# magarray_v1.net
KiCad netlist of a schematic drawn in EAGLE
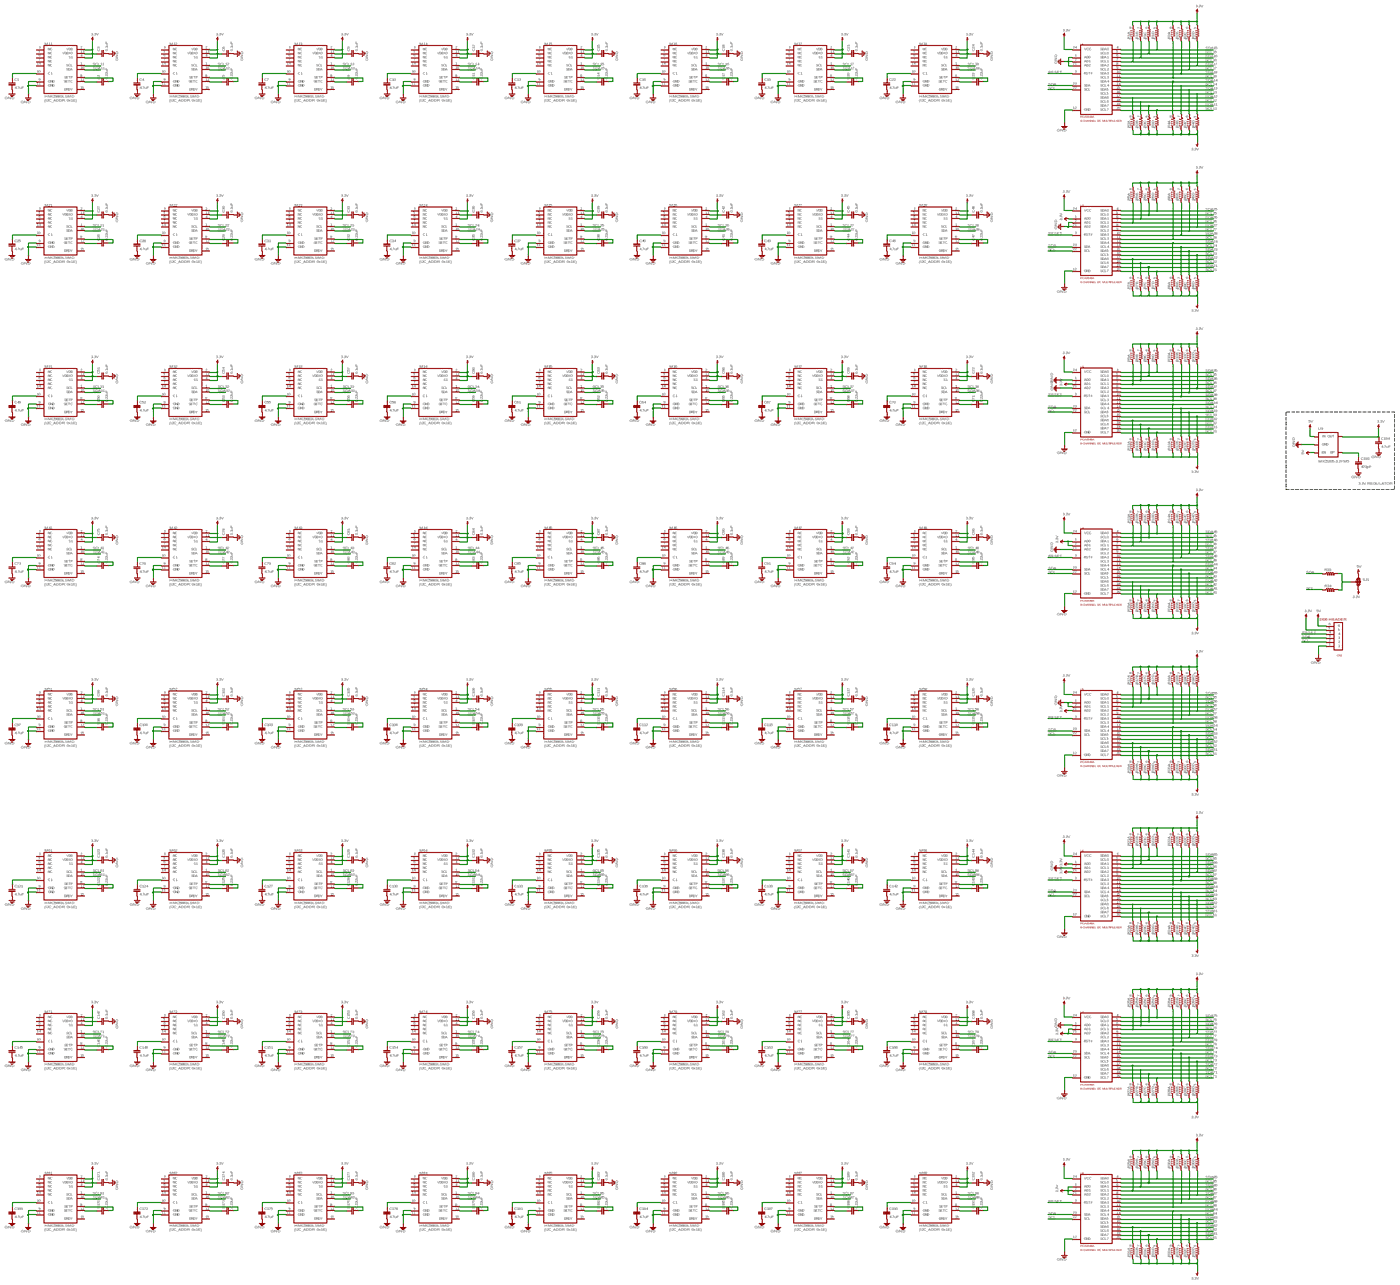
[diagram p0: schematic, sheet 1, overview]
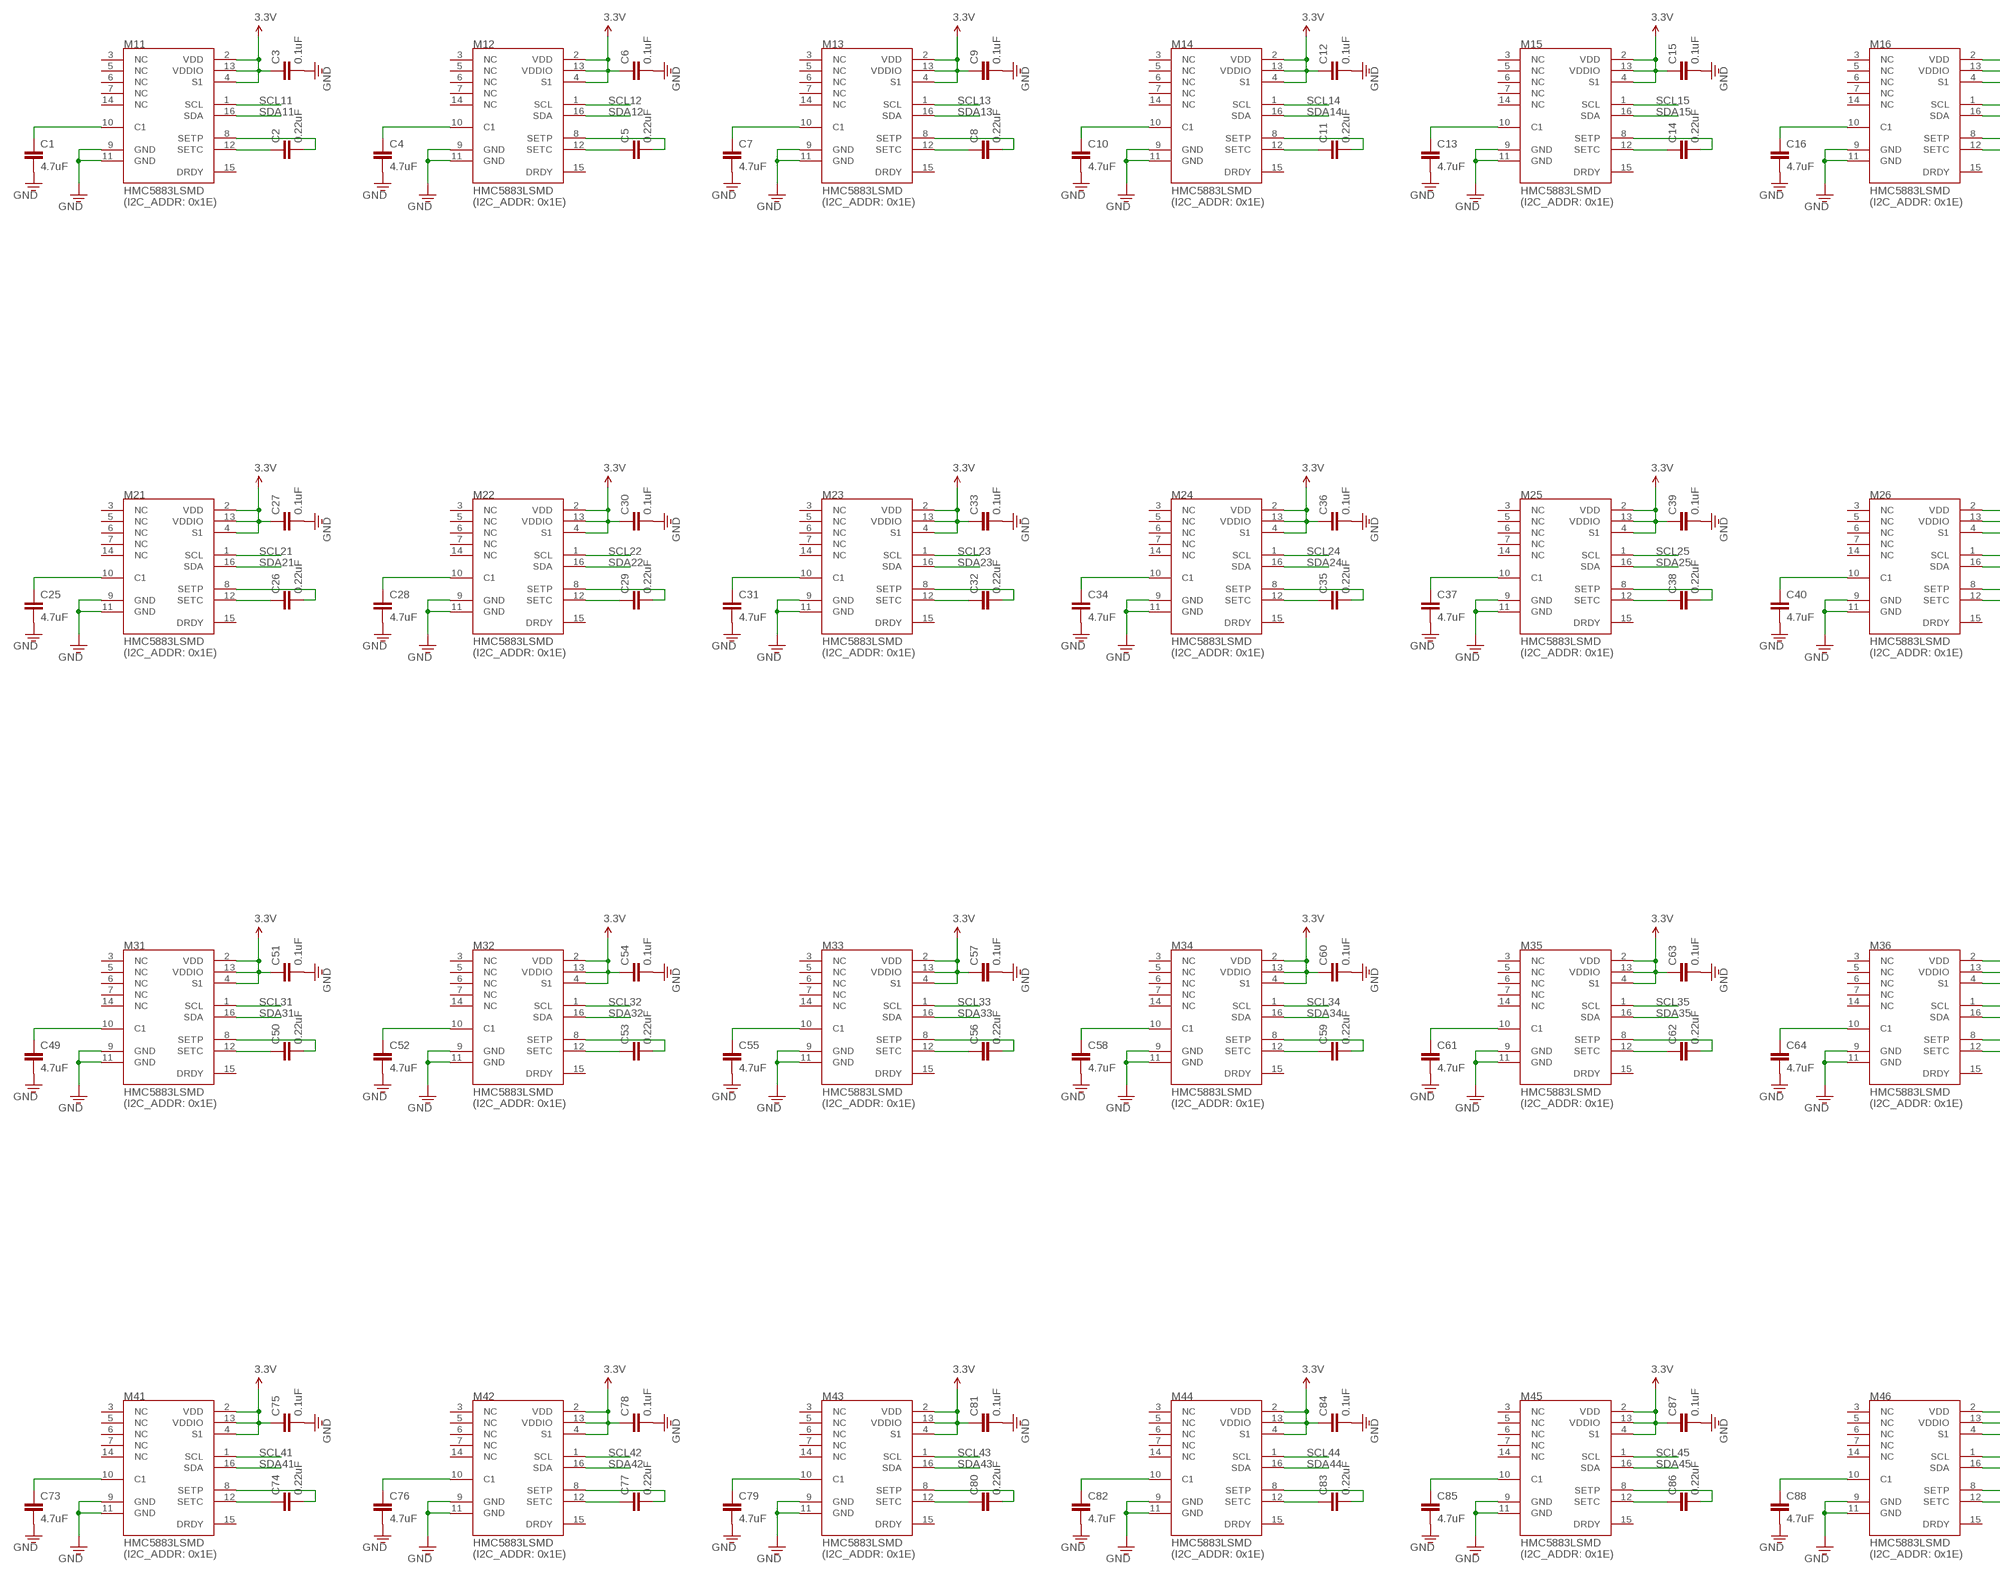
[diagram p1: schematic, sheet 1, part 1 of 4]
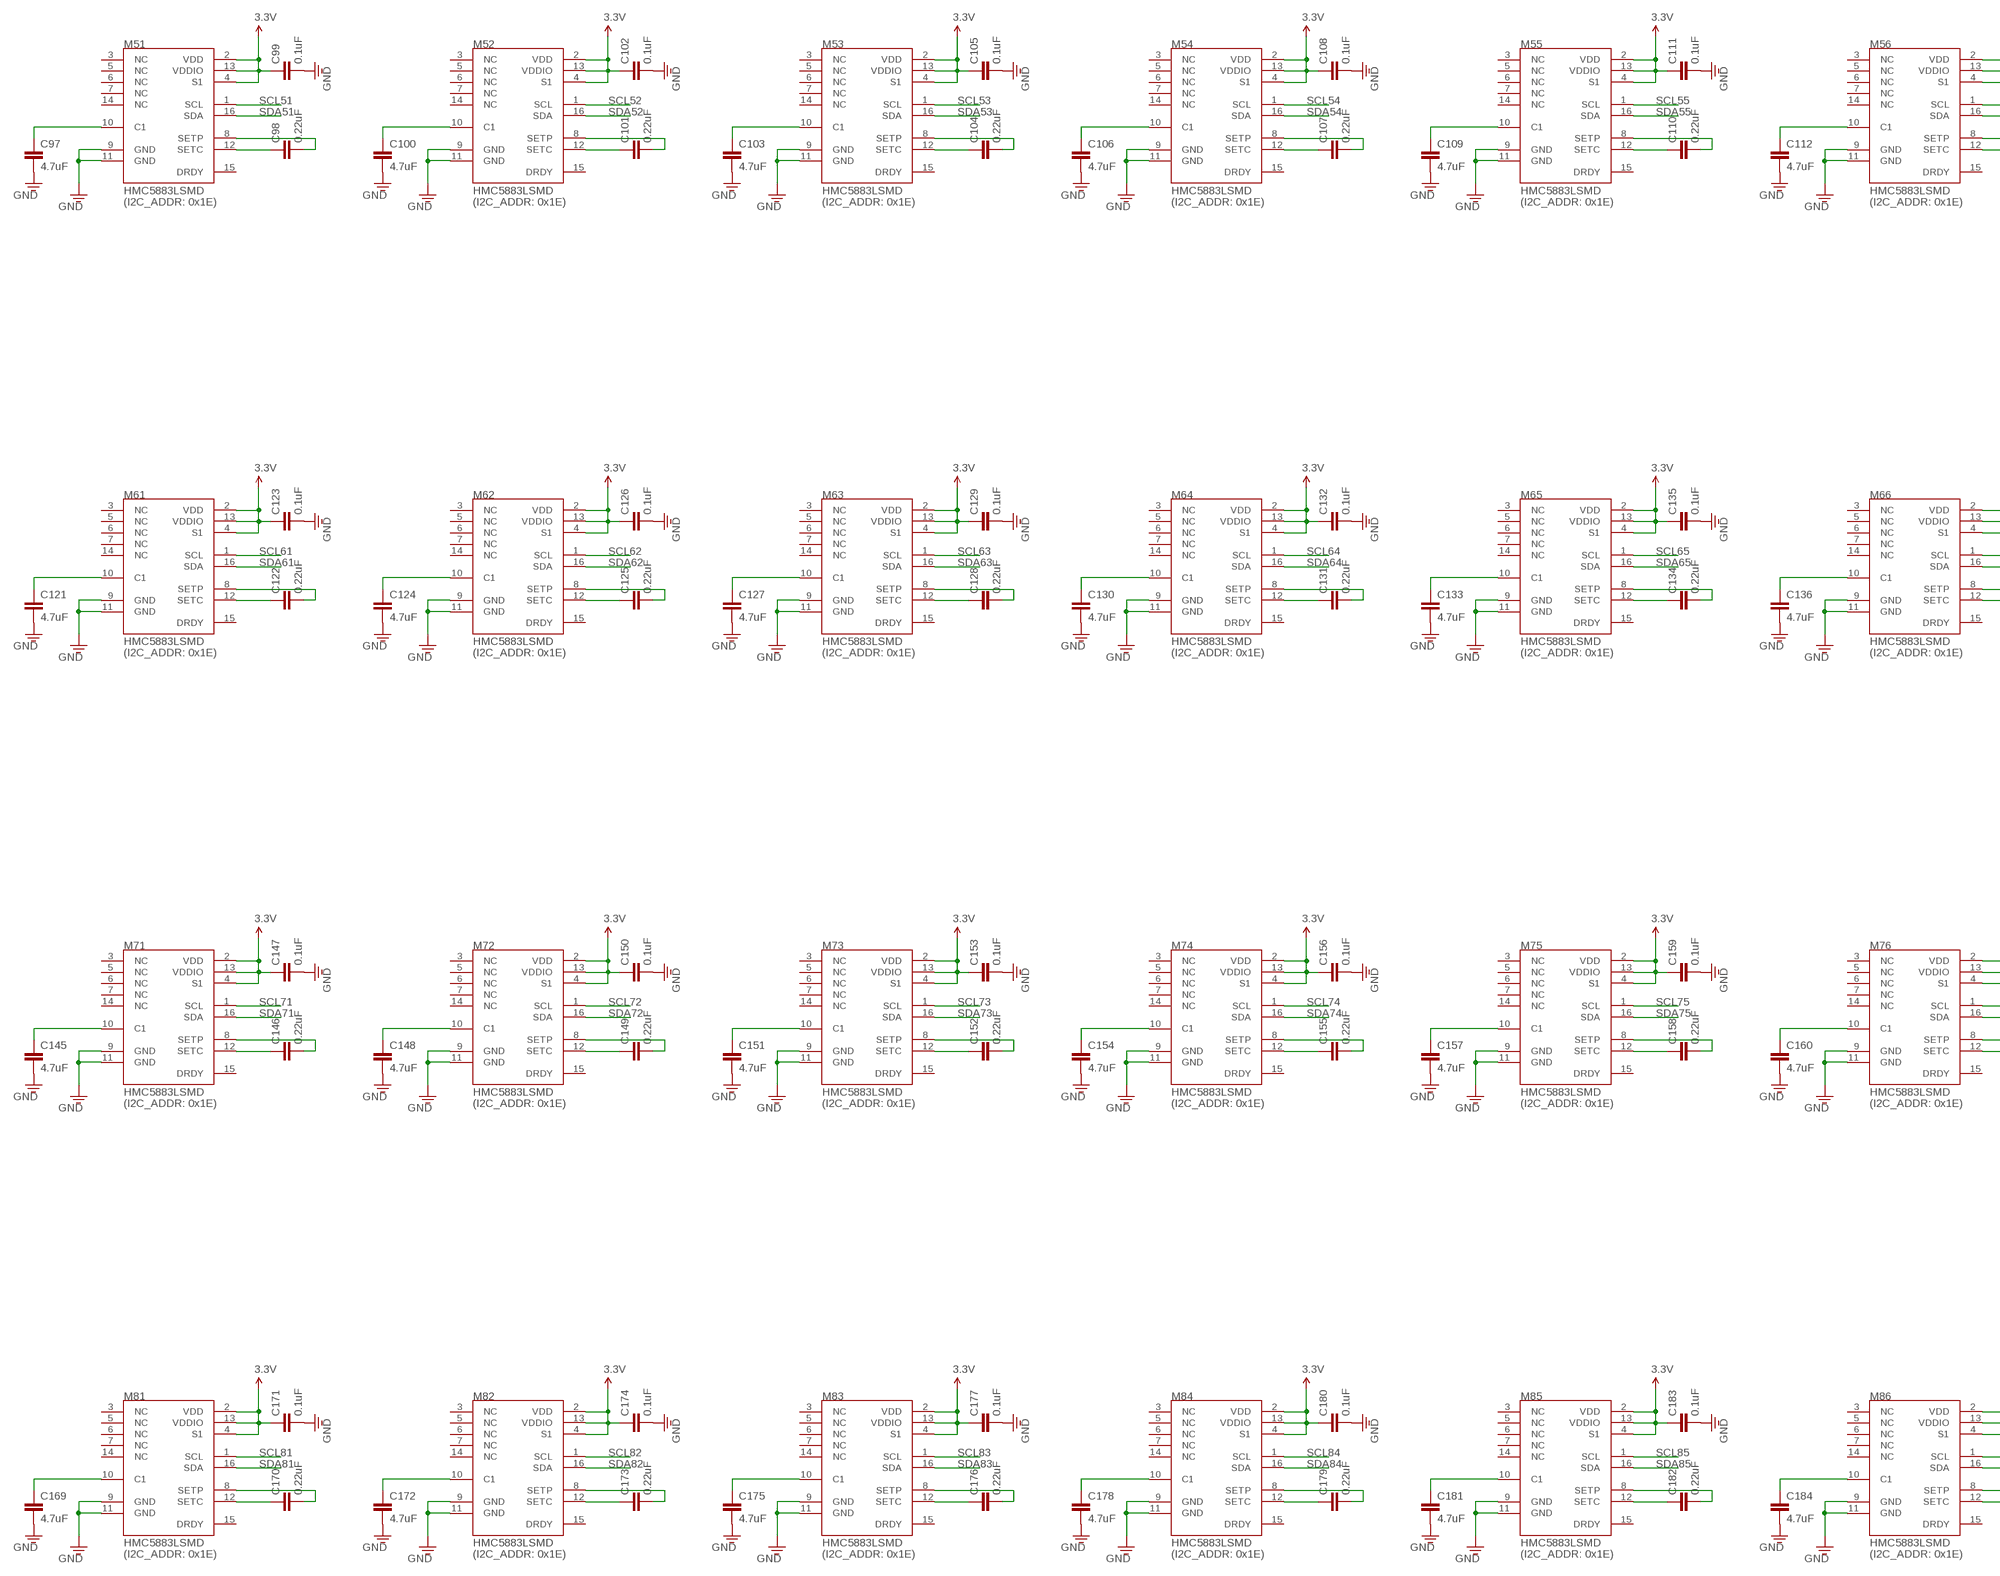
[diagram p2: schematic, sheet 1, part 2 of 4]
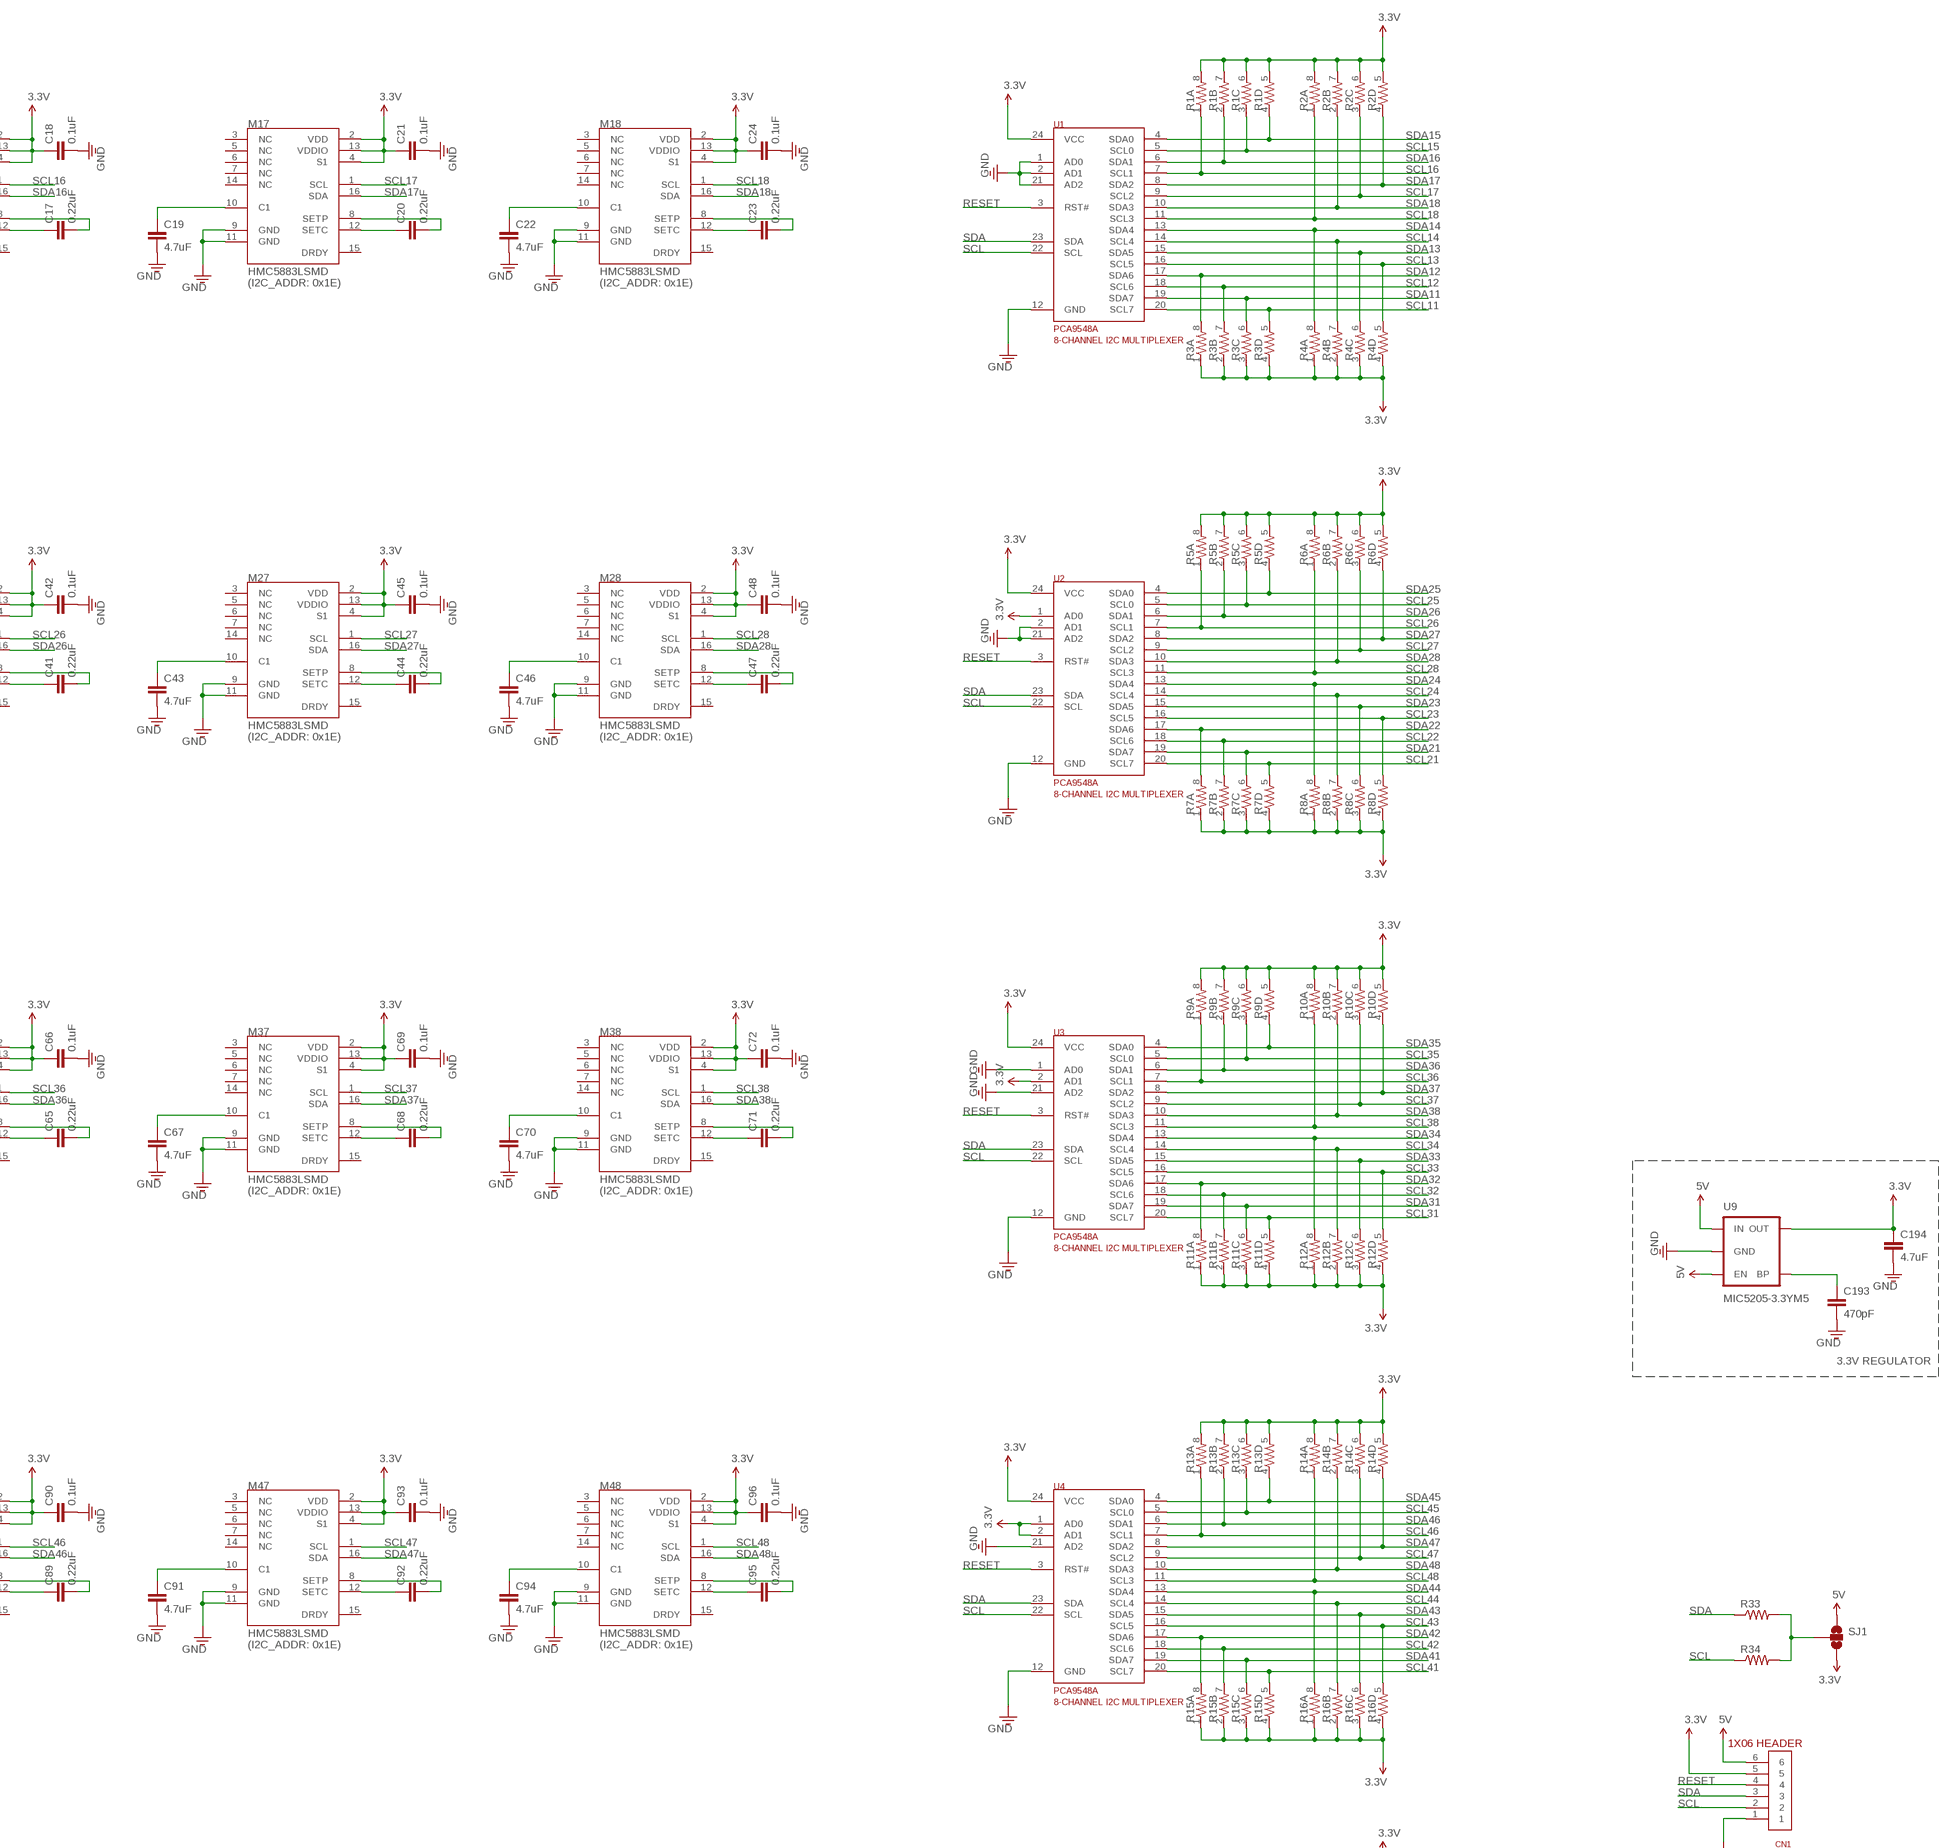
[diagram p3: schematic, sheet 1, part 3 of 4]
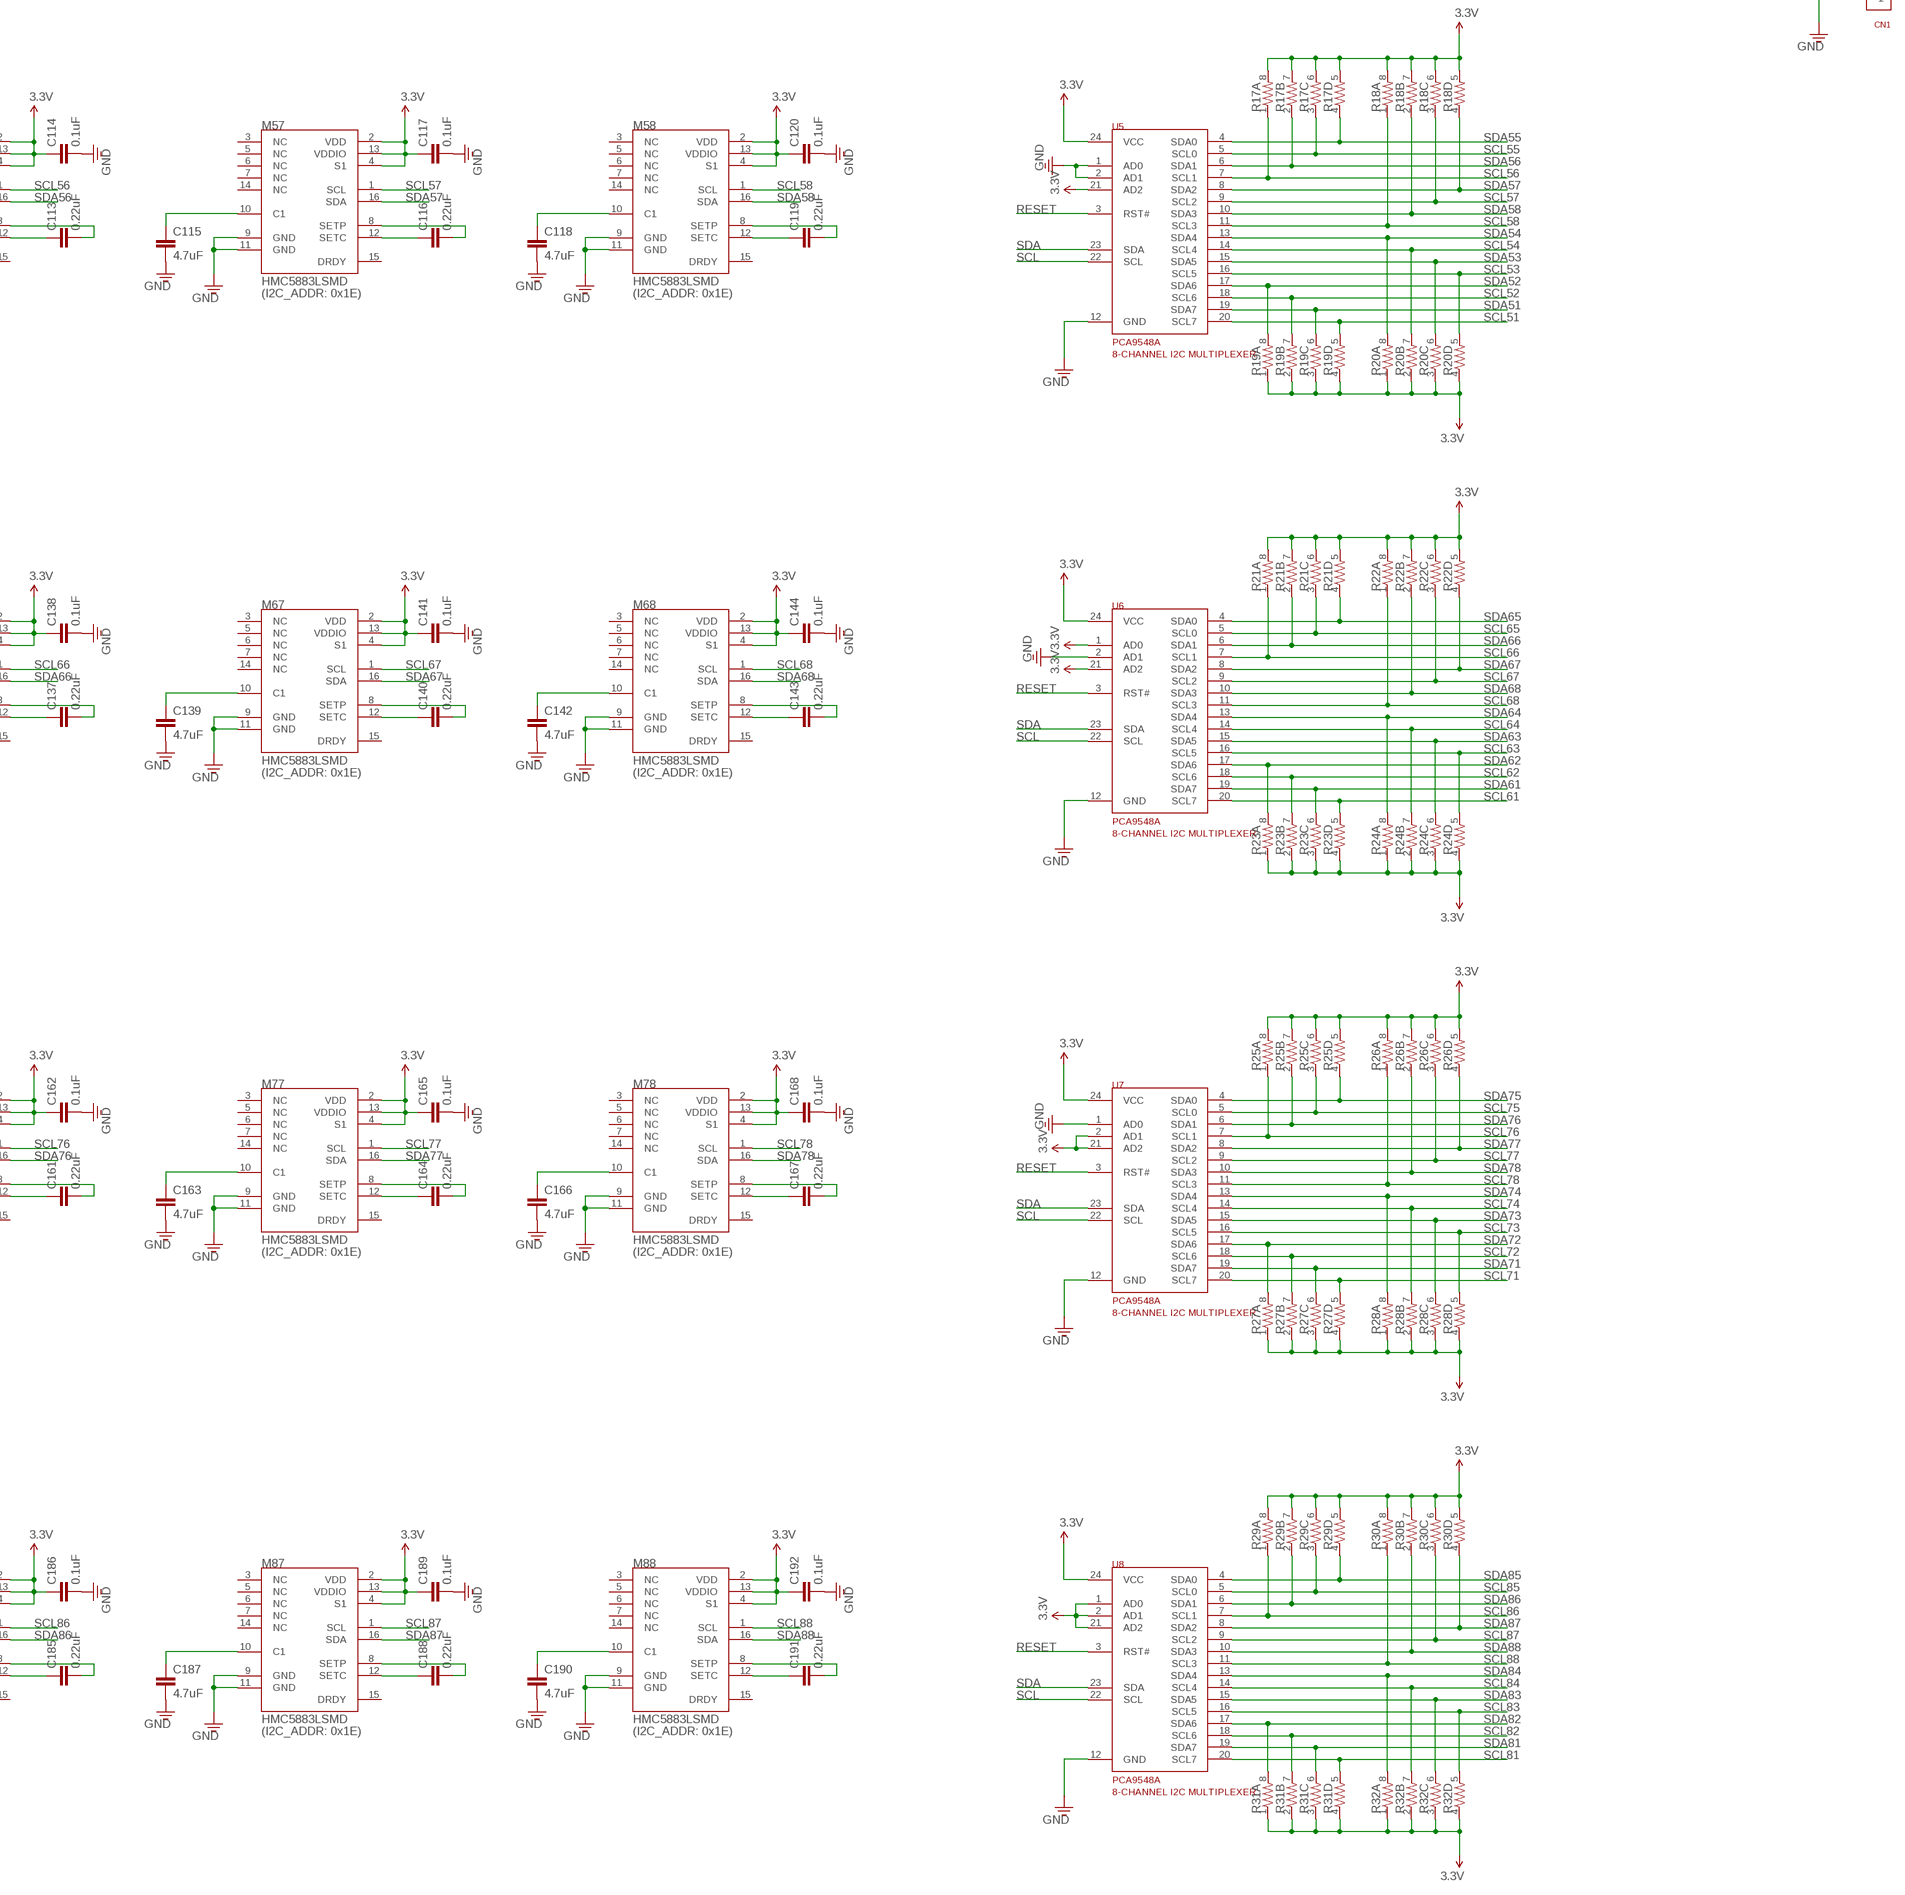
[diagram p4: schematic, sheet 1, part 4 of 4]

(export (version "E")
  (design (tool "Eeschema 10.0.6"))
  (components
    (comp (ref "C1")
      (value "4.7uF")
      (footprint "eagle-import:0603")
      (libsource (lib "eagle-import") (part "CAP0603"))
    )
    (comp (ref "C2")
      (value "0.22uF")
      (footprint "eagle-import:C0402")
      (libsource (lib "eagle-import") (part "CAP0402"))
    )
    (comp (ref "C3")
      (value "0.1uF")
      (footprint "eagle-import:C0402")
      (libsource (lib "eagle-import") (part "CAP0402"))
    )
    (comp (ref "C4")
      (value "4.7uF")
      (footprint "eagle-import:0603")
      (libsource (lib "eagle-import") (part "CAP0603"))
    )
    (comp (ref "C5")
      (value "0.22uF")
      (footprint "eagle-import:C0402")
      (libsource (lib "eagle-import") (part "CAP0402"))
    )
    (comp (ref "C6")
      (value "0.1uF")
      (footprint "eagle-import:C0402")
      (libsource (lib "eagle-import") (part "CAP0402"))
    )
    (comp (ref "C7")
      (value "4.7uF")
      (footprint "eagle-import:0603")
      (libsource (lib "eagle-import") (part "CAP0603"))
    )
    (comp (ref "C8")
      (value "0.22uF")
      (footprint "eagle-import:C0402")
      (libsource (lib "eagle-import") (part "CAP0402"))
    )
    (comp (ref "C9")
      (value "0.1uF")
      (footprint "eagle-import:C0402")
      (libsource (lib "eagle-import") (part "CAP0402"))
    )
    (comp (ref "C10")
      (value "4.7uF")
      (footprint "eagle-import:0603")
      (libsource (lib "eagle-import") (part "CAP0603"))
    )
    (comp (ref "C11")
      (value "0.22uF")
      (footprint "eagle-import:C0402")
      (libsource (lib "eagle-import") (part "CAP0402"))
    )
    (comp (ref "C12")
      (value "0.1uF")
      (footprint "eagle-import:C0402")
      (libsource (lib "eagle-import") (part "CAP0402"))
    )
    (comp (ref "C13")
      (value "4.7uF")
      (footprint "eagle-import:0603")
      (libsource (lib "eagle-import") (part "CAP0603"))
    )
    (comp (ref "C14")
      (value "0.22uF")
      (footprint "eagle-import:C0402")
      (libsource (lib "eagle-import") (part "CAP0402"))
    )
    (comp (ref "C15")
      (value "0.1uF")
      (footprint "eagle-import:C0402")
      (libsource (lib "eagle-import") (part "CAP0402"))
    )
    (comp (ref "C16")
      (value "4.7uF")
      (footprint "eagle-import:0603")
      (libsource (lib "eagle-import") (part "CAP0603"))
    )
    (comp (ref "C17")
      (value "0.22uF")
      (footprint "eagle-import:C0402")
      (libsource (lib "eagle-import") (part "CAP0402"))
    )
    (comp (ref "C18")
      (value "0.1uF")
      (footprint "eagle-import:C0402")
      (libsource (lib "eagle-import") (part "CAP0402"))
    )
    (comp (ref "C19")
      (value "4.7uF")
      (footprint "eagle-import:0603")
      (libsource (lib "eagle-import") (part "CAP0603"))
    )
    (comp (ref "C20")
      (value "0.22uF")
      (footprint "eagle-import:C0402")
      (libsource (lib "eagle-import") (part "CAP0402"))
    )
    (comp (ref "C21")
      (value "0.1uF")
      (footprint "eagle-import:C0402")
      (libsource (lib "eagle-import") (part "CAP0402"))
    )
    (comp (ref "C22")
      (value "4.7uF")
      (footprint "eagle-import:0603")
      (libsource (lib "eagle-import") (part "CAP0603"))
    )
    (comp (ref "C23")
      (value "0.22uF")
      (footprint "eagle-import:C0402")
      (libsource (lib "eagle-import") (part "CAP0402"))
    )
    (comp (ref "C24")
      (value "0.1uF")
      (footprint "eagle-import:C0402")
      (libsource (lib "eagle-import") (part "CAP0402"))
    )
    (comp (ref "C25")
      (value "4.7uF")
      (footprint "eagle-import:0603")
      (libsource (lib "eagle-import") (part "CAP0603"))
    )
    (comp (ref "C26")
      (value "0.22uF")
      (footprint "eagle-import:C0402")
      (libsource (lib "eagle-import") (part "CAP0402"))
    )
    (comp (ref "C27")
      (value "0.1uF")
      (footprint "eagle-import:C0402")
      (libsource (lib "eagle-import") (part "CAP0402"))
    )
    (comp (ref "C28")
      (value "4.7uF")
      (footprint "eagle-import:0603")
      (libsource (lib "eagle-import") (part "CAP0603"))
    )
    (comp (ref "C29")
      (value "0.22uF")
      (footprint "eagle-import:C0402")
      (libsource (lib "eagle-import") (part "CAP0402"))
    )
    (comp (ref "C30")
      (value "0.1uF")
      (footprint "eagle-import:C0402")
      (libsource (lib "eagle-import") (part "CAP0402"))
    )
    (comp (ref "C31")
      (value "4.7uF")
      (footprint "eagle-import:0603")
      (libsource (lib "eagle-import") (part "CAP0603"))
    )
    (comp (ref "C32")
      (value "0.22uF")
      (footprint "eagle-import:C0402")
      (libsource (lib "eagle-import") (part "CAP0402"))
    )
    (comp (ref "C33")
      (value "0.1uF")
      (footprint "eagle-import:C0402")
      (libsource (lib "eagle-import") (part "CAP0402"))
    )
    (comp (ref "C34")
      (value "4.7uF")
      (footprint "eagle-import:0603")
      (libsource (lib "eagle-import") (part "CAP0603"))
    )
    (comp (ref "C35")
      (value "0.22uF")
      (footprint "eagle-import:C0402")
      (libsource (lib "eagle-import") (part "CAP0402"))
    )
    (comp (ref "C36")
      (value "0.1uF")
      (footprint "eagle-import:C0402")
      (libsource (lib "eagle-import") (part "CAP0402"))
    )
    (comp (ref "C37")
      (value "4.7uF")
      (footprint "eagle-import:0603")
      (libsource (lib "eagle-import") (part "CAP0603"))
    )
    (comp (ref "C38")
      (value "0.22uF")
      (footprint "eagle-import:C0402")
      (libsource (lib "eagle-import") (part "CAP0402"))
    )
    (comp (ref "C39")
      (value "0.1uF")
      (footprint "eagle-import:C0402")
      (libsource (lib "eagle-import") (part "CAP0402"))
    )
    (comp (ref "C40")
      (value "4.7uF")
      (footprint "eagle-import:0603")
      (libsource (lib "eagle-import") (part "CAP0603"))
    )
    (comp (ref "C41")
      (value "0.22uF")
      (footprint "eagle-import:C0402")
      (libsource (lib "eagle-import") (part "CAP0402"))
    )
    (comp (ref "C42")
      (value "0.1uF")
      (footprint "eagle-import:C0402")
      (libsource (lib "eagle-import") (part "CAP0402"))
    )
    (comp (ref "C43")
      (value "4.7uF")
      (footprint "eagle-import:0603")
      (libsource (lib "eagle-import") (part "CAP0603"))
    )
    (comp (ref "C44")
      (value "0.22uF")
      (footprint "eagle-import:C0402")
      (libsource (lib "eagle-import") (part "CAP0402"))
    )
    (comp (ref "C45")
      (value "0.1uF")
      (footprint "eagle-import:C0402")
      (libsource (lib "eagle-import") (part "CAP0402"))
    )
    (comp (ref "C46")
      (value "4.7uF")
      (footprint "eagle-import:0603")
      (libsource (lib "eagle-import") (part "CAP0603"))
    )
    (comp (ref "C47")
      (value "0.22uF")
      (footprint "eagle-import:C0402")
      (libsource (lib "eagle-import") (part "CAP0402"))
    )
    (comp (ref "C48")
      (value "0.1uF")
      (footprint "eagle-import:C0402")
      (libsource (lib "eagle-import") (part "CAP0402"))
    )
    (comp (ref "C49")
      (value "4.7uF")
      (footprint "eagle-import:0603")
      (libsource (lib "eagle-import") (part "CAP0603"))
    )
    (comp (ref "C50")
      (value "0.22uF")
      (footprint "eagle-import:C0402")
      (libsource (lib "eagle-import") (part "CAP0402"))
    )
    (comp (ref "C51")
      (value "0.1uF")
      (footprint "eagle-import:C0402")
      (libsource (lib "eagle-import") (part "CAP0402"))
    )
    (comp (ref "C52")
      (value "4.7uF")
      (footprint "eagle-import:0603")
      (libsource (lib "eagle-import") (part "CAP0603"))
    )
    (comp (ref "C53")
      (value "0.22uF")
      (footprint "eagle-import:C0402")
      (libsource (lib "eagle-import") (part "CAP0402"))
    )
    (comp (ref "C54")
      (value "0.1uF")
      (footprint "eagle-import:C0402")
      (libsource (lib "eagle-import") (part "CAP0402"))
    )
    (comp (ref "C55")
      (value "4.7uF")
      (footprint "eagle-import:0603")
      (libsource (lib "eagle-import") (part "CAP0603"))
    )
    (comp (ref "C56")
      (value "0.22uF")
      (footprint "eagle-import:C0402")
      (libsource (lib "eagle-import") (part "CAP0402"))
    )
    (comp (ref "C57")
      (value "0.1uF")
      (footprint "eagle-import:C0402")
      (libsource (lib "eagle-import") (part "CAP0402"))
    )
    (comp (ref "C58")
      (value "4.7uF")
      (footprint "eagle-import:0603")
      (libsource (lib "eagle-import") (part "CAP0603"))
    )
    (comp (ref "C59")
      (value "0.22uF")
      (footprint "eagle-import:C0402")
      (libsource (lib "eagle-import") (part "CAP0402"))
    )
    (comp (ref "C60")
      (value "0.1uF")
      (footprint "eagle-import:C0402")
      (libsource (lib "eagle-import") (part "CAP0402"))
    )
    (comp (ref "C61")
      (value "4.7uF")
      (footprint "eagle-import:0603")
      (libsource (lib "eagle-import") (part "CAP0603"))
    )
    (comp (ref "C62")
      (value "0.22uF")
      (footprint "eagle-import:C0402")
      (libsource (lib "eagle-import") (part "CAP0402"))
    )
    (comp (ref "C63")
      (value "0.1uF")
      (footprint "eagle-import:C0402")
      (libsource (lib "eagle-import") (part "CAP0402"))
    )
    (comp (ref "C64")
      (value "4.7uF")
      (footprint "eagle-import:0603")
      (libsource (lib "eagle-import") (part "CAP0603"))
    )
    (comp (ref "C65")
      (value "0.22uF")
      (footprint "eagle-import:C0402")
      (libsource (lib "eagle-import") (part "CAP0402"))
    )
    (comp (ref "C66")
      (value "0.1uF")
      (footprint "eagle-import:C0402")
      (libsource (lib "eagle-import") (part "CAP0402"))
    )
    (comp (ref "C67")
      (value "4.7uF")
      (footprint "eagle-import:0603")
      (libsource (lib "eagle-import") (part "CAP0603"))
    )
    (comp (ref "C68")
      (value "0.22uF")
      (footprint "eagle-import:C0402")
      (libsource (lib "eagle-import") (part "CAP0402"))
    )
    (comp (ref "C69")
      (value "0.1uF")
      (footprint "eagle-import:C0402")
      (libsource (lib "eagle-import") (part "CAP0402"))
    )
    (comp (ref "C70")
      (value "4.7uF")
      (footprint "eagle-import:0603")
      (libsource (lib "eagle-import") (part "CAP0603"))
    )
    (comp (ref "C71")
      (value "0.22uF")
      (footprint "eagle-import:C0402")
      (libsource (lib "eagle-import") (part "CAP0402"))
    )
    (comp (ref "C72")
      (value "0.1uF")
      (footprint "eagle-import:C0402")
      (libsource (lib "eagle-import") (part "CAP0402"))
    )
    (comp (ref "C73")
      (value "4.7uF")
      (footprint "eagle-import:0603")
      (libsource (lib "eagle-import") (part "CAP0603"))
    )
    (comp (ref "C74")
      (value "0.22uF")
      (footprint "eagle-import:C0402")
      (libsource (lib "eagle-import") (part "CAP0402"))
    )
    (comp (ref "C75")
      (value "0.1uF")
      (footprint "eagle-import:C0402")
      (libsource (lib "eagle-import") (part "CAP0402"))
    )
    (comp (ref "C76")
      (value "4.7uF")
      (footprint "eagle-import:0603")
      (libsource (lib "eagle-import") (part "CAP0603"))
    )
    (comp (ref "C77")
      (value "0.22uF")
      (footprint "eagle-import:C0402")
      (libsource (lib "eagle-import") (part "CAP0402"))
    )
    (comp (ref "C78")
      (value "0.1uF")
      (footprint "eagle-import:C0402")
      (libsource (lib "eagle-import") (part "CAP0402"))
    )
    (comp (ref "C79")
      (value "4.7uF")
      (footprint "eagle-import:0603")
      (libsource (lib "eagle-import") (part "CAP0603"))
    )
    (comp (ref "C80")
      (value "0.22uF")
      (footprint "eagle-import:C0402")
      (libsource (lib "eagle-import") (part "CAP0402"))
    )
    (comp (ref "C81")
      (value "0.1uF")
      (footprint "eagle-import:C0402")
      (libsource (lib "eagle-import") (part "CAP0402"))
    )
    (comp (ref "C82")
      (value "4.7uF")
      (footprint "eagle-import:0603")
      (libsource (lib "eagle-import") (part "CAP0603"))
    )
    (comp (ref "C83")
      (value "0.22uF")
      (footprint "eagle-import:C0402")
      (libsource (lib "eagle-import") (part "CAP0402"))
    )
    (comp (ref "C84")
      (value "0.1uF")
      (footprint "eagle-import:C0402")
      (libsource (lib "eagle-import") (part "CAP0402"))
    )
    (comp (ref "C85")
      (value "4.7uF")
      (footprint "eagle-import:0603")
      (libsource (lib "eagle-import") (part "CAP0603"))
    )
    (comp (ref "C86")
      (value "0.22uF")
      (footprint "eagle-import:C0402")
      (libsource (lib "eagle-import") (part "CAP0402"))
    )
    (comp (ref "C87")
      (value "0.1uF")
      (footprint "eagle-import:C0402")
      (libsource (lib "eagle-import") (part "CAP0402"))
    )
    (comp (ref "C88")
      (value "4.7uF")
      (footprint "eagle-import:0603")
      (libsource (lib "eagle-import") (part "CAP0603"))
    )
    (comp (ref "C89")
      (value "0.22uF")
      (footprint "eagle-import:C0402")
      (libsource (lib "eagle-import") (part "CAP0402"))
    )
    (comp (ref "C90")
      (value "0.1uF")
      (footprint "eagle-import:C0402")
      (libsource (lib "eagle-import") (part "CAP0402"))
    )
    (comp (ref "C91")
      (value "4.7uF")
      (footprint "eagle-import:0603")
      (libsource (lib "eagle-import") (part "CAP0603"))
    )
    (comp (ref "C92")
      (value "0.22uF")
      (footprint "eagle-import:C0402")
      (libsource (lib "eagle-import") (part "CAP0402"))
    )
    (comp (ref "C93")
      (value "0.1uF")
      (footprint "eagle-import:C0402")
      (libsource (lib "eagle-import") (part "CAP0402"))
    )
    (comp (ref "C94")
      (value "4.7uF")
      (footprint "eagle-import:0603")
      (libsource (lib "eagle-import") (part "CAP0603"))
    )
    (comp (ref "C95")
      (value "0.22uF")
      (footprint "eagle-import:C0402")
      (libsource (lib "eagle-import") (part "CAP0402"))
    )
    (comp (ref "C96")
      (value "0.1uF")
      (footprint "eagle-import:C0402")
      (libsource (lib "eagle-import") (part "CAP0402"))
    )
    (comp (ref "C97")
      (value "4.7uF")
      (footprint "eagle-import:0603")
      (libsource (lib "eagle-import") (part "CAP0603"))
    )
    (comp (ref "C98")
      (value "0.22uF")
      (footprint "eagle-import:C0402")
      (libsource (lib "eagle-import") (part "CAP0402"))
    )
    (comp (ref "C99")
      (value "0.1uF")
      (footprint "eagle-import:C0402")
      (libsource (lib "eagle-import") (part "CAP0402"))
    )
    (comp (ref "C100")
      (value "4.7uF")
      (footprint "eagle-import:0603")
      (libsource (lib "eagle-import") (part "CAP0603"))
    )
    (comp (ref "C101")
      (value "0.22uF")
      (footprint "eagle-import:C0402")
      (libsource (lib "eagle-import") (part "CAP0402"))
    )
    (comp (ref "C102")
      (value "0.1uF")
      (footprint "eagle-import:C0402")
      (libsource (lib "eagle-import") (part "CAP0402"))
    )
    (comp (ref "C103")
      (value "4.7uF")
      (footprint "eagle-import:0603")
      (libsource (lib "eagle-import") (part "CAP0603"))
    )
    (comp (ref "C104")
      (value "0.22uF")
      (footprint "eagle-import:C0402")
      (libsource (lib "eagle-import") (part "CAP0402"))
    )
    (comp (ref "C105")
      (value "0.1uF")
      (footprint "eagle-import:C0402")
      (libsource (lib "eagle-import") (part "CAP0402"))
    )
    (comp (ref "C106")
      (value "4.7uF")
      (footprint "eagle-import:0603")
      (libsource (lib "eagle-import") (part "CAP0603"))
    )
    (comp (ref "C107")
      (value "0.22uF")
      (footprint "eagle-import:C0402")
      (libsource (lib "eagle-import") (part "CAP0402"))
    )
    (comp (ref "C108")
      (value "0.1uF")
      (footprint "eagle-import:C0402")
      (libsource (lib "eagle-import") (part "CAP0402"))
    )
    (comp (ref "C109")
      (value "4.7uF")
      (footprint "eagle-import:0603")
      (libsource (lib "eagle-import") (part "CAP0603"))
    )
    (comp (ref "C110")
      (value "0.22uF")
      (footprint "eagle-import:C0402")
      (libsource (lib "eagle-import") (part "CAP0402"))
    )
    (comp (ref "C111")
      (value "0.1uF")
      (footprint "eagle-import:C0402")
      (libsource (lib "eagle-import") (part "CAP0402"))
    )
    (comp (ref "C112")
      (value "4.7uF")
      (footprint "eagle-import:0603")
      (libsource (lib "eagle-import") (part "CAP0603"))
    )
    (comp (ref "C113")
      (value "0.22uF")
      (footprint "eagle-import:C0402")
      (libsource (lib "eagle-import") (part "CAP0402"))
    )
    (comp (ref "C114")
      (value "0.1uF")
      (footprint "eagle-import:C0402")
      (libsource (lib "eagle-import") (part "CAP0402"))
    )
    (comp (ref "C115")
      (value "4.7uF")
      (footprint "eagle-import:0603")
      (libsource (lib "eagle-import") (part "CAP0603"))
    )
    (comp (ref "C116")
      (value "0.22uF")
      (footprint "eagle-import:C0402")
      (libsource (lib "eagle-import") (part "CAP0402"))
    )
    (comp (ref "C117")
      (value "0.1uF")
      (footprint "eagle-import:C0402")
      (libsource (lib "eagle-import") (part "CAP0402"))
    )
    (comp (ref "C118")
      (value "4.7uF")
      (footprint "eagle-import:0603")
      (libsource (lib "eagle-import") (part "CAP0603"))
    )
    (comp (ref "C119")
      (value "0.22uF")
      (footprint "eagle-import:C0402")
      (libsource (lib "eagle-import") (part "CAP0402"))
    )
    (comp (ref "C120")
      (value "0.1uF")
      (footprint "eagle-import:C0402")
      (libsource (lib "eagle-import") (part "CAP0402"))
    )
    (comp (ref "C121")
      (value "4.7uF")
      (footprint "eagle-import:0603")
      (libsource (lib "eagle-import") (part "CAP0603"))
    )
    (comp (ref "C122")
      (value "0.22uF")
      (footprint "eagle-import:C0402")
      (libsource (lib "eagle-import") (part "CAP0402"))
    )
    (comp (ref "C123")
      (value "0.1uF")
      (footprint "eagle-import:C0402")
      (libsource (lib "eagle-import") (part "CAP0402"))
    )
    (comp (ref "C124")
      (value "4.7uF")
      (footprint "eagle-import:0603")
      (libsource (lib "eagle-import") (part "CAP0603"))
    )
    (comp (ref "C125")
      (value "0.22uF")
      (footprint "eagle-import:C0402")
      (libsource (lib "eagle-import") (part "CAP0402"))
    )
    (comp (ref "C126")
      (value "0.1uF")
      (footprint "eagle-import:C0402")
      (libsource (lib "eagle-import") (part "CAP0402"))
    )
    (comp (ref "C127")
      (value "4.7uF")
      (footprint "eagle-import:0603")
      (libsource (lib "eagle-import") (part "CAP0603"))
    )
    (comp (ref "C128")
      (value "0.22uF")
      (footprint "eagle-import:C0402")
      (libsource (lib "eagle-import") (part "CAP0402"))
    )
    (comp (ref "C129")
      (value "0.1uF")
      (footprint "eagle-import:C0402")
      (libsource (lib "eagle-import") (part "CAP0402"))
    )
    (comp (ref "C130")
      (value "4.7uF")
      (footprint "eagle-import:0603")
      (libsource (lib "eagle-import") (part "CAP0603"))
    )
    (comp (ref "C131")
      (value "0.22uF")
      (footprint "eagle-import:C0402")
      (libsource (lib "eagle-import") (part "CAP0402"))
    )
    (comp (ref "C132")
      (value "0.1uF")
      (footprint "eagle-import:C0402")
      (libsource (lib "eagle-import") (part "CAP0402"))
    )
    (comp (ref "C133")
      (value "4.7uF")
      (footprint "eagle-import:0603")
      (libsource (lib "eagle-import") (part "CAP0603"))
    )
    (comp (ref "C134")
      (value "0.22uF")
      (footprint "eagle-import:C0402")
      (libsource (lib "eagle-import") (part "CAP0402"))
    )
    (comp (ref "C135")
      (value "0.1uF")
      (footprint "eagle-import:C0402")
      (libsource (lib "eagle-import") (part "CAP0402"))
    )
    (comp (ref "C136")
      (value "4.7uF")
      (footprint "eagle-import:0603")
      (libsource (lib "eagle-import") (part "CAP0603"))
    )
    (comp (ref "C137")
      (value "0.22uF")
      (footprint "eagle-import:C0402")
      (libsource (lib "eagle-import") (part "CAP0402"))
    )
    (comp (ref "C138")
      (value "0.1uF")
      (footprint "eagle-import:C0402")
      (libsource (lib "eagle-import") (part "CAP0402"))
    )
    (comp (ref "C139")
      (value "4.7uF")
      (footprint "eagle-import:0603")
      (libsource (lib "eagle-import") (part "CAP0603"))
    )
    (comp (ref "C140")
      (value "0.22uF")
      (footprint "eagle-import:C0402")
      (libsource (lib "eagle-import") (part "CAP0402"))
    )
    (comp (ref "C141")
      (value "0.1uF")
      (footprint "eagle-import:C0402")
      (libsource (lib "eagle-import") (part "CAP0402"))
    )
    (comp (ref "C142")
      (value "4.7uF")
      (footprint "eagle-import:0603")
      (libsource (lib "eagle-import") (part "CAP0603"))
    )
    (comp (ref "C143")
      (value "0.22uF")
      (footprint "eagle-import:C0402")
      (libsource (lib "eagle-import") (part "CAP0402"))
    )
    (comp (ref "C144")
      (value "0.1uF")
      (footprint "eagle-import:C0402")
      (libsource (lib "eagle-import") (part "CAP0402"))
    )
    (comp (ref "C145")
      (value "4.7uF")
      (footprint "eagle-import:0603")
      (libsource (lib "eagle-import") (part "CAP0603"))
    )
    (comp (ref "C146")
      (value "0.22uF")
      (footprint "eagle-import:C0402")
      (libsource (lib "eagle-import") (part "CAP0402"))
    )
    (comp (ref "C147")
      (value "0.1uF")
      (footprint "eagle-import:C0402")
      (libsource (lib "eagle-import") (part "CAP0402"))
    )
    (comp (ref "C148")
      (value "4.7uF")
      (footprint "eagle-import:0603")
      (libsource (lib "eagle-import") (part "CAP0603"))
    )
    (comp (ref "C149")
      (value "0.22uF")
      (footprint "eagle-import:C0402")
      (libsource (lib "eagle-import") (part "CAP0402"))
    )
    (comp (ref "C150")
      (value "0.1uF")
      (footprint "eagle-import:C0402")
      (libsource (lib "eagle-import") (part "CAP0402"))
    )
    (comp (ref "C151")
      (value "4.7uF")
      (footprint "eagle-import:0603")
      (libsource (lib "eagle-import") (part "CAP0603"))
    )
    (comp (ref "C152")
      (value "0.22uF")
      (footprint "eagle-import:C0402")
      (libsource (lib "eagle-import") (part "CAP0402"))
    )
    (comp (ref "C153")
      (value "0.1uF")
      (footprint "eagle-import:C0402")
      (libsource (lib "eagle-import") (part "CAP0402"))
    )
    (comp (ref "C154")
      (value "4.7uF")
      (footprint "eagle-import:0603")
      (libsource (lib "eagle-import") (part "CAP0603"))
    )
    (comp (ref "C155")
      (value "0.22uF")
      (footprint "eagle-import:C0402")
      (libsource (lib "eagle-import") (part "CAP0402"))
    )
    (comp (ref "C156")
      (value "0.1uF")
      (footprint "eagle-import:C0402")
      (libsource (lib "eagle-import") (part "CAP0402"))
    )
    (comp (ref "C157")
      (value "4.7uF")
      (footprint "eagle-import:0603")
      (libsource (lib "eagle-import") (part "CAP0603"))
    )
    (comp (ref "C158")
      (value "0.22uF")
      (footprint "eagle-import:C0402")
      (libsource (lib "eagle-import") (part "CAP0402"))
    )
    (comp (ref "C159")
      (value "0.1uF")
      (footprint "eagle-import:C0402")
      (libsource (lib "eagle-import") (part "CAP0402"))
    )
    (comp (ref "C160")
      (value "4.7uF")
      (footprint "eagle-import:0603")
      (libsource (lib "eagle-import") (part "CAP0603"))
    )
    (comp (ref "C161")
      (value "0.22uF")
      (footprint "eagle-import:C0402")
      (libsource (lib "eagle-import") (part "CAP0402"))
    )
    (comp (ref "C162")
      (value "0.1uF")
      (footprint "eagle-import:C0402")
      (libsource (lib "eagle-import") (part "CAP0402"))
    )
    (comp (ref "C163")
      (value "4.7uF")
      (footprint "eagle-import:0603")
      (libsource (lib "eagle-import") (part "CAP0603"))
    )
    (comp (ref "C164")
      (value "0.22uF")
      (footprint "eagle-import:C0402")
      (libsource (lib "eagle-import") (part "CAP0402"))
    )
    (comp (ref "C165")
      (value "0.1uF")
      (footprint "eagle-import:C0402")
      (libsource (lib "eagle-import") (part "CAP0402"))
    )
    (comp (ref "C166")
      (value "4.7uF")
      (footprint "eagle-import:0603")
      (libsource (lib "eagle-import") (part "CAP0603"))
    )
    (comp (ref "C167")
      (value "0.22uF")
      (footprint "eagle-import:C0402")
      (libsource (lib "eagle-import") (part "CAP0402"))
    )
    (comp (ref "C168")
      (value "0.1uF")
      (footprint "eagle-import:C0402")
      (libsource (lib "eagle-import") (part "CAP0402"))
    )
    (comp (ref "C169")
      (value "4.7uF")
      (footprint "eagle-import:0603")
      (libsource (lib "eagle-import") (part "CAP0603"))
    )
    (comp (ref "C170")
      (value "0.22uF")
      (footprint "eagle-import:C0402")
      (libsource (lib "eagle-import") (part "CAP0402"))
    )
    (comp (ref "C171")
      (value "0.1uF")
      (footprint "eagle-import:C0402")
      (libsource (lib "eagle-import") (part "CAP0402"))
    )
    (comp (ref "C172")
      (value "4.7uF")
      (footprint "eagle-import:0603")
      (libsource (lib "eagle-import") (part "CAP0603"))
    )
    (comp (ref "C173")
      (value "0.22uF")
      (footprint "eagle-import:C0402")
      (libsource (lib "eagle-import") (part "CAP0402"))
    )
    (comp (ref "C174")
      (value "0.1uF")
      (footprint "eagle-import:C0402")
      (libsource (lib "eagle-import") (part "CAP0402"))
    )
    (comp (ref "C175")
      (value "4.7uF")
      (footprint "eagle-import:0603")
      (libsource (lib "eagle-import") (part "CAP0603"))
    )
    (comp (ref "C176")
      (value "0.22uF")
      (footprint "eagle-import:C0402")
      (libsource (lib "eagle-import") (part "CAP0402"))
    )
    (comp (ref "C177")
      (value "0.1uF")
      (footprint "eagle-import:C0402")
      (libsource (lib "eagle-import") (part "CAP0402"))
    )
    (comp (ref "C178")
      (value "4.7uF")
      (footprint "eagle-import:0603")
      (libsource (lib "eagle-import") (part "CAP0603"))
    )
    (comp (ref "C179")
      (value "0.22uF")
      (footprint "eagle-import:C0402")
      (libsource (lib "eagle-import") (part "CAP0402"))
    )
    (comp (ref "C180")
      (value "0.1uF")
      (footprint "eagle-import:C0402")
      (libsource (lib "eagle-import") (part "CAP0402"))
    )
    (comp (ref "C181")
      (value "4.7uF")
      (footprint "eagle-import:0603")
      (libsource (lib "eagle-import") (part "CAP0603"))
    )
    (comp (ref "C182")
      (value "0.22uF")
      (footprint "eagle-import:C0402")
      (libsource (lib "eagle-import") (part "CAP0402"))
    )
    (comp (ref "C183")
      (value "0.1uF")
      (footprint "eagle-import:C0402")
      (libsource (lib "eagle-import") (part "CAP0402"))
    )
    (comp (ref "C184")
      (value "4.7uF")
      (footprint "eagle-import:0603")
      (libsource (lib "eagle-import") (part "CAP0603"))
    )
    (comp (ref "C185")
      (value "0.22uF")
      (footprint "eagle-import:C0402")
      (libsource (lib "eagle-import") (part "CAP0402"))
    )
    (comp (ref "C186")
      (value "0.1uF")
      (footprint "eagle-import:C0402")
      (libsource (lib "eagle-import") (part "CAP0402"))
    )
    (comp (ref "C187")
      (value "4.7uF")
      (footprint "eagle-import:0603")
      (libsource (lib "eagle-import") (part "CAP0603"))
    )
    (comp (ref "C188")
      (value "0.22uF")
      (footprint "eagle-import:C0402")
      (libsource (lib "eagle-import") (part "CAP0402"))
    )
    (comp (ref "C189")
      (value "0.1uF")
      (footprint "eagle-import:C0402")
      (libsource (lib "eagle-import") (part "CAP0402"))
    )
    (comp (ref "C190")
      (value "4.7uF")
      (footprint "eagle-import:0603")
      (libsource (lib "eagle-import") (part "CAP0603"))
    )
    (comp (ref "C191")
      (value "0.22uF")
      (footprint "eagle-import:C0402")
      (libsource (lib "eagle-import") (part "CAP0402"))
    )
    (comp (ref "C192")
      (value "0.1uF")
      (footprint "eagle-import:C0402")
      (libsource (lib "eagle-import") (part "CAP0402"))
    )
    (comp (ref "C193")
      (value "470pF")
      (footprint "eagle-import:C0402")
      (libsource (lib "eagle-import") (part "CAP0402"))
    )
    (comp (ref "C194")
      (value "4.7uF")
      (footprint "eagle-import:C0402")
      (libsource (lib "eagle-import") (part "CAP0402"))
    )
    (comp (ref "CN1")
      (value "1X06")
      (footprint "eagle-import:1X06")
      (libsource (lib "eagle-import") (part "1X06"))
    )
    (comp (ref "M11")
      (value "HMC5883LSMD")
      (footprint "eagle-import:16LPCC")
      (libsource (lib "eagle-import") (part "HMC5883LSMD"))
    )
    (comp (ref "M12")
      (value "HMC5883LSMD")
      (footprint "eagle-import:16LPCC")
      (libsource (lib "eagle-import") (part "HMC5883LSMD"))
    )
    (comp (ref "M13")
      (value "HMC5883LSMD")
      (footprint "eagle-import:16LPCC")
      (libsource (lib "eagle-import") (part "HMC5883LSMD"))
    )
    (comp (ref "M14")
      (value "HMC5883LSMD")
      (footprint "eagle-import:16LPCC")
      (libsource (lib "eagle-import") (part "HMC5883LSMD"))
    )
    (comp (ref "M15")
      (value "HMC5883LSMD")
      (footprint "eagle-import:16LPCC")
      (libsource (lib "eagle-import") (part "HMC5883LSMD"))
    )
    (comp (ref "M16")
      (value "HMC5883LSMD")
      (footprint "eagle-import:16LPCC")
      (libsource (lib "eagle-import") (part "HMC5883LSMD"))
    )
    (comp (ref "M17")
      (value "HMC5883LSMD")
      (footprint "eagle-import:16LPCC")
      (libsource (lib "eagle-import") (part "HMC5883LSMD"))
    )
    (comp (ref "M18")
      (value "HMC5883LSMD")
      (footprint "eagle-import:16LPCC")
      (libsource (lib "eagle-import") (part "HMC5883LSMD"))
    )
    (comp (ref "M21")
      (value "HMC5883LSMD")
      (footprint "eagle-import:16LPCC")
      (libsource (lib "eagle-import") (part "HMC5883LSMD"))
    )
    (comp (ref "M22")
      (value "HMC5883LSMD")
      (footprint "eagle-import:16LPCC")
      (libsource (lib "eagle-import") (part "HMC5883LSMD"))
    )
    (comp (ref "M23")
      (value "HMC5883LSMD")
      (footprint "eagle-import:16LPCC")
      (libsource (lib "eagle-import") (part "HMC5883LSMD"))
    )
    (comp (ref "M24")
      (value "HMC5883LSMD")
      (footprint "eagle-import:16LPCC")
      (libsource (lib "eagle-import") (part "HMC5883LSMD"))
    )
    (comp (ref "M25")
      (value "HMC5883LSMD")
      (footprint "eagle-import:16LPCC")
      (libsource (lib "eagle-import") (part "HMC5883LSMD"))
    )
    (comp (ref "M26")
      (value "HMC5883LSMD")
      (footprint "eagle-import:16LPCC")
      (libsource (lib "eagle-import") (part "HMC5883LSMD"))
    )
    (comp (ref "M27")
      (value "HMC5883LSMD")
      (footprint "eagle-import:16LPCC")
      (libsource (lib "eagle-import") (part "HMC5883LSMD"))
    )
    (comp (ref "M28")
      (value "HMC5883LSMD")
      (footprint "eagle-import:16LPCC")
      (libsource (lib "eagle-import") (part "HMC5883LSMD"))
    )
    (comp (ref "M31")
      (value "HMC5883LSMD")
      (footprint "eagle-import:16LPCC")
      (libsource (lib "eagle-import") (part "HMC5883LSMD"))
    )
    (comp (ref "M32")
      (value "HMC5883LSMD")
      (footprint "eagle-import:16LPCC")
      (libsource (lib "eagle-import") (part "HMC5883LSMD"))
    )
    (comp (ref "M33")
      (value "HMC5883LSMD")
      (footprint "eagle-import:16LPCC")
      (libsource (lib "eagle-import") (part "HMC5883LSMD"))
    )
    (comp (ref "M34")
      (value "HMC5883LSMD")
      (footprint "eagle-import:16LPCC")
      (libsource (lib "eagle-import") (part "HMC5883LSMD"))
    )
    (comp (ref "M35")
      (value "HMC5883LSMD")
      (footprint "eagle-import:16LPCC")
      (libsource (lib "eagle-import") (part "HMC5883LSMD"))
    )
    (comp (ref "M36")
      (value "HMC5883LSMD")
      (footprint "eagle-import:16LPCC")
      (libsource (lib "eagle-import") (part "HMC5883LSMD"))
    )
    (comp (ref "M37")
      (value "HMC5883LSMD")
      (footprint "eagle-import:16LPCC")
      (libsource (lib "eagle-import") (part "HMC5883LSMD"))
    )
    (comp (ref "M38")
      (value "HMC5883LSMD")
      (footprint "eagle-import:16LPCC")
      (libsource (lib "eagle-import") (part "HMC5883LSMD"))
    )
    (comp (ref "M41")
      (value "HMC5883LSMD")
      (footprint "eagle-import:16LPCC")
      (libsource (lib "eagle-import") (part "HMC5883LSMD"))
    )
    (comp (ref "M42")
      (value "HMC5883LSMD")
      (footprint "eagle-import:16LPCC")
      (libsource (lib "eagle-import") (part "HMC5883LSMD"))
    )
    (comp (ref "M43")
      (value "HMC5883LSMD")
      (footprint "eagle-import:16LPCC")
      (libsource (lib "eagle-import") (part "HMC5883LSMD"))
    )
    (comp (ref "M44")
      (value "HMC5883LSMD")
      (footprint "eagle-import:16LPCC")
      (libsource (lib "eagle-import") (part "HMC5883LSMD"))
    )
    (comp (ref "M45")
      (value "HMC5883LSMD")
      (footprint "eagle-import:16LPCC")
      (libsource (lib "eagle-import") (part "HMC5883LSMD"))
    )
    (comp (ref "M46")
      (value "HMC5883LSMD")
      (footprint "eagle-import:16LPCC")
      (libsource (lib "eagle-import") (part "HMC5883LSMD"))
    )
    (comp (ref "M47")
      (value "HMC5883LSMD")
      (footprint "eagle-import:16LPCC")
      (libsource (lib "eagle-import") (part "HMC5883LSMD"))
    )
    (comp (ref "M48")
      (value "HMC5883LSMD")
      (footprint "eagle-import:16LPCC")
      (libsource (lib "eagle-import") (part "HMC5883LSMD"))
    )
    (comp (ref "M51")
      (value "HMC5883LSMD")
      (footprint "eagle-import:16LPCC")
      (libsource (lib "eagle-import") (part "HMC5883LSMD"))
    )
    (comp (ref "M52")
      (value "HMC5883LSMD")
      (footprint "eagle-import:16LPCC")
      (libsource (lib "eagle-import") (part "HMC5883LSMD"))
    )
    (comp (ref "M53")
      (value "HMC5883LSMD")
      (footprint "eagle-import:16LPCC")
      (libsource (lib "eagle-import") (part "HMC5883LSMD"))
    )
    (comp (ref "M54")
      (value "HMC5883LSMD")
      (footprint "eagle-import:16LPCC")
      (libsource (lib "eagle-import") (part "HMC5883LSMD"))
    )
    (comp (ref "M55")
      (value "HMC5883LSMD")
      (footprint "eagle-import:16LPCC")
      (libsource (lib "eagle-import") (part "HMC5883LSMD"))
    )
    (comp (ref "M56")
      (value "HMC5883LSMD")
      (footprint "eagle-import:16LPCC")
      (libsource (lib "eagle-import") (part "HMC5883LSMD"))
    )
    (comp (ref "M57")
      (value "HMC5883LSMD")
      (footprint "eagle-import:16LPCC")
      (libsource (lib "eagle-import") (part "HMC5883LSMD"))
    )
    (comp (ref "M58")
      (value "HMC5883LSMD")
      (footprint "eagle-import:16LPCC")
      (libsource (lib "eagle-import") (part "HMC5883LSMD"))
    )
    (comp (ref "M61")
      (value "HMC5883LSMD")
      (footprint "eagle-import:16LPCC")
      (libsource (lib "eagle-import") (part "HMC5883LSMD"))
    )
    (comp (ref "M62")
      (value "HMC5883LSMD")
      (footprint "eagle-import:16LPCC")
      (libsource (lib "eagle-import") (part "HMC5883LSMD"))
    )
    (comp (ref "M63")
      (value "HMC5883LSMD")
      (footprint "eagle-import:16LPCC")
      (libsource (lib "eagle-import") (part "HMC5883LSMD"))
    )
    (comp (ref "M64")
      (value "HMC5883LSMD")
      (footprint "eagle-import:16LPCC")
      (libsource (lib "eagle-import") (part "HMC5883LSMD"))
    )
    (comp (ref "M65")
      (value "HMC5883LSMD")
      (footprint "eagle-import:16LPCC")
      (libsource (lib "eagle-import") (part "HMC5883LSMD"))
    )
    (comp (ref "M66")
      (value "HMC5883LSMD")
      (footprint "eagle-import:16LPCC")
      (libsource (lib "eagle-import") (part "HMC5883LSMD"))
    )
    (comp (ref "M67")
      (value "HMC5883LSMD")
      (footprint "eagle-import:16LPCC")
      (libsource (lib "eagle-import") (part "HMC5883LSMD"))
    )
    (comp (ref "M68")
      (value "HMC5883LSMD")
      (footprint "eagle-import:16LPCC")
      (libsource (lib "eagle-import") (part "HMC5883LSMD"))
    )
    (comp (ref "M71")
      (value "HMC5883LSMD")
      (footprint "eagle-import:16LPCC")
      (libsource (lib "eagle-import") (part "HMC5883LSMD"))
    )
    (comp (ref "M72")
      (value "HMC5883LSMD")
      (footprint "eagle-import:16LPCC")
      (libsource (lib "eagle-import") (part "HMC5883LSMD"))
    )
    (comp (ref "M73")
      (value "HMC5883LSMD")
      (footprint "eagle-import:16LPCC")
      (libsource (lib "eagle-import") (part "HMC5883LSMD"))
    )
    (comp (ref "M74")
      (value "HMC5883LSMD")
      (footprint "eagle-import:16LPCC")
      (libsource (lib "eagle-import") (part "HMC5883LSMD"))
    )
    (comp (ref "M75")
      (value "HMC5883LSMD")
      (footprint "eagle-import:16LPCC")
      (libsource (lib "eagle-import") (part "HMC5883LSMD"))
    )
    (comp (ref "M76")
      (value "HMC5883LSMD")
      (footprint "eagle-import:16LPCC")
      (libsource (lib "eagle-import") (part "HMC5883LSMD"))
    )
    (comp (ref "M77")
      (value "HMC5883LSMD")
      (footprint "eagle-import:16LPCC")
      (libsource (lib "eagle-import") (part "HMC5883LSMD"))
    )
    (comp (ref "M78")
      (value "HMC5883LSMD")
      (footprint "eagle-import:16LPCC")
      (libsource (lib "eagle-import") (part "HMC5883LSMD"))
    )
    (comp (ref "M81")
      (value "HMC5883LSMD")
      (footprint "eagle-import:16LPCC")
      (libsource (lib "eagle-import") (part "HMC5883LSMD"))
    )
    (comp (ref "M82")
      (value "HMC5883LSMD")
      (footprint "eagle-import:16LPCC")
      (libsource (lib "eagle-import") (part "HMC5883LSMD"))
    )
    (comp (ref "M83")
      (value "HMC5883LSMD")
      (footprint "eagle-import:16LPCC")
      (libsource (lib "eagle-import") (part "HMC5883LSMD"))
    )
    (comp (ref "M84")
      (value "HMC5883LSMD")
      (footprint "eagle-import:16LPCC")
      (libsource (lib "eagle-import") (part "HMC5883LSMD"))
    )
    (comp (ref "M85")
      (value "HMC5883LSMD")
      (footprint "eagle-import:16LPCC")
      (libsource (lib "eagle-import") (part "HMC5883LSMD"))
    )
    (comp (ref "M86")
      (value "HMC5883LSMD")
      (footprint "eagle-import:16LPCC")
      (libsource (lib "eagle-import") (part "HMC5883LSMD"))
    )
    (comp (ref "M87")
      (value "HMC5883LSMD")
      (footprint "eagle-import:16LPCC")
      (libsource (lib "eagle-import") (part "HMC5883LSMD"))
    )
    (comp (ref "M88")
      (value "HMC5883LSMD")
      (footprint "eagle-import:16LPCC")
      (libsource (lib "eagle-import") (part "HMC5883LSMD"))
    )
    (comp (ref "R1")
      (value "RESISTOR-ARRAY0603-ARV")
      (footprint "eagle-import:0603-ARV")
      (libsource (lib "eagle-import") (part "RESISTOR-ARRAY0603-ARV"))
    )
    (comp (ref "R2")
      (value "RESISTOR-ARRAY0603-ARV")
      (footprint "eagle-import:0603-ARV")
      (libsource (lib "eagle-import") (part "RESISTOR-ARRAY0603-ARV"))
    )
    (comp (ref "R3")
      (value "RESISTOR-ARRAY0603-ARV")
      (footprint "eagle-import:0603-ARV")
      (libsource (lib "eagle-import") (part "RESISTOR-ARRAY0603-ARV"))
    )
    (comp (ref "R4")
      (value "RESISTOR-ARRAY0603-ARV")
      (footprint "eagle-import:0603-ARV")
      (libsource (lib "eagle-import") (part "RESISTOR-ARRAY0603-ARV"))
    )
    (comp (ref "R5")
      (value "RESISTOR-ARRAY0603-ARV")
      (footprint "eagle-import:0603-ARV")
      (libsource (lib "eagle-import") (part "RESISTOR-ARRAY0603-ARV"))
    )
    (comp (ref "R6")
      (value "RESISTOR-ARRAY0603-ARV")
      (footprint "eagle-import:0603-ARV")
      (libsource (lib "eagle-import") (part "RESISTOR-ARRAY0603-ARV"))
    )
    (comp (ref "R7")
      (value "RESISTOR-ARRAY0603-ARV")
      (footprint "eagle-import:0603-ARV")
      (libsource (lib "eagle-import") (part "RESISTOR-ARRAY0603-ARV"))
    )
    (comp (ref "R8")
      (value "RESISTOR-ARRAY0603-ARV")
      (footprint "eagle-import:0603-ARV")
      (libsource (lib "eagle-import") (part "RESISTOR-ARRAY0603-ARV"))
    )
    (comp (ref "R9")
      (value "RESISTOR-ARRAY0603-ARV")
      (footprint "eagle-import:0603-ARV")
      (libsource (lib "eagle-import") (part "RESISTOR-ARRAY0603-ARV"))
    )
    (comp (ref "R10")
      (value "RESISTOR-ARRAY0603-ARV")
      (footprint "eagle-import:0603-ARV")
      (libsource (lib "eagle-import") (part "RESISTOR-ARRAY0603-ARV"))
    )
    (comp (ref "R11")
      (value "RESISTOR-ARRAY0603-ARV")
      (footprint "eagle-import:0603-ARV")
      (libsource (lib "eagle-import") (part "RESISTOR-ARRAY0603-ARV"))
    )
    (comp (ref "R12")
      (value "RESISTOR-ARRAY0603-ARV")
      (footprint "eagle-import:0603-ARV")
      (libsource (lib "eagle-import") (part "RESISTOR-ARRAY0603-ARV"))
    )
    (comp (ref "R13")
      (value "RESISTOR-ARRAY0603-ARV")
      (footprint "eagle-import:0603-ARV")
      (libsource (lib "eagle-import") (part "RESISTOR-ARRAY0603-ARV"))
    )
    (comp (ref "R14")
      (value "RESISTOR-ARRAY0603-ARV")
      (footprint "eagle-import:0603-ARV")
      (libsource (lib "eagle-import") (part "RESISTOR-ARRAY0603-ARV"))
    )
    (comp (ref "R15")
      (value "RESISTOR-ARRAY0603-ARV")
      (footprint "eagle-import:0603-ARV")
      (libsource (lib "eagle-import") (part "RESISTOR-ARRAY0603-ARV"))
    )
    (comp (ref "R16")
      (value "RESISTOR-ARRAY0603-ARV")
      (footprint "eagle-import:0603-ARV")
      (libsource (lib "eagle-import") (part "RESISTOR-ARRAY0603-ARV"))
    )
    (comp (ref "R17")
      (value "RESISTOR-ARRAY0603-ARV")
      (footprint "eagle-import:0603-ARV")
      (libsource (lib "eagle-import") (part "RESISTOR-ARRAY0603-ARV"))
    )
    (comp (ref "R18")
      (value "RESISTOR-ARRAY0603-ARV")
      (footprint "eagle-import:0603-ARV")
      (libsource (lib "eagle-import") (part "RESISTOR-ARRAY0603-ARV"))
    )
    (comp (ref "R19")
      (value "RESISTOR-ARRAY0603-ARV")
      (footprint "eagle-import:0603-ARV")
      (libsource (lib "eagle-import") (part "RESISTOR-ARRAY0603-ARV"))
    )
    (comp (ref "R20")
      (value "RESISTOR-ARRAY0603-ARV")
      (footprint "eagle-import:0603-ARV")
      (libsource (lib "eagle-import") (part "RESISTOR-ARRAY0603-ARV"))
    )
    (comp (ref "R21")
      (value "RESISTOR-ARRAY0603-ARV")
      (footprint "eagle-import:0603-ARV")
      (libsource (lib "eagle-import") (part "RESISTOR-ARRAY0603-ARV"))
    )
    (comp (ref "R22")
      (value "RESISTOR-ARRAY0603-ARV")
      (footprint "eagle-import:0603-ARV")
      (libsource (lib "eagle-import") (part "RESISTOR-ARRAY0603-ARV"))
    )
    (comp (ref "R23")
      (value "RESISTOR-ARRAY0603-ARV")
      (footprint "eagle-import:0603-ARV")
      (libsource (lib "eagle-import") (part "RESISTOR-ARRAY0603-ARV"))
    )
    (comp (ref "R24")
      (value "RESISTOR-ARRAY0603-ARV")
      (footprint "eagle-import:0603-ARV")
      (libsource (lib "eagle-import") (part "RESISTOR-ARRAY0603-ARV"))
    )
    (comp (ref "R25")
      (value "RESISTOR-ARRAY0603-ARV")
      (footprint "eagle-import:0603-ARV")
      (libsource (lib "eagle-import") (part "RESISTOR-ARRAY0603-ARV"))
    )
    (comp (ref "R26")
      (value "RESISTOR-ARRAY0603-ARV")
      (footprint "eagle-import:0603-ARV")
      (libsource (lib "eagle-import") (part "RESISTOR-ARRAY0603-ARV"))
    )
    (comp (ref "R27")
      (value "RESISTOR-ARRAY0603-ARV")
      (footprint "eagle-import:0603-ARV")
      (libsource (lib "eagle-import") (part "RESISTOR-ARRAY0603-ARV"))
    )
    (comp (ref "R28")
      (value "RESISTOR-ARRAY0603-ARV")
      (footprint "eagle-import:0603-ARV")
      (libsource (lib "eagle-import") (part "RESISTOR-ARRAY0603-ARV"))
    )
    (comp (ref "R29")
      (value "RESISTOR-ARRAY0603-ARV")
      (footprint "eagle-import:0603-ARV")
      (libsource (lib "eagle-import") (part "RESISTOR-ARRAY0603-ARV"))
    )
    (comp (ref "R30")
      (value "RESISTOR-ARRAY0603-ARV")
      (footprint "eagle-import:0603-ARV")
      (libsource (lib "eagle-import") (part "RESISTOR-ARRAY0603-ARV"))
    )
    (comp (ref "R31")
      (value "RESISTOR-ARRAY0603-ARV")
      (footprint "eagle-import:0603-ARV")
      (libsource (lib "eagle-import") (part "RESISTOR-ARRAY0603-ARV"))
    )
    (comp (ref "R32")
      (value "RESISTOR-ARRAY0603-ARV")
      (footprint "eagle-import:0603-ARV")
      (libsource (lib "eagle-import") (part "RESISTOR-ARRAY0603-ARV"))
    )
    (comp (ref "R33")
      (value "RESISTOR0603")
      (footprint "eagle-import:0603")
      (libsource (lib "eagle-import") (part "RESISTOR0603"))
    )
    (comp (ref "R34")
      (value "RESISTOR0603")
      (footprint "eagle-import:0603")
      (libsource (lib "eagle-import") (part "RESISTOR0603"))
    )
    (comp (ref "SJ1")
      (value "SOLDERJUMPER_2WAYPASTE1&2")
      (footprint "eagle-import:SJ_3_PASTE1&2")
      (libsource (lib "eagle-import") (part "SOLDERJUMPER_2WAYPASTE1&2"))
    )
    (comp (ref "U1")
      (value "TCA9548A")
      (footprint "eagle-import:TSSOP-24-4.4MM")
      (libsource (lib "eagle-import") (part "TCA9548A"))
    )
    (comp (ref "U2")
      (value "TCA9548A")
      (footprint "eagle-import:TSSOP-24-4.4MM")
      (libsource (lib "eagle-import") (part "TCA9548A"))
    )
    (comp (ref "U3")
      (value "TCA9548A")
      (footprint "eagle-import:TSSOP-24-4.4MM")
      (libsource (lib "eagle-import") (part "TCA9548A"))
    )
    (comp (ref "U4")
      (value "TCA9548A")
      (footprint "eagle-import:TSSOP-24-4.4MM")
      (libsource (lib "eagle-import") (part "TCA9548A"))
    )
    (comp (ref "U5")
      (value "TCA9548A")
      (footprint "eagle-import:TSSOP-24-4.4MM")
      (libsource (lib "eagle-import") (part "TCA9548A"))
    )
    (comp (ref "U6")
      (value "TCA9548A")
      (footprint "eagle-import:TSSOP-24-4.4MM")
      (libsource (lib "eagle-import") (part "TCA9548A"))
    )
    (comp (ref "U7")
      (value "TCA9548A")
      (footprint "eagle-import:TSSOP-24-4.4MM")
      (libsource (lib "eagle-import") (part "TCA9548A"))
    )
    (comp (ref "U8")
      (value "TCA9548A")
      (footprint "eagle-import:TSSOP-24-4.4MM")
      (libsource (lib "eagle-import") (part "TCA9548A"))
    )
    (comp (ref "U9")
      (value "MIC5205-3.3YM5")
      (footprint "eagle-import:SOT23-5")
      (libsource (lib "eagle-import") (part "V_REG_LDOSMD"))
    )
  )
  (nets
    (net (code "1") (name "/RESET") (class "Default")
      (node (ref "CN1") (pin "4") (pinfunction "4_4") (pintype "bidirectional"))
      (node (ref "U1") (pin "3") (pinfunction "RST#_3") (pintype "bidirectional"))
      (node (ref "U2") (pin "3") (pinfunction "RST#_3") (pintype "bidirectional"))
      (node (ref "U3") (pin "3") (pinfunction "RST#_3") (pintype "bidirectional"))
      (node (ref "U4") (pin "3") (pinfunction "RST#_3") (pintype "bidirectional"))
      (node (ref "U5") (pin "3") (pinfunction "RST#_3") (pintype "bidirectional"))
      (node (ref "U6") (pin "3") (pinfunction "RST#_3") (pintype "bidirectional"))
      (node (ref "U7") (pin "3") (pinfunction "RST#_3") (pintype "bidirectional"))
      (node (ref "U8") (pin "3") (pinfunction "RST#_3") (pintype "bidirectional"))
    )
    (net (code "2") (name "/SCL") (class "Default")
      (node (ref "CN1") (pin "2") (pinfunction "2_2") (pintype "bidirectional"))
      (node (ref "R34") (pin "1") (pinfunction "1_1") (pintype "passive"))
      (node (ref "U1") (pin "22") (pinfunction "SCL_22") (pintype "bidirectional"))
      (node (ref "U2") (pin "22") (pinfunction "SCL_22") (pintype "bidirectional"))
      (node (ref "U3") (pin "22") (pinfunction "SCL_22") (pintype "bidirectional"))
      (node (ref "U4") (pin "22") (pinfunction "SCL_22") (pintype "bidirectional"))
      (node (ref "U5") (pin "22") (pinfunction "SCL_22") (pintype "bidirectional"))
      (node (ref "U6") (pin "22") (pinfunction "SCL_22") (pintype "bidirectional"))
      (node (ref "U7") (pin "22") (pinfunction "SCL_22") (pintype "bidirectional"))
      (node (ref "U8") (pin "22") (pinfunction "SCL_22") (pintype "bidirectional"))
    )
    (net (code "3") (name "/SCL11") (class "Default")
      (node (ref "M11") (pin "1") (pinfunction "SCL_1") (pintype "bidirectional"))
      (node (ref "R3") (pin "5") (pinfunction "2_5") (pintype "passive"))
      (node (ref "U1") (pin "20") (pinfunction "SCL7_20") (pintype "bidirectional"))
    )
    (net (code "4") (name "/SCL12") (class "Default")
      (node (ref "M12") (pin "1") (pinfunction "SCL_1") (pintype "bidirectional"))
      (node (ref "R3") (pin "7") (pinfunction "2_7") (pintype "passive"))
      (node (ref "U1") (pin "18") (pinfunction "SCL6_18") (pintype "bidirectional"))
    )
    (net (code "5") (name "/SCL13") (class "Default")
      (node (ref "M13") (pin "1") (pinfunction "SCL_1") (pintype "bidirectional"))
      (node (ref "R4") (pin "5") (pinfunction "2_5") (pintype "passive"))
      (node (ref "U1") (pin "16") (pinfunction "SCL5_16") (pintype "bidirectional"))
    )
    (net (code "6") (name "/SCL14") (class "Default")
      (node (ref "M14") (pin "1") (pinfunction "SCL_1") (pintype "bidirectional"))
      (node (ref "R4") (pin "7") (pinfunction "2_7") (pintype "passive"))
      (node (ref "U1") (pin "14") (pinfunction "SCL4_14") (pintype "bidirectional"))
    )
    (net (code "7") (name "/SCL15") (class "Default")
      (node (ref "M15") (pin "1") (pinfunction "SCL_1") (pintype "bidirectional"))
      (node (ref "R1") (pin "3") (pinfunction "1_3") (pintype "passive"))
      (node (ref "U1") (pin "5") (pinfunction "SCL0_5") (pintype "bidirectional"))
    )
    (net (code "8") (name "/SCL16") (class "Default")
      (node (ref "M16") (pin "1") (pinfunction "SCL_1") (pintype "bidirectional"))
      (node (ref "R1") (pin "1") (pinfunction "1_1") (pintype "passive"))
      (node (ref "U1") (pin "7") (pinfunction "SCL1_7") (pintype "bidirectional"))
    )
    (net (code "9") (name "/SCL17") (class "Default")
      (node (ref "M17") (pin "1") (pinfunction "SCL_1") (pintype "bidirectional"))
      (node (ref "R2") (pin "3") (pinfunction "1_3") (pintype "passive"))
      (node (ref "U1") (pin "9") (pinfunction "SCL2_9") (pintype "bidirectional"))
    )
    (net (code "10") (name "/SCL18") (class "Default")
      (node (ref "M18") (pin "1") (pinfunction "SCL_1") (pintype "bidirectional"))
      (node (ref "R2") (pin "1") (pinfunction "1_1") (pintype "passive"))
      (node (ref "U1") (pin "11") (pinfunction "SCL3_11") (pintype "bidirectional"))
    )
    (net (code "11") (name "/SCL21") (class "Default")
      (node (ref "M21") (pin "1") (pinfunction "SCL_1") (pintype "bidirectional"))
      (node (ref "R7") (pin "5") (pinfunction "2_5") (pintype "passive"))
      (node (ref "U2") (pin "20") (pinfunction "SCL7_20") (pintype "bidirectional"))
    )
    (net (code "12") (name "/SCL22") (class "Default")
      (node (ref "M22") (pin "1") (pinfunction "SCL_1") (pintype "bidirectional"))
      (node (ref "R7") (pin "7") (pinfunction "2_7") (pintype "passive"))
      (node (ref "U2") (pin "18") (pinfunction "SCL6_18") (pintype "bidirectional"))
    )
    (net (code "13") (name "/SCL23") (class "Default")
      (node (ref "M23") (pin "1") (pinfunction "SCL_1") (pintype "bidirectional"))
      (node (ref "R8") (pin "5") (pinfunction "2_5") (pintype "passive"))
      (node (ref "U2") (pin "16") (pinfunction "SCL5_16") (pintype "bidirectional"))
    )
    (net (code "14") (name "/SCL24") (class "Default")
      (node (ref "M24") (pin "1") (pinfunction "SCL_1") (pintype "bidirectional"))
      (node (ref "R8") (pin "7") (pinfunction "2_7") (pintype "passive"))
      (node (ref "U2") (pin "14") (pinfunction "SCL4_14") (pintype "bidirectional"))
    )
    (net (code "15") (name "/SCL25") (class "Default")
      (node (ref "M25") (pin "1") (pinfunction "SCL_1") (pintype "bidirectional"))
      (node (ref "R5") (pin "3") (pinfunction "1_3") (pintype "passive"))
      (node (ref "U2") (pin "5") (pinfunction "SCL0_5") (pintype "bidirectional"))
    )
    (net (code "16") (name "/SCL26") (class "Default")
      (node (ref "M26") (pin "1") (pinfunction "SCL_1") (pintype "bidirectional"))
      (node (ref "R5") (pin "1") (pinfunction "1_1") (pintype "passive"))
      (node (ref "U2") (pin "7") (pinfunction "SCL1_7") (pintype "bidirectional"))
    )
    (net (code "17") (name "/SCL27") (class "Default")
      (node (ref "M27") (pin "1") (pinfunction "SCL_1") (pintype "bidirectional"))
      (node (ref "R6") (pin "3") (pinfunction "1_3") (pintype "passive"))
      (node (ref "U2") (pin "9") (pinfunction "SCL2_9") (pintype "bidirectional"))
    )
    (net (code "18") (name "/SCL28") (class "Default")
      (node (ref "M28") (pin "1") (pinfunction "SCL_1") (pintype "bidirectional"))
      (node (ref "R6") (pin "1") (pinfunction "1_1") (pintype "passive"))
      (node (ref "U2") (pin "11") (pinfunction "SCL3_11") (pintype "bidirectional"))
    )
    (net (code "19") (name "/SCL31") (class "Default")
      (node (ref "M31") (pin "1") (pinfunction "SCL_1") (pintype "bidirectional"))
      (node (ref "R11") (pin "5") (pinfunction "2_5") (pintype "passive"))
      (node (ref "U3") (pin "20") (pinfunction "SCL7_20") (pintype "bidirectional"))
    )
    (net (code "20") (name "/SCL32") (class "Default")
      (node (ref "M32") (pin "1") (pinfunction "SCL_1") (pintype "bidirectional"))
      (node (ref "R11") (pin "7") (pinfunction "2_7") (pintype "passive"))
      (node (ref "U3") (pin "18") (pinfunction "SCL6_18") (pintype "bidirectional"))
    )
    (net (code "21") (name "/SCL33") (class "Default")
      (node (ref "M33") (pin "1") (pinfunction "SCL_1") (pintype "bidirectional"))
      (node (ref "R12") (pin "5") (pinfunction "2_5") (pintype "passive"))
      (node (ref "U3") (pin "16") (pinfunction "SCL5_16") (pintype "bidirectional"))
    )
    (net (code "22") (name "/SCL34") (class "Default")
      (node (ref "M34") (pin "1") (pinfunction "SCL_1") (pintype "bidirectional"))
      (node (ref "R12") (pin "7") (pinfunction "2_7") (pintype "passive"))
      (node (ref "U3") (pin "14") (pinfunction "SCL4_14") (pintype "bidirectional"))
    )
    (net (code "23") (name "/SCL35") (class "Default")
      (node (ref "M35") (pin "1") (pinfunction "SCL_1") (pintype "bidirectional"))
      (node (ref "R9") (pin "3") (pinfunction "1_3") (pintype "passive"))
      (node (ref "U3") (pin "5") (pinfunction "SCL0_5") (pintype "bidirectional"))
    )
    (net (code "24") (name "/SCL36") (class "Default")
      (node (ref "M36") (pin "1") (pinfunction "SCL_1") (pintype "bidirectional"))
      (node (ref "R9") (pin "1") (pinfunction "1_1") (pintype "passive"))
      (node (ref "U3") (pin "7") (pinfunction "SCL1_7") (pintype "bidirectional"))
    )
    (net (code "25") (name "/SCL37") (class "Default")
      (node (ref "M37") (pin "1") (pinfunction "SCL_1") (pintype "bidirectional"))
      (node (ref "R10") (pin "3") (pinfunction "1_3") (pintype "passive"))
      (node (ref "U3") (pin "9") (pinfunction "SCL2_9") (pintype "bidirectional"))
    )
    (net (code "26") (name "/SCL38") (class "Default")
      (node (ref "M38") (pin "1") (pinfunction "SCL_1") (pintype "bidirectional"))
      (node (ref "R10") (pin "1") (pinfunction "1_1") (pintype "passive"))
      (node (ref "U3") (pin "11") (pinfunction "SCL3_11") (pintype "bidirectional"))
    )
    (net (code "27") (name "/SCL41") (class "Default")
      (node (ref "M41") (pin "1") (pinfunction "SCL_1") (pintype "bidirectional"))
      (node (ref "R15") (pin "5") (pinfunction "2_5") (pintype "passive"))
      (node (ref "U4") (pin "20") (pinfunction "SCL7_20") (pintype "bidirectional"))
    )
    (net (code "28") (name "/SCL42") (class "Default")
      (node (ref "M42") (pin "1") (pinfunction "SCL_1") (pintype "bidirectional"))
      (node (ref "R15") (pin "7") (pinfunction "2_7") (pintype "passive"))
      (node (ref "U4") (pin "18") (pinfunction "SCL6_18") (pintype "bidirectional"))
    )
    (net (code "29") (name "/SCL43") (class "Default")
      (node (ref "M43") (pin "1") (pinfunction "SCL_1") (pintype "bidirectional"))
      (node (ref "R16") (pin "5") (pinfunction "2_5") (pintype "passive"))
      (node (ref "U4") (pin "16") (pinfunction "SCL5_16") (pintype "bidirectional"))
    )
    (net (code "30") (name "/SCL44") (class "Default")
      (node (ref "M44") (pin "1") (pinfunction "SCL_1") (pintype "bidirectional"))
      (node (ref "R16") (pin "7") (pinfunction "2_7") (pintype "passive"))
      (node (ref "U4") (pin "14") (pinfunction "SCL4_14") (pintype "bidirectional"))
    )
    (net (code "31") (name "/SCL45") (class "Default")
      (node (ref "M45") (pin "1") (pinfunction "SCL_1") (pintype "bidirectional"))
      (node (ref "R13") (pin "3") (pinfunction "1_3") (pintype "passive"))
      (node (ref "U4") (pin "5") (pinfunction "SCL0_5") (pintype "bidirectional"))
    )
    (net (code "32") (name "/SCL46") (class "Default")
      (node (ref "M46") (pin "1") (pinfunction "SCL_1") (pintype "bidirectional"))
      (node (ref "R13") (pin "1") (pinfunction "1_1") (pintype "passive"))
      (node (ref "U4") (pin "7") (pinfunction "SCL1_7") (pintype "bidirectional"))
    )
    (net (code "33") (name "/SCL47") (class "Default")
      (node (ref "M47") (pin "1") (pinfunction "SCL_1") (pintype "bidirectional"))
      (node (ref "R14") (pin "3") (pinfunction "1_3") (pintype "passive"))
      (node (ref "U4") (pin "9") (pinfunction "SCL2_9") (pintype "bidirectional"))
    )
    (net (code "34") (name "/SCL48") (class "Default")
      (node (ref "M48") (pin "1") (pinfunction "SCL_1") (pintype "bidirectional"))
      (node (ref "R14") (pin "1") (pinfunction "1_1") (pintype "passive"))
      (node (ref "U4") (pin "11") (pinfunction "SCL3_11") (pintype "bidirectional"))
    )
    (net (code "35") (name "/SCL51") (class "Default")
      (node (ref "M51") (pin "1") (pinfunction "SCL_1") (pintype "bidirectional"))
      (node (ref "R19") (pin "5") (pinfunction "2_5") (pintype "passive"))
      (node (ref "U5") (pin "20") (pinfunction "SCL7_20") (pintype "bidirectional"))
    )
    (net (code "36") (name "/SCL52") (class "Default")
      (node (ref "M52") (pin "1") (pinfunction "SCL_1") (pintype "bidirectional"))
      (node (ref "R19") (pin "7") (pinfunction "2_7") (pintype "passive"))
      (node (ref "U5") (pin "18") (pinfunction "SCL6_18") (pintype "bidirectional"))
    )
    (net (code "37") (name "/SCL53") (class "Default")
      (node (ref "M53") (pin "1") (pinfunction "SCL_1") (pintype "bidirectional"))
      (node (ref "R20") (pin "5") (pinfunction "2_5") (pintype "passive"))
      (node (ref "U5") (pin "16") (pinfunction "SCL5_16") (pintype "bidirectional"))
    )
    (net (code "38") (name "/SCL54") (class "Default")
      (node (ref "M54") (pin "1") (pinfunction "SCL_1") (pintype "bidirectional"))
      (node (ref "R20") (pin "7") (pinfunction "2_7") (pintype "passive"))
      (node (ref "U5") (pin "14") (pinfunction "SCL4_14") (pintype "bidirectional"))
    )
    (net (code "39") (name "/SCL55") (class "Default")
      (node (ref "M55") (pin "1") (pinfunction "SCL_1") (pintype "bidirectional"))
      (node (ref "R17") (pin "3") (pinfunction "1_3") (pintype "passive"))
      (node (ref "U5") (pin "5") (pinfunction "SCL0_5") (pintype "bidirectional"))
    )
    (net (code "40") (name "/SCL56") (class "Default")
      (node (ref "M56") (pin "1") (pinfunction "SCL_1") (pintype "bidirectional"))
      (node (ref "R17") (pin "1") (pinfunction "1_1") (pintype "passive"))
      (node (ref "U5") (pin "7") (pinfunction "SCL1_7") (pintype "bidirectional"))
    )
    (net (code "41") (name "/SCL57") (class "Default")
      (node (ref "M57") (pin "1") (pinfunction "SCL_1") (pintype "bidirectional"))
      (node (ref "R18") (pin "3") (pinfunction "1_3") (pintype "passive"))
      (node (ref "U5") (pin "9") (pinfunction "SCL2_9") (pintype "bidirectional"))
    )
    (net (code "42") (name "/SCL58") (class "Default")
      (node (ref "M58") (pin "1") (pinfunction "SCL_1") (pintype "bidirectional"))
      (node (ref "R18") (pin "1") (pinfunction "1_1") (pintype "passive"))
      (node (ref "U5") (pin "11") (pinfunction "SCL3_11") (pintype "bidirectional"))
    )
    (net (code "43") (name "/SCL61") (class "Default")
      (node (ref "M61") (pin "1") (pinfunction "SCL_1") (pintype "bidirectional"))
      (node (ref "R23") (pin "5") (pinfunction "2_5") (pintype "passive"))
      (node (ref "U6") (pin "20") (pinfunction "SCL7_20") (pintype "bidirectional"))
    )
    (net (code "44") (name "/SCL62") (class "Default")
      (node (ref "M62") (pin "1") (pinfunction "SCL_1") (pintype "bidirectional"))
      (node (ref "R23") (pin "7") (pinfunction "2_7") (pintype "passive"))
      (node (ref "U6") (pin "18") (pinfunction "SCL6_18") (pintype "bidirectional"))
    )
    (net (code "45") (name "/SCL63") (class "Default")
      (node (ref "M63") (pin "1") (pinfunction "SCL_1") (pintype "bidirectional"))
      (node (ref "R24") (pin "5") (pinfunction "2_5") (pintype "passive"))
      (node (ref "U6") (pin "16") (pinfunction "SCL5_16") (pintype "bidirectional"))
    )
    (net (code "46") (name "/SCL64") (class "Default")
      (node (ref "M64") (pin "1") (pinfunction "SCL_1") (pintype "bidirectional"))
      (node (ref "R24") (pin "7") (pinfunction "2_7") (pintype "passive"))
      (node (ref "U6") (pin "14") (pinfunction "SCL4_14") (pintype "bidirectional"))
    )
    (net (code "47") (name "/SCL65") (class "Default")
      (node (ref "M65") (pin "1") (pinfunction "SCL_1") (pintype "bidirectional"))
      (node (ref "R21") (pin "3") (pinfunction "1_3") (pintype "passive"))
      (node (ref "U6") (pin "5") (pinfunction "SCL0_5") (pintype "bidirectional"))
    )
    (net (code "48") (name "/SCL66") (class "Default")
      (node (ref "M66") (pin "1") (pinfunction "SCL_1") (pintype "bidirectional"))
      (node (ref "R21") (pin "1") (pinfunction "1_1") (pintype "passive"))
      (node (ref "U6") (pin "7") (pinfunction "SCL1_7") (pintype "bidirectional"))
    )
    (net (code "49") (name "/SCL67") (class "Default")
      (node (ref "M67") (pin "1") (pinfunction "SCL_1") (pintype "bidirectional"))
      (node (ref "R22") (pin "3") (pinfunction "1_3") (pintype "passive"))
      (node (ref "U6") (pin "9") (pinfunction "SCL2_9") (pintype "bidirectional"))
    )
    (net (code "50") (name "/SCL68") (class "Default")
      (node (ref "M68") (pin "1") (pinfunction "SCL_1") (pintype "bidirectional"))
      (node (ref "R22") (pin "1") (pinfunction "1_1") (pintype "passive"))
      (node (ref "U6") (pin "11") (pinfunction "SCL3_11") (pintype "bidirectional"))
    )
    (net (code "51") (name "/SCL71") (class "Default")
      (node (ref "M71") (pin "1") (pinfunction "SCL_1") (pintype "bidirectional"))
      (node (ref "R27") (pin "5") (pinfunction "2_5") (pintype "passive"))
      (node (ref "U7") (pin "20") (pinfunction "SCL7_20") (pintype "bidirectional"))
    )
    (net (code "52") (name "/SCL72") (class "Default")
      (node (ref "M72") (pin "1") (pinfunction "SCL_1") (pintype "bidirectional"))
      (node (ref "R27") (pin "7") (pinfunction "2_7") (pintype "passive"))
      (node (ref "U7") (pin "18") (pinfunction "SCL6_18") (pintype "bidirectional"))
    )
    (net (code "53") (name "/SCL73") (class "Default")
      (node (ref "M73") (pin "1") (pinfunction "SCL_1") (pintype "bidirectional"))
      (node (ref "R28") (pin "5") (pinfunction "2_5") (pintype "passive"))
      (node (ref "U7") (pin "16") (pinfunction "SCL5_16") (pintype "bidirectional"))
    )
    (net (code "54") (name "/SCL74") (class "Default")
      (node (ref "M74") (pin "1") (pinfunction "SCL_1") (pintype "bidirectional"))
      (node (ref "R28") (pin "7") (pinfunction "2_7") (pintype "passive"))
      (node (ref "U7") (pin "14") (pinfunction "SCL4_14") (pintype "bidirectional"))
    )
    (net (code "55") (name "/SCL75") (class "Default")
      (node (ref "M75") (pin "1") (pinfunction "SCL_1") (pintype "bidirectional"))
      (node (ref "R25") (pin "3") (pinfunction "1_3") (pintype "passive"))
      (node (ref "U7") (pin "5") (pinfunction "SCL0_5") (pintype "bidirectional"))
    )
    (net (code "56") (name "/SCL76") (class "Default")
      (node (ref "M76") (pin "1") (pinfunction "SCL_1") (pintype "bidirectional"))
      (node (ref "R25") (pin "1") (pinfunction "1_1") (pintype "passive"))
      (node (ref "U7") (pin "7") (pinfunction "SCL1_7") (pintype "bidirectional"))
    )
    (net (code "57") (name "/SCL77") (class "Default")
      (node (ref "M77") (pin "1") (pinfunction "SCL_1") (pintype "bidirectional"))
      (node (ref "R26") (pin "3") (pinfunction "1_3") (pintype "passive"))
      (node (ref "U7") (pin "9") (pinfunction "SCL2_9") (pintype "bidirectional"))
    )
    (net (code "58") (name "/SCL78") (class "Default")
      (node (ref "M78") (pin "1") (pinfunction "SCL_1") (pintype "bidirectional"))
      (node (ref "R26") (pin "1") (pinfunction "1_1") (pintype "passive"))
      (node (ref "U7") (pin "11") (pinfunction "SCL3_11") (pintype "bidirectional"))
    )
    (net (code "59") (name "/SCL81") (class "Default")
      (node (ref "M81") (pin "1") (pinfunction "SCL_1") (pintype "bidirectional"))
      (node (ref "R31") (pin "5") (pinfunction "2_5") (pintype "passive"))
      (node (ref "U8") (pin "20") (pinfunction "SCL7_20") (pintype "bidirectional"))
    )
    (net (code "60") (name "/SCL82") (class "Default")
      (node (ref "M82") (pin "1") (pinfunction "SCL_1") (pintype "bidirectional"))
      (node (ref "R31") (pin "7") (pinfunction "2_7") (pintype "passive"))
      (node (ref "U8") (pin "18") (pinfunction "SCL6_18") (pintype "bidirectional"))
    )
    (net (code "61") (name "/SCL83") (class "Default")
      (node (ref "M83") (pin "1") (pinfunction "SCL_1") (pintype "bidirectional"))
      (node (ref "R32") (pin "5") (pinfunction "2_5") (pintype "passive"))
      (node (ref "U8") (pin "16") (pinfunction "SCL5_16") (pintype "bidirectional"))
    )
    (net (code "62") (name "/SCL84") (class "Default")
      (node (ref "M84") (pin "1") (pinfunction "SCL_1") (pintype "bidirectional"))
      (node (ref "R32") (pin "7") (pinfunction "2_7") (pintype "passive"))
      (node (ref "U8") (pin "14") (pinfunction "SCL4_14") (pintype "bidirectional"))
    )
    (net (code "63") (name "/SCL85") (class "Default")
      (node (ref "M85") (pin "1") (pinfunction "SCL_1") (pintype "bidirectional"))
      (node (ref "R29") (pin "3") (pinfunction "1_3") (pintype "passive"))
      (node (ref "U8") (pin "5") (pinfunction "SCL0_5") (pintype "bidirectional"))
    )
    (net (code "64") (name "/SCL86") (class "Default")
      (node (ref "M86") (pin "1") (pinfunction "SCL_1") (pintype "bidirectional"))
      (node (ref "R29") (pin "1") (pinfunction "1_1") (pintype "passive"))
      (node (ref "U8") (pin "7") (pinfunction "SCL1_7") (pintype "bidirectional"))
    )
    (net (code "65") (name "/SCL87") (class "Default")
      (node (ref "M87") (pin "1") (pinfunction "SCL_1") (pintype "bidirectional"))
      (node (ref "R30") (pin "3") (pinfunction "1_3") (pintype "passive"))
      (node (ref "U8") (pin "9") (pinfunction "SCL2_9") (pintype "bidirectional"))
    )
    (net (code "66") (name "/SCL88") (class "Default")
      (node (ref "M88") (pin "1") (pinfunction "SCL_1") (pintype "bidirectional"))
      (node (ref "R30") (pin "1") (pinfunction "1_1") (pintype "passive"))
      (node (ref "U8") (pin "11") (pinfunction "SCL3_11") (pintype "bidirectional"))
    )
    (net (code "67") (name "/SDA") (class "Default")
      (node (ref "CN1") (pin "3") (pinfunction "3_3") (pintype "bidirectional"))
      (node (ref "R33") (pin "1") (pinfunction "1_1") (pintype "passive"))
      (node (ref "U1") (pin "23") (pinfunction "SDA_23") (pintype "bidirectional"))
      (node (ref "U2") (pin "23") (pinfunction "SDA_23") (pintype "bidirectional"))
      (node (ref "U3") (pin "23") (pinfunction "SDA_23") (pintype "bidirectional"))
      (node (ref "U4") (pin "23") (pinfunction "SDA_23") (pintype "bidirectional"))
      (node (ref "U5") (pin "23") (pinfunction "SDA_23") (pintype "bidirectional"))
      (node (ref "U6") (pin "23") (pinfunction "SDA_23") (pintype "bidirectional"))
      (node (ref "U7") (pin "23") (pinfunction "SDA_23") (pintype "bidirectional"))
      (node (ref "U8") (pin "23") (pinfunction "SDA_23") (pintype "bidirectional"))
    )
    (net (code "68") (name "/SDA11") (class "Default")
      (node (ref "M11") (pin "16") (pinfunction "SDA_16") (pintype "bidirectional"))
      (node (ref "R3") (pin "6") (pinfunction "2_6") (pintype "passive"))
      (node (ref "U1") (pin "19") (pinfunction "SDA7_19") (pintype "bidirectional"))
    )
    (net (code "69") (name "/SDA12") (class "Default")
      (node (ref "M12") (pin "16") (pinfunction "SDA_16") (pintype "bidirectional"))
      (node (ref "R3") (pin "8") (pinfunction "2_8") (pintype "passive"))
      (node (ref "U1") (pin "17") (pinfunction "SDA6_17") (pintype "bidirectional"))
    )
    (net (code "70") (name "/SDA13") (class "Default")
      (node (ref "M13") (pin "16") (pinfunction "SDA_16") (pintype "bidirectional"))
      (node (ref "R4") (pin "6") (pinfunction "2_6") (pintype "passive"))
      (node (ref "U1") (pin "15") (pinfunction "SDA5_15") (pintype "bidirectional"))
    )
    (net (code "71") (name "/SDA14") (class "Default")
      (node (ref "M14") (pin "16") (pinfunction "SDA_16") (pintype "bidirectional"))
      (node (ref "R4") (pin "8") (pinfunction "2_8") (pintype "passive"))
      (node (ref "U1") (pin "13") (pinfunction "SDA4_13") (pintype "bidirectional"))
    )
    (net (code "72") (name "/SDA15") (class "Default")
      (node (ref "M15") (pin "16") (pinfunction "SDA_16") (pintype "bidirectional"))
      (node (ref "R1") (pin "4") (pinfunction "1_4") (pintype "passive"))
      (node (ref "U1") (pin "4") (pinfunction "SDA0_4") (pintype "bidirectional"))
    )
    (net (code "73") (name "/SDA16") (class "Default")
      (node (ref "M16") (pin "16") (pinfunction "SDA_16") (pintype "bidirectional"))
      (node (ref "R1") (pin "2") (pinfunction "1_2") (pintype "passive"))
      (node (ref "U1") (pin "6") (pinfunction "SDA1_6") (pintype "bidirectional"))
    )
    (net (code "74") (name "/SDA17") (class "Default")
      (node (ref "M17") (pin "16") (pinfunction "SDA_16") (pintype "bidirectional"))
      (node (ref "R2") (pin "4") (pinfunction "1_4") (pintype "passive"))
      (node (ref "U1") (pin "8") (pinfunction "SDA2_8") (pintype "bidirectional"))
    )
    (net (code "75") (name "/SDA18") (class "Default")
      (node (ref "M18") (pin "16") (pinfunction "SDA_16") (pintype "bidirectional"))
      (node (ref "R2") (pin "2") (pinfunction "1_2") (pintype "passive"))
      (node (ref "U1") (pin "10") (pinfunction "SDA3_10") (pintype "bidirectional"))
    )
    (net (code "76") (name "/SDA21") (class "Default")
      (node (ref "M21") (pin "16") (pinfunction "SDA_16") (pintype "bidirectional"))
      (node (ref "R7") (pin "6") (pinfunction "2_6") (pintype "passive"))
      (node (ref "U2") (pin "19") (pinfunction "SDA7_19") (pintype "bidirectional"))
    )
    (net (code "77") (name "/SDA22") (class "Default")
      (node (ref "M22") (pin "16") (pinfunction "SDA_16") (pintype "bidirectional"))
      (node (ref "R7") (pin "8") (pinfunction "2_8") (pintype "passive"))
      (node (ref "U2") (pin "17") (pinfunction "SDA6_17") (pintype "bidirectional"))
    )
    (net (code "78") (name "/SDA23") (class "Default")
      (node (ref "M23") (pin "16") (pinfunction "SDA_16") (pintype "bidirectional"))
      (node (ref "R8") (pin "6") (pinfunction "2_6") (pintype "passive"))
      (node (ref "U2") (pin "15") (pinfunction "SDA5_15") (pintype "bidirectional"))
    )
    (net (code "79") (name "/SDA24") (class "Default")
      (node (ref "M24") (pin "16") (pinfunction "SDA_16") (pintype "bidirectional"))
      (node (ref "R8") (pin "8") (pinfunction "2_8") (pintype "passive"))
      (node (ref "U2") (pin "13") (pinfunction "SDA4_13") (pintype "bidirectional"))
    )
    (net (code "80") (name "/SDA25") (class "Default")
      (node (ref "M25") (pin "16") (pinfunction "SDA_16") (pintype "bidirectional"))
      (node (ref "R5") (pin "4") (pinfunction "1_4") (pintype "passive"))
      (node (ref "U2") (pin "4") (pinfunction "SDA0_4") (pintype "bidirectional"))
    )
    (net (code "81") (name "/SDA26") (class "Default")
      (node (ref "M26") (pin "16") (pinfunction "SDA_16") (pintype "bidirectional"))
      (node (ref "R5") (pin "2") (pinfunction "1_2") (pintype "passive"))
      (node (ref "U2") (pin "6") (pinfunction "SDA1_6") (pintype "bidirectional"))
    )
    (net (code "82") (name "/SDA27") (class "Default")
      (node (ref "M27") (pin "16") (pinfunction "SDA_16") (pintype "bidirectional"))
      (node (ref "R6") (pin "4") (pinfunction "1_4") (pintype "passive"))
      (node (ref "U2") (pin "8") (pinfunction "SDA2_8") (pintype "bidirectional"))
    )
    (net (code "83") (name "/SDA28") (class "Default")
      (node (ref "M28") (pin "16") (pinfunction "SDA_16") (pintype "bidirectional"))
      (node (ref "R6") (pin "2") (pinfunction "1_2") (pintype "passive"))
      (node (ref "U2") (pin "10") (pinfunction "SDA3_10") (pintype "bidirectional"))
    )
    (net (code "84") (name "/SDA31") (class "Default")
      (node (ref "M31") (pin "16") (pinfunction "SDA_16") (pintype "bidirectional"))
      (node (ref "R11") (pin "6") (pinfunction "2_6") (pintype "passive"))
      (node (ref "U3") (pin "19") (pinfunction "SDA7_19") (pintype "bidirectional"))
    )
    (net (code "85") (name "/SDA32") (class "Default")
      (node (ref "M32") (pin "16") (pinfunction "SDA_16") (pintype "bidirectional"))
      (node (ref "R11") (pin "8") (pinfunction "2_8") (pintype "passive"))
      (node (ref "U3") (pin "17") (pinfunction "SDA6_17") (pintype "bidirectional"))
    )
    (net (code "86") (name "/SDA33") (class "Default")
      (node (ref "M33") (pin "16") (pinfunction "SDA_16") (pintype "bidirectional"))
      (node (ref "R12") (pin "6") (pinfunction "2_6") (pintype "passive"))
      (node (ref "U3") (pin "15") (pinfunction "SDA5_15") (pintype "bidirectional"))
    )
    (net (code "87") (name "/SDA34") (class "Default")
      (node (ref "M34") (pin "16") (pinfunction "SDA_16") (pintype "bidirectional"))
      (node (ref "R12") (pin "8") (pinfunction "2_8") (pintype "passive"))
      (node (ref "U3") (pin "13") (pinfunction "SDA4_13") (pintype "bidirectional"))
    )
    (net (code "88") (name "/SDA35") (class "Default")
      (node (ref "M35") (pin "16") (pinfunction "SDA_16") (pintype "bidirectional"))
      (node (ref "R9") (pin "4") (pinfunction "1_4") (pintype "passive"))
      (node (ref "U3") (pin "4") (pinfunction "SDA0_4") (pintype "bidirectional"))
    )
    (net (code "89") (name "/SDA36") (class "Default")
      (node (ref "M36") (pin "16") (pinfunction "SDA_16") (pintype "bidirectional"))
      (node (ref "R9") (pin "2") (pinfunction "1_2") (pintype "passive"))
      (node (ref "U3") (pin "6") (pinfunction "SDA1_6") (pintype "bidirectional"))
    )
    (net (code "90") (name "/SDA37") (class "Default")
      (node (ref "M37") (pin "16") (pinfunction "SDA_16") (pintype "bidirectional"))
      (node (ref "R10") (pin "4") (pinfunction "1_4") (pintype "passive"))
      (node (ref "U3") (pin "8") (pinfunction "SDA2_8") (pintype "bidirectional"))
    )
    (net (code "91") (name "/SDA38") (class "Default")
      (node (ref "M38") (pin "16") (pinfunction "SDA_16") (pintype "bidirectional"))
      (node (ref "R10") (pin "2") (pinfunction "1_2") (pintype "passive"))
      (node (ref "U3") (pin "10") (pinfunction "SDA3_10") (pintype "bidirectional"))
    )
    (net (code "92") (name "/SDA41") (class "Default")
      (node (ref "M41") (pin "16") (pinfunction "SDA_16") (pintype "bidirectional"))
      (node (ref "R15") (pin "6") (pinfunction "2_6") (pintype "passive"))
      (node (ref "U4") (pin "19") (pinfunction "SDA7_19") (pintype "bidirectional"))
    )
    (net (code "93") (name "/SDA42") (class "Default")
      (node (ref "M42") (pin "16") (pinfunction "SDA_16") (pintype "bidirectional"))
      (node (ref "R15") (pin "8") (pinfunction "2_8") (pintype "passive"))
      (node (ref "U4") (pin "17") (pinfunction "SDA6_17") (pintype "bidirectional"))
    )
    (net (code "94") (name "/SDA43") (class "Default")
      (node (ref "M43") (pin "16") (pinfunction "SDA_16") (pintype "bidirectional"))
      (node (ref "R16") (pin "6") (pinfunction "2_6") (pintype "passive"))
      (node (ref "U4") (pin "15") (pinfunction "SDA5_15") (pintype "bidirectional"))
    )
    (net (code "95") (name "/SDA44") (class "Default")
      (node (ref "M44") (pin "16") (pinfunction "SDA_16") (pintype "bidirectional"))
      (node (ref "R16") (pin "8") (pinfunction "2_8") (pintype "passive"))
      (node (ref "U4") (pin "13") (pinfunction "SDA4_13") (pintype "bidirectional"))
    )
    (net (code "96") (name "/SDA45") (class "Default")
      (node (ref "M45") (pin "16") (pinfunction "SDA_16") (pintype "bidirectional"))
      (node (ref "R13") (pin "4") (pinfunction "1_4") (pintype "passive"))
      (node (ref "U4") (pin "4") (pinfunction "SDA0_4") (pintype "bidirectional"))
    )
    (net (code "97") (name "/SDA46") (class "Default")
      (node (ref "M46") (pin "16") (pinfunction "SDA_16") (pintype "bidirectional"))
      (node (ref "R13") (pin "2") (pinfunction "1_2") (pintype "passive"))
      (node (ref "U4") (pin "6") (pinfunction "SDA1_6") (pintype "bidirectional"))
    )
    (net (code "98") (name "/SDA47") (class "Default")
      (node (ref "M47") (pin "16") (pinfunction "SDA_16") (pintype "bidirectional"))
      (node (ref "R14") (pin "4") (pinfunction "1_4") (pintype "passive"))
      (node (ref "U4") (pin "8") (pinfunction "SDA2_8") (pintype "bidirectional"))
    )
    (net (code "99") (name "/SDA48") (class "Default")
      (node (ref "M48") (pin "16") (pinfunction "SDA_16") (pintype "bidirectional"))
      (node (ref "R14") (pin "2") (pinfunction "1_2") (pintype "passive"))
      (node (ref "U4") (pin "10") (pinfunction "SDA3_10") (pintype "bidirectional"))
    )
    (net (code "100") (name "/SDA51") (class "Default")
      (node (ref "M51") (pin "16") (pinfunction "SDA_16") (pintype "bidirectional"))
      (node (ref "R19") (pin "6") (pinfunction "2_6") (pintype "passive"))
      (node (ref "U5") (pin "19") (pinfunction "SDA7_19") (pintype "bidirectional"))
    )
    (net (code "101") (name "/SDA52") (class "Default")
      (node (ref "M52") (pin "16") (pinfunction "SDA_16") (pintype "bidirectional"))
      (node (ref "R19") (pin "8") (pinfunction "2_8") (pintype "passive"))
      (node (ref "U5") (pin "17") (pinfunction "SDA6_17") (pintype "bidirectional"))
    )
    (net (code "102") (name "/SDA53") (class "Default")
      (node (ref "M53") (pin "16") (pinfunction "SDA_16") (pintype "bidirectional"))
      (node (ref "R20") (pin "6") (pinfunction "2_6") (pintype "passive"))
      (node (ref "U5") (pin "15") (pinfunction "SDA5_15") (pintype "bidirectional"))
    )
    (net (code "103") (name "/SDA54") (class "Default")
      (node (ref "M54") (pin "16") (pinfunction "SDA_16") (pintype "bidirectional"))
      (node (ref "R20") (pin "8") (pinfunction "2_8") (pintype "passive"))
      (node (ref "U5") (pin "13") (pinfunction "SDA4_13") (pintype "bidirectional"))
    )
    (net (code "104") (name "/SDA55") (class "Default")
      (node (ref "M55") (pin "16") (pinfunction "SDA_16") (pintype "bidirectional"))
      (node (ref "R17") (pin "4") (pinfunction "1_4") (pintype "passive"))
      (node (ref "U5") (pin "4") (pinfunction "SDA0_4") (pintype "bidirectional"))
    )
    (net (code "105") (name "/SDA56") (class "Default")
      (node (ref "M56") (pin "16") (pinfunction "SDA_16") (pintype "bidirectional"))
      (node (ref "R17") (pin "2") (pinfunction "1_2") (pintype "passive"))
      (node (ref "U5") (pin "6") (pinfunction "SDA1_6") (pintype "bidirectional"))
    )
    (net (code "106") (name "/SDA57") (class "Default")
      (node (ref "M57") (pin "16") (pinfunction "SDA_16") (pintype "bidirectional"))
      (node (ref "R18") (pin "4") (pinfunction "1_4") (pintype "passive"))
      (node (ref "U5") (pin "8") (pinfunction "SDA2_8") (pintype "bidirectional"))
    )
    (net (code "107") (name "/SDA58") (class "Default")
      (node (ref "M58") (pin "16") (pinfunction "SDA_16") (pintype "bidirectional"))
      (node (ref "R18") (pin "2") (pinfunction "1_2") (pintype "passive"))
      (node (ref "U5") (pin "10") (pinfunction "SDA3_10") (pintype "bidirectional"))
    )
    (net (code "108") (name "/SDA61") (class "Default")
      (node (ref "M61") (pin "16") (pinfunction "SDA_16") (pintype "bidirectional"))
      (node (ref "R23") (pin "6") (pinfunction "2_6") (pintype "passive"))
      (node (ref "U6") (pin "19") (pinfunction "SDA7_19") (pintype "bidirectional"))
    )
    (net (code "109") (name "/SDA62") (class "Default")
      (node (ref "M62") (pin "16") (pinfunction "SDA_16") (pintype "bidirectional"))
      (node (ref "R23") (pin "8") (pinfunction "2_8") (pintype "passive"))
      (node (ref "U6") (pin "17") (pinfunction "SDA6_17") (pintype "bidirectional"))
    )
    (net (code "110") (name "/SDA63") (class "Default")
      (node (ref "M63") (pin "16") (pinfunction "SDA_16") (pintype "bidirectional"))
      (node (ref "R24") (pin "6") (pinfunction "2_6") (pintype "passive"))
      (node (ref "U6") (pin "15") (pinfunction "SDA5_15") (pintype "bidirectional"))
    )
    (net (code "111") (name "/SDA64") (class "Default")
      (node (ref "M64") (pin "16") (pinfunction "SDA_16") (pintype "bidirectional"))
      (node (ref "R24") (pin "8") (pinfunction "2_8") (pintype "passive"))
      (node (ref "U6") (pin "13") (pinfunction "SDA4_13") (pintype "bidirectional"))
    )
    (net (code "112") (name "/SDA65") (class "Default")
      (node (ref "M65") (pin "16") (pinfunction "SDA_16") (pintype "bidirectional"))
      (node (ref "R21") (pin "4") (pinfunction "1_4") (pintype "passive"))
      (node (ref "U6") (pin "4") (pinfunction "SDA0_4") (pintype "bidirectional"))
    )
    (net (code "113") (name "/SDA66") (class "Default")
      (node (ref "M66") (pin "16") (pinfunction "SDA_16") (pintype "bidirectional"))
      (node (ref "R21") (pin "2") (pinfunction "1_2") (pintype "passive"))
      (node (ref "U6") (pin "6") (pinfunction "SDA1_6") (pintype "bidirectional"))
    )
    (net (code "114") (name "/SDA67") (class "Default")
      (node (ref "M67") (pin "16") (pinfunction "SDA_16") (pintype "bidirectional"))
      (node (ref "R22") (pin "4") (pinfunction "1_4") (pintype "passive"))
      (node (ref "U6") (pin "8") (pinfunction "SDA2_8") (pintype "bidirectional"))
    )
    (net (code "115") (name "/SDA68") (class "Default")
      (node (ref "M68") (pin "16") (pinfunction "SDA_16") (pintype "bidirectional"))
      (node (ref "R22") (pin "2") (pinfunction "1_2") (pintype "passive"))
      (node (ref "U6") (pin "10") (pinfunction "SDA3_10") (pintype "bidirectional"))
    )
    (net (code "116") (name "/SDA71") (class "Default")
      (node (ref "M71") (pin "16") (pinfunction "SDA_16") (pintype "bidirectional"))
      (node (ref "R27") (pin "6") (pinfunction "2_6") (pintype "passive"))
      (node (ref "U7") (pin "19") (pinfunction "SDA7_19") (pintype "bidirectional"))
    )
    (net (code "117") (name "/SDA72") (class "Default")
      (node (ref "M72") (pin "16") (pinfunction "SDA_16") (pintype "bidirectional"))
      (node (ref "R27") (pin "8") (pinfunction "2_8") (pintype "passive"))
      (node (ref "U7") (pin "17") (pinfunction "SDA6_17") (pintype "bidirectional"))
    )
    (net (code "118") (name "/SDA73") (class "Default")
      (node (ref "M73") (pin "16") (pinfunction "SDA_16") (pintype "bidirectional"))
      (node (ref "R28") (pin "6") (pinfunction "2_6") (pintype "passive"))
      (node (ref "U7") (pin "15") (pinfunction "SDA5_15") (pintype "bidirectional"))
    )
    (net (code "119") (name "/SDA74") (class "Default")
      (node (ref "M74") (pin "16") (pinfunction "SDA_16") (pintype "bidirectional"))
      (node (ref "R28") (pin "8") (pinfunction "2_8") (pintype "passive"))
      (node (ref "U7") (pin "13") (pinfunction "SDA4_13") (pintype "bidirectional"))
    )
    (net (code "120") (name "/SDA75") (class "Default")
      (node (ref "M75") (pin "16") (pinfunction "SDA_16") (pintype "bidirectional"))
      (node (ref "R25") (pin "4") (pinfunction "1_4") (pintype "passive"))
      (node (ref "U7") (pin "4") (pinfunction "SDA0_4") (pintype "bidirectional"))
    )
    (net (code "121") (name "/SDA76") (class "Default")
      (node (ref "M76") (pin "16") (pinfunction "SDA_16") (pintype "bidirectional"))
      (node (ref "R25") (pin "2") (pinfunction "1_2") (pintype "passive"))
      (node (ref "U7") (pin "6") (pinfunction "SDA1_6") (pintype "bidirectional"))
    )
    (net (code "122") (name "/SDA77") (class "Default")
      (node (ref "M77") (pin "16") (pinfunction "SDA_16") (pintype "bidirectional"))
      (node (ref "R26") (pin "4") (pinfunction "1_4") (pintype "passive"))
      (node (ref "U7") (pin "8") (pinfunction "SDA2_8") (pintype "bidirectional"))
    )
    (net (code "123") (name "/SDA78") (class "Default")
      (node (ref "M78") (pin "16") (pinfunction "SDA_16") (pintype "bidirectional"))
      (node (ref "R26") (pin "2") (pinfunction "1_2") (pintype "passive"))
      (node (ref "U7") (pin "10") (pinfunction "SDA3_10") (pintype "bidirectional"))
    )
    (net (code "124") (name "/SDA81") (class "Default")
      (node (ref "M81") (pin "16") (pinfunction "SDA_16") (pintype "bidirectional"))
      (node (ref "R31") (pin "6") (pinfunction "2_6") (pintype "passive"))
      (node (ref "U8") (pin "19") (pinfunction "SDA7_19") (pintype "bidirectional"))
    )
    (net (code "125") (name "/SDA82") (class "Default")
      (node (ref "M82") (pin "16") (pinfunction "SDA_16") (pintype "bidirectional"))
      (node (ref "R31") (pin "8") (pinfunction "2_8") (pintype "passive"))
      (node (ref "U8") (pin "17") (pinfunction "SDA6_17") (pintype "bidirectional"))
    )
    (net (code "126") (name "/SDA83") (class "Default")
      (node (ref "M83") (pin "16") (pinfunction "SDA_16") (pintype "bidirectional"))
      (node (ref "R32") (pin "6") (pinfunction "2_6") (pintype "passive"))
      (node (ref "U8") (pin "15") (pinfunction "SDA5_15") (pintype "bidirectional"))
    )
    (net (code "127") (name "/SDA84") (class "Default")
      (node (ref "M84") (pin "16") (pinfunction "SDA_16") (pintype "bidirectional"))
      (node (ref "R32") (pin "8") (pinfunction "2_8") (pintype "passive"))
      (node (ref "U8") (pin "13") (pinfunction "SDA4_13") (pintype "bidirectional"))
    )
    (net (code "128") (name "/SDA85") (class "Default")
      (node (ref "M85") (pin "16") (pinfunction "SDA_16") (pintype "bidirectional"))
      (node (ref "R29") (pin "4") (pinfunction "1_4") (pintype "passive"))
      (node (ref "U8") (pin "4") (pinfunction "SDA0_4") (pintype "bidirectional"))
    )
    (net (code "129") (name "/SDA86") (class "Default")
      (node (ref "M86") (pin "16") (pinfunction "SDA_16") (pintype "bidirectional"))
      (node (ref "R29") (pin "2") (pinfunction "1_2") (pintype "passive"))
      (node (ref "U8") (pin "6") (pinfunction "SDA1_6") (pintype "bidirectional"))
    )
    (net (code "130") (name "/SDA87") (class "Default")
      (node (ref "M87") (pin "16") (pinfunction "SDA_16") (pintype "bidirectional"))
      (node (ref "R30") (pin "4") (pinfunction "1_4") (pintype "passive"))
      (node (ref "U8") (pin "8") (pinfunction "SDA2_8") (pintype "bidirectional"))
    )
    (net (code "131") (name "/SDA88") (class "Default")
      (node (ref "M88") (pin "16") (pinfunction "SDA_16") (pintype "bidirectional"))
      (node (ref "R30") (pin "2") (pinfunction "1_2") (pintype "passive"))
      (node (ref "U8") (pin "10") (pinfunction "SDA3_10") (pintype "bidirectional"))
    )
    (net (code "132") (name "3.3V") (class "Default")
      (node (ref "C102") (pin "1") (pinfunction "1_1") (pintype "passive"))
      (node (ref "C105") (pin "1") (pinfunction "1_1") (pintype "passive"))
      (node (ref "C108") (pin "1") (pinfunction "1_1") (pintype "passive"))
      (node (ref "C111") (pin "1") (pinfunction "1_1") (pintype "passive"))
      (node (ref "C114") (pin "1") (pinfunction "1_1") (pintype "passive"))
      (node (ref "C117") (pin "1") (pinfunction "1_1") (pintype "passive"))
      (node (ref "C12") (pin "1") (pinfunction "1_1") (pintype "passive"))
      (node (ref "C120") (pin "1") (pinfunction "1_1") (pintype "passive"))
      (node (ref "C123") (pin "1") (pinfunction "1_1") (pintype "passive"))
      (node (ref "C126") (pin "1") (pinfunction "1_1") (pintype "passive"))
      (node (ref "C129") (pin "1") (pinfunction "1_1") (pintype "passive"))
      (node (ref "C132") (pin "1") (pinfunction "1_1") (pintype "passive"))
      (node (ref "C135") (pin "1") (pinfunction "1_1") (pintype "passive"))
      (node (ref "C138") (pin "1") (pinfunction "1_1") (pintype "passive"))
      (node (ref "C141") (pin "1") (pinfunction "1_1") (pintype "passive"))
      (node (ref "C144") (pin "1") (pinfunction "1_1") (pintype "passive"))
      (node (ref "C147") (pin "1") (pinfunction "1_1") (pintype "passive"))
      (node (ref "C15") (pin "1") (pinfunction "1_1") (pintype "passive"))
      (node (ref "C150") (pin "1") (pinfunction "1_1") (pintype "passive"))
      (node (ref "C153") (pin "1") (pinfunction "1_1") (pintype "passive"))
      (node (ref "C156") (pin "1") (pinfunction "1_1") (pintype "passive"))
      (node (ref "C159") (pin "1") (pinfunction "1_1") (pintype "passive"))
      (node (ref "C162") (pin "1") (pinfunction "1_1") (pintype "passive"))
      (node (ref "C165") (pin "1") (pinfunction "1_1") (pintype "passive"))
      (node (ref "C168") (pin "1") (pinfunction "1_1") (pintype "passive"))
      (node (ref "C171") (pin "1") (pinfunction "1_1") (pintype "passive"))
      (node (ref "C174") (pin "1") (pinfunction "1_1") (pintype "passive"))
      (node (ref "C177") (pin "1") (pinfunction "1_1") (pintype "passive"))
      (node (ref "C18") (pin "1") (pinfunction "1_1") (pintype "passive"))
      (node (ref "C180") (pin "1") (pinfunction "1_1") (pintype "passive"))
      (node (ref "C183") (pin "1") (pinfunction "1_1") (pintype "passive"))
      (node (ref "C186") (pin "1") (pinfunction "1_1") (pintype "passive"))
      (node (ref "C189") (pin "1") (pinfunction "1_1") (pintype "passive"))
      (node (ref "C192") (pin "1") (pinfunction "1_1") (pintype "passive"))
      (node (ref "C194") (pin "1") (pinfunction "1_1") (pintype "passive"))
      (node (ref "C21") (pin "1") (pinfunction "1_1") (pintype "passive"))
      (node (ref "C24") (pin "1") (pinfunction "1_1") (pintype "passive"))
      (node (ref "C27") (pin "1") (pinfunction "1_1") (pintype "passive"))
      (node (ref "C3") (pin "1") (pinfunction "1_1") (pintype "passive"))
      (node (ref "C30") (pin "1") (pinfunction "1_1") (pintype "passive"))
      (node (ref "C33") (pin "1") (pinfunction "1_1") (pintype "passive"))
      (node (ref "C36") (pin "1") (pinfunction "1_1") (pintype "passive"))
      (node (ref "C39") (pin "1") (pinfunction "1_1") (pintype "passive"))
      (node (ref "C42") (pin "1") (pinfunction "1_1") (pintype "passive"))
      (node (ref "C45") (pin "1") (pinfunction "1_1") (pintype "passive"))
      (node (ref "C48") (pin "1") (pinfunction "1_1") (pintype "passive"))
      (node (ref "C51") (pin "1") (pinfunction "1_1") (pintype "passive"))
      (node (ref "C54") (pin "1") (pinfunction "1_1") (pintype "passive"))
      (node (ref "C57") (pin "1") (pinfunction "1_1") (pintype "passive"))
      (node (ref "C6") (pin "1") (pinfunction "1_1") (pintype "passive"))
      (node (ref "C60") (pin "1") (pinfunction "1_1") (pintype "passive"))
      (node (ref "C63") (pin "1") (pinfunction "1_1") (pintype "passive"))
      (node (ref "C66") (pin "1") (pinfunction "1_1") (pintype "passive"))
      (node (ref "C69") (pin "1") (pinfunction "1_1") (pintype "passive"))
      (node (ref "C72") (pin "1") (pinfunction "1_1") (pintype "passive"))
      (node (ref "C75") (pin "1") (pinfunction "1_1") (pintype "passive"))
      (node (ref "C78") (pin "1") (pinfunction "1_1") (pintype "passive"))
      (node (ref "C81") (pin "1") (pinfunction "1_1") (pintype "passive"))
      (node (ref "C84") (pin "1") (pinfunction "1_1") (pintype "passive"))
      (node (ref "C87") (pin "1") (pinfunction "1_1") (pintype "passive"))
      (node (ref "C9") (pin "1") (pinfunction "1_1") (pintype "passive"))
      (node (ref "C90") (pin "1") (pinfunction "1_1") (pintype "passive"))
      (node (ref "C93") (pin "1") (pinfunction "1_1") (pintype "passive"))
      (node (ref "C96") (pin "1") (pinfunction "1_1") (pintype "passive"))
      (node (ref "C99") (pin "1") (pinfunction "1_1") (pintype "passive"))
      (node (ref "CN1") (pin "5") (pinfunction "5_5") (pintype "bidirectional"))
      (node (ref "M11") (pin "13") (pinfunction "VDDIO_13") (pintype "bidirectional"))
      (node (ref "M11") (pin "2") (pinfunction "VDD_2") (pintype "bidirectional"))
      (node (ref "M11") (pin "4") (pinfunction "S1_4") (pintype "bidirectional"))
      (node (ref "M12") (pin "13") (pinfunction "VDDIO_13") (pintype "bidirectional"))
      (node (ref "M12") (pin "2") (pinfunction "VDD_2") (pintype "bidirectional"))
      (node (ref "M12") (pin "4") (pinfunction "S1_4") (pintype "bidirectional"))
      (node (ref "M13") (pin "13") (pinfunction "VDDIO_13") (pintype "bidirectional"))
      (node (ref "M13") (pin "2") (pinfunction "VDD_2") (pintype "bidirectional"))
      (node (ref "M13") (pin "4") (pinfunction "S1_4") (pintype "bidirectional"))
      (node (ref "M14") (pin "13") (pinfunction "VDDIO_13") (pintype "bidirectional"))
      (node (ref "M14") (pin "2") (pinfunction "VDD_2") (pintype "bidirectional"))
      (node (ref "M14") (pin "4") (pinfunction "S1_4") (pintype "bidirectional"))
      (node (ref "M15") (pin "13") (pinfunction "VDDIO_13") (pintype "bidirectional"))
      (node (ref "M15") (pin "2") (pinfunction "VDD_2") (pintype "bidirectional"))
      (node (ref "M15") (pin "4") (pinfunction "S1_4") (pintype "bidirectional"))
      (node (ref "M16") (pin "13") (pinfunction "VDDIO_13") (pintype "bidirectional"))
      (node (ref "M16") (pin "2") (pinfunction "VDD_2") (pintype "bidirectional"))
      (node (ref "M16") (pin "4") (pinfunction "S1_4") (pintype "bidirectional"))
      (node (ref "M17") (pin "13") (pinfunction "VDDIO_13") (pintype "bidirectional"))
      (node (ref "M17") (pin "2") (pinfunction "VDD_2") (pintype "bidirectional"))
      (node (ref "M17") (pin "4") (pinfunction "S1_4") (pintype "bidirectional"))
      (node (ref "M18") (pin "13") (pinfunction "VDDIO_13") (pintype "bidirectional"))
      (node (ref "M18") (pin "2") (pinfunction "VDD_2") (pintype "bidirectional"))
      (node (ref "M18") (pin "4") (pinfunction "S1_4") (pintype "bidirectional"))
      (node (ref "M21") (pin "13") (pinfunction "VDDIO_13") (pintype "bidirectional"))
      (node (ref "M21") (pin "2") (pinfunction "VDD_2") (pintype "bidirectional"))
      (node (ref "M21") (pin "4") (pinfunction "S1_4") (pintype "bidirectional"))
      (node (ref "M22") (pin "13") (pinfunction "VDDIO_13") (pintype "bidirectional"))
      (node (ref "M22") (pin "2") (pinfunction "VDD_2") (pintype "bidirectional"))
      (node (ref "M22") (pin "4") (pinfunction "S1_4") (pintype "bidirectional"))
      (node (ref "M23") (pin "13") (pinfunction "VDDIO_13") (pintype "bidirectional"))
      (node (ref "M23") (pin "2") (pinfunction "VDD_2") (pintype "bidirectional"))
      (node (ref "M23") (pin "4") (pinfunction "S1_4") (pintype "bidirectional"))
      (node (ref "M24") (pin "13") (pinfunction "VDDIO_13") (pintype "bidirectional"))
      (node (ref "M24") (pin "2") (pinfunction "VDD_2") (pintype "bidirectional"))
      (node (ref "M24") (pin "4") (pinfunction "S1_4") (pintype "bidirectional"))
      (node (ref "M25") (pin "13") (pinfunction "VDDIO_13") (pintype "bidirectional"))
      (node (ref "M25") (pin "2") (pinfunction "VDD_2") (pintype "bidirectional"))
      (node (ref "M25") (pin "4") (pinfunction "S1_4") (pintype "bidirectional"))
      (node (ref "M26") (pin "13") (pinfunction "VDDIO_13") (pintype "bidirectional"))
      (node (ref "M26") (pin "2") (pinfunction "VDD_2") (pintype "bidirectional"))
      (node (ref "M26") (pin "4") (pinfunction "S1_4") (pintype "bidirectional"))
      (node (ref "M27") (pin "13") (pinfunction "VDDIO_13") (pintype "bidirectional"))
      (node (ref "M27") (pin "2") (pinfunction "VDD_2") (pintype "bidirectional"))
      (node (ref "M27") (pin "4") (pinfunction "S1_4") (pintype "bidirectional"))
      (node (ref "M28") (pin "13") (pinfunction "VDDIO_13") (pintype "bidirectional"))
      (node (ref "M28") (pin "2") (pinfunction "VDD_2") (pintype "bidirectional"))
      (node (ref "M28") (pin "4") (pinfunction "S1_4") (pintype "bidirectional"))
      (node (ref "M31") (pin "13") (pinfunction "VDDIO_13") (pintype "bidirectional"))
      (node (ref "M31") (pin "2") (pinfunction "VDD_2") (pintype "bidirectional"))
      (node (ref "M31") (pin "4") (pinfunction "S1_4") (pintype "bidirectional"))
      (node (ref "M32") (pin "13") (pinfunction "VDDIO_13") (pintype "bidirectional"))
      (node (ref "M32") (pin "2") (pinfunction "VDD_2") (pintype "bidirectional"))
      (node (ref "M32") (pin "4") (pinfunction "S1_4") (pintype "bidirectional"))
      (node (ref "M33") (pin "13") (pinfunction "VDDIO_13") (pintype "bidirectional"))
      (node (ref "M33") (pin "2") (pinfunction "VDD_2") (pintype "bidirectional"))
      (node (ref "M33") (pin "4") (pinfunction "S1_4") (pintype "bidirectional"))
      (node (ref "M34") (pin "13") (pinfunction "VDDIO_13") (pintype "bidirectional"))
      (node (ref "M34") (pin "2") (pinfunction "VDD_2") (pintype "bidirectional"))
      (node (ref "M34") (pin "4") (pinfunction "S1_4") (pintype "bidirectional"))
      (node (ref "M35") (pin "13") (pinfunction "VDDIO_13") (pintype "bidirectional"))
      (node (ref "M35") (pin "2") (pinfunction "VDD_2") (pintype "bidirectional"))
      (node (ref "M35") (pin "4") (pinfunction "S1_4") (pintype "bidirectional"))
      (node (ref "M36") (pin "13") (pinfunction "VDDIO_13") (pintype "bidirectional"))
      (node (ref "M36") (pin "2") (pinfunction "VDD_2") (pintype "bidirectional"))
      (node (ref "M36") (pin "4") (pinfunction "S1_4") (pintype "bidirectional"))
      (node (ref "M37") (pin "13") (pinfunction "VDDIO_13") (pintype "bidirectional"))
      (node (ref "M37") (pin "2") (pinfunction "VDD_2") (pintype "bidirectional"))
      (node (ref "M37") (pin "4") (pinfunction "S1_4") (pintype "bidirectional"))
      (node (ref "M38") (pin "13") (pinfunction "VDDIO_13") (pintype "bidirectional"))
      (node (ref "M38") (pin "2") (pinfunction "VDD_2") (pintype "bidirectional"))
      (node (ref "M38") (pin "4") (pinfunction "S1_4") (pintype "bidirectional"))
      (node (ref "M41") (pin "13") (pinfunction "VDDIO_13") (pintype "bidirectional"))
      (node (ref "M41") (pin "2") (pinfunction "VDD_2") (pintype "bidirectional"))
      (node (ref "M41") (pin "4") (pinfunction "S1_4") (pintype "bidirectional"))
      (node (ref "M42") (pin "13") (pinfunction "VDDIO_13") (pintype "bidirectional"))
      (node (ref "M42") (pin "2") (pinfunction "VDD_2") (pintype "bidirectional"))
      (node (ref "M42") (pin "4") (pinfunction "S1_4") (pintype "bidirectional"))
      (node (ref "M43") (pin "13") (pinfunction "VDDIO_13") (pintype "bidirectional"))
      (node (ref "M43") (pin "2") (pinfunction "VDD_2") (pintype "bidirectional"))
      (node (ref "M43") (pin "4") (pinfunction "S1_4") (pintype "bidirectional"))
      (node (ref "M44") (pin "13") (pinfunction "VDDIO_13") (pintype "bidirectional"))
      (node (ref "M44") (pin "2") (pinfunction "VDD_2") (pintype "bidirectional"))
      (node (ref "M44") (pin "4") (pinfunction "S1_4") (pintype "bidirectional"))
      (node (ref "M45") (pin "13") (pinfunction "VDDIO_13") (pintype "bidirectional"))
      (node (ref "M45") (pin "2") (pinfunction "VDD_2") (pintype "bidirectional"))
      (node (ref "M45") (pin "4") (pinfunction "S1_4") (pintype "bidirectional"))
      (node (ref "M46") (pin "13") (pinfunction "VDDIO_13") (pintype "bidirectional"))
      (node (ref "M46") (pin "2") (pinfunction "VDD_2") (pintype "bidirectional"))
      (node (ref "M46") (pin "4") (pinfunction "S1_4") (pintype "bidirectional"))
      (node (ref "M47") (pin "13") (pinfunction "VDDIO_13") (pintype "bidirectional"))
      (node (ref "M47") (pin "2") (pinfunction "VDD_2") (pintype "bidirectional"))
      (node (ref "M47") (pin "4") (pinfunction "S1_4") (pintype "bidirectional"))
      (node (ref "M48") (pin "13") (pinfunction "VDDIO_13") (pintype "bidirectional"))
      (node (ref "M48") (pin "2") (pinfunction "VDD_2") (pintype "bidirectional"))
      (node (ref "M48") (pin "4") (pinfunction "S1_4") (pintype "bidirectional"))
      (node (ref "M51") (pin "13") (pinfunction "VDDIO_13") (pintype "bidirectional"))
      (node (ref "M51") (pin "2") (pinfunction "VDD_2") (pintype "bidirectional"))
      (node (ref "M51") (pin "4") (pinfunction "S1_4") (pintype "bidirectional"))
      (node (ref "M52") (pin "13") (pinfunction "VDDIO_13") (pintype "bidirectional"))
      (node (ref "M52") (pin "2") (pinfunction "VDD_2") (pintype "bidirectional"))
      (node (ref "M52") (pin "4") (pinfunction "S1_4") (pintype "bidirectional"))
      (node (ref "M53") (pin "13") (pinfunction "VDDIO_13") (pintype "bidirectional"))
      (node (ref "M53") (pin "2") (pinfunction "VDD_2") (pintype "bidirectional"))
      (node (ref "M53") (pin "4") (pinfunction "S1_4") (pintype "bidirectional"))
      (node (ref "M54") (pin "13") (pinfunction "VDDIO_13") (pintype "bidirectional"))
      (node (ref "M54") (pin "2") (pinfunction "VDD_2") (pintype "bidirectional"))
      (node (ref "M54") (pin "4") (pinfunction "S1_4") (pintype "bidirectional"))
      (node (ref "M55") (pin "13") (pinfunction "VDDIO_13") (pintype "bidirectional"))
      (node (ref "M55") (pin "2") (pinfunction "VDD_2") (pintype "bidirectional"))
      (node (ref "M55") (pin "4") (pinfunction "S1_4") (pintype "bidirectional"))
      (node (ref "M56") (pin "13") (pinfunction "VDDIO_13") (pintype "bidirectional"))
      (node (ref "M56") (pin "2") (pinfunction "VDD_2") (pintype "bidirectional"))
      (node (ref "M56") (pin "4") (pinfunction "S1_4") (pintype "bidirectional"))
      (node (ref "M57") (pin "13") (pinfunction "VDDIO_13") (pintype "bidirectional"))
      (node (ref "M57") (pin "2") (pinfunction "VDD_2") (pintype "bidirectional"))
      (node (ref "M57") (pin "4") (pinfunction "S1_4") (pintype "bidirectional"))
      (node (ref "M58") (pin "13") (pinfunction "VDDIO_13") (pintype "bidirectional"))
      (node (ref "M58") (pin "2") (pinfunction "VDD_2") (pintype "bidirectional"))
      (node (ref "M58") (pin "4") (pinfunction "S1_4") (pintype "bidirectional"))
      (node (ref "M61") (pin "13") (pinfunction "VDDIO_13") (pintype "bidirectional"))
      (node (ref "M61") (pin "2") (pinfunction "VDD_2") (pintype "bidirectional"))
      (node (ref "M61") (pin "4") (pinfunction "S1_4") (pintype "bidirectional"))
      (node (ref "M62") (pin "13") (pinfunction "VDDIO_13") (pintype "bidirectional"))
      (node (ref "M62") (pin "2") (pinfunction "VDD_2") (pintype "bidirectional"))
      (node (ref "M62") (pin "4") (pinfunction "S1_4") (pintype "bidirectional"))
      (node (ref "M63") (pin "13") (pinfunction "VDDIO_13") (pintype "bidirectional"))
      (node (ref "M63") (pin "2") (pinfunction "VDD_2") (pintype "bidirectional"))
      (node (ref "M63") (pin "4") (pinfunction "S1_4") (pintype "bidirectional"))
      (node (ref "M64") (pin "13") (pinfunction "VDDIO_13") (pintype "bidirectional"))
      (node (ref "M64") (pin "2") (pinfunction "VDD_2") (pintype "bidirectional"))
      (node (ref "M64") (pin "4") (pinfunction "S1_4") (pintype "bidirectional"))
      (node (ref "M65") (pin "13") (pinfunction "VDDIO_13") (pintype "bidirectional"))
      (node (ref "M65") (pin "2") (pinfunction "VDD_2") (pintype "bidirectional"))
      (node (ref "M65") (pin "4") (pinfunction "S1_4") (pintype "bidirectional"))
      (node (ref "M66") (pin "13") (pinfunction "VDDIO_13") (pintype "bidirectional"))
      (node (ref "M66") (pin "2") (pinfunction "VDD_2") (pintype "bidirectional"))
      (node (ref "M66") (pin "4") (pinfunction "S1_4") (pintype "bidirectional"))
      (node (ref "M67") (pin "13") (pinfunction "VDDIO_13") (pintype "bidirectional"))
      (node (ref "M67") (pin "2") (pinfunction "VDD_2") (pintype "bidirectional"))
      (node (ref "M67") (pin "4") (pinfunction "S1_4") (pintype "bidirectional"))
      (node (ref "M68") (pin "13") (pinfunction "VDDIO_13") (pintype "bidirectional"))
      (node (ref "M68") (pin "2") (pinfunction "VDD_2") (pintype "bidirectional"))
      (node (ref "M68") (pin "4") (pinfunction "S1_4") (pintype "bidirectional"))
      (node (ref "M71") (pin "13") (pinfunction "VDDIO_13") (pintype "bidirectional"))
      (node (ref "M71") (pin "2") (pinfunction "VDD_2") (pintype "bidirectional"))
      (node (ref "M71") (pin "4") (pinfunction "S1_4") (pintype "bidirectional"))
      (node (ref "M72") (pin "13") (pinfunction "VDDIO_13") (pintype "bidirectional"))
      (node (ref "M72") (pin "2") (pinfunction "VDD_2") (pintype "bidirectional"))
      (node (ref "M72") (pin "4") (pinfunction "S1_4") (pintype "bidirectional"))
      (node (ref "M73") (pin "13") (pinfunction "VDDIO_13") (pintype "bidirectional"))
      (node (ref "M73") (pin "2") (pinfunction "VDD_2") (pintype "bidirectional"))
      (node (ref "M73") (pin "4") (pinfunction "S1_4") (pintype "bidirectional"))
      (node (ref "M74") (pin "13") (pinfunction "VDDIO_13") (pintype "bidirectional"))
      (node (ref "M74") (pin "2") (pinfunction "VDD_2") (pintype "bidirectional"))
      (node (ref "M74") (pin "4") (pinfunction "S1_4") (pintype "bidirectional"))
      (node (ref "M75") (pin "13") (pinfunction "VDDIO_13") (pintype "bidirectional"))
      (node (ref "M75") (pin "2") (pinfunction "VDD_2") (pintype "bidirectional"))
      (node (ref "M75") (pin "4") (pinfunction "S1_4") (pintype "bidirectional"))
      (node (ref "M76") (pin "13") (pinfunction "VDDIO_13") (pintype "bidirectional"))
      (node (ref "M76") (pin "2") (pinfunction "VDD_2") (pintype "bidirectional"))
      (node (ref "M76") (pin "4") (pinfunction "S1_4") (pintype "bidirectional"))
      (node (ref "M77") (pin "13") (pinfunction "VDDIO_13") (pintype "bidirectional"))
      (node (ref "M77") (pin "2") (pinfunction "VDD_2") (pintype "bidirectional"))
      (node (ref "M77") (pin "4") (pinfunction "S1_4") (pintype "bidirectional"))
      (node (ref "M78") (pin "13") (pinfunction "VDDIO_13") (pintype "bidirectional"))
      (node (ref "M78") (pin "2") (pinfunction "VDD_2") (pintype "bidirectional"))
      (node (ref "M78") (pin "4") (pinfunction "S1_4") (pintype "bidirectional"))
      (node (ref "M81") (pin "13") (pinfunction "VDDIO_13") (pintype "bidirectional"))
      (node (ref "M81") (pin "2") (pinfunction "VDD_2") (pintype "bidirectional"))
      (node (ref "M81") (pin "4") (pinfunction "S1_4") (pintype "bidirectional"))
      (node (ref "M82") (pin "13") (pinfunction "VDDIO_13") (pintype "bidirectional"))
      (node (ref "M82") (pin "2") (pinfunction "VDD_2") (pintype "bidirectional"))
      (node (ref "M82") (pin "4") (pinfunction "S1_4") (pintype "bidirectional"))
      (node (ref "M83") (pin "13") (pinfunction "VDDIO_13") (pintype "bidirectional"))
      (node (ref "M83") (pin "2") (pinfunction "VDD_2") (pintype "bidirectional"))
      (node (ref "M83") (pin "4") (pinfunction "S1_4") (pintype "bidirectional"))
      (node (ref "M84") (pin "13") (pinfunction "VDDIO_13") (pintype "bidirectional"))
      (node (ref "M84") (pin "2") (pinfunction "VDD_2") (pintype "bidirectional"))
      (node (ref "M84") (pin "4") (pinfunction "S1_4") (pintype "bidirectional"))
      (node (ref "M85") (pin "13") (pinfunction "VDDIO_13") (pintype "bidirectional"))
      (node (ref "M85") (pin "2") (pinfunction "VDD_2") (pintype "bidirectional"))
      (node (ref "M85") (pin "4") (pinfunction "S1_4") (pintype "bidirectional"))
      (node (ref "M86") (pin "13") (pinfunction "VDDIO_13") (pintype "bidirectional"))
      (node (ref "M86") (pin "2") (pinfunction "VDD_2") (pintype "bidirectional"))
      (node (ref "M86") (pin "4") (pinfunction "S1_4") (pintype "bidirectional"))
      (node (ref "M87") (pin "13") (pinfunction "VDDIO_13") (pintype "bidirectional"))
      (node (ref "M87") (pin "2") (pinfunction "VDD_2") (pintype "bidirectional"))
      (node (ref "M87") (pin "4") (pinfunction "S1_4") (pintype "bidirectional"))
      (node (ref "M88") (pin "13") (pinfunction "VDDIO_13") (pintype "bidirectional"))
      (node (ref "M88") (pin "2") (pinfunction "VDD_2") (pintype "bidirectional"))
      (node (ref "M88") (pin "4") (pinfunction "S1_4") (pintype "bidirectional"))
      (node (ref "R1") (pin "5") (pinfunction "2_5") (pintype "passive"))
      (node (ref "R1") (pin "6") (pinfunction "2_6") (pintype "passive"))
      (node (ref "R1") (pin "7") (pinfunction "2_7") (pintype "passive"))
      (node (ref "R1") (pin "8") (pinfunction "2_8") (pintype "passive"))
      (node (ref "R10") (pin "5") (pinfunction "2_5") (pintype "passive"))
      (node (ref "R10") (pin "6") (pinfunction "2_6") (pintype "passive"))
      (node (ref "R10") (pin "7") (pinfunction "2_7") (pintype "passive"))
      (node (ref "R10") (pin "8") (pinfunction "2_8") (pintype "passive"))
      (node (ref "R11") (pin "1") (pinfunction "1_1") (pintype "passive"))
      (node (ref "R11") (pin "2") (pinfunction "1_2") (pintype "passive"))
      (node (ref "R11") (pin "3") (pinfunction "1_3") (pintype "passive"))
      (node (ref "R11") (pin "4") (pinfunction "1_4") (pintype "passive"))
      (node (ref "R12") (pin "1") (pinfunction "1_1") (pintype "passive"))
      (node (ref "R12") (pin "2") (pinfunction "1_2") (pintype "passive"))
      (node (ref "R12") (pin "3") (pinfunction "1_3") (pintype "passive"))
      (node (ref "R12") (pin "4") (pinfunction "1_4") (pintype "passive"))
      (node (ref "R13") (pin "5") (pinfunction "2_5") (pintype "passive"))
      (node (ref "R13") (pin "6") (pinfunction "2_6") (pintype "passive"))
      (node (ref "R13") (pin "7") (pinfunction "2_7") (pintype "passive"))
      (node (ref "R13") (pin "8") (pinfunction "2_8") (pintype "passive"))
      (node (ref "R14") (pin "5") (pinfunction "2_5") (pintype "passive"))
      (node (ref "R14") (pin "6") (pinfunction "2_6") (pintype "passive"))
      (node (ref "R14") (pin "7") (pinfunction "2_7") (pintype "passive"))
      (node (ref "R14") (pin "8") (pinfunction "2_8") (pintype "passive"))
      (node (ref "R15") (pin "1") (pinfunction "1_1") (pintype "passive"))
      (node (ref "R15") (pin "2") (pinfunction "1_2") (pintype "passive"))
      (node (ref "R15") (pin "3") (pinfunction "1_3") (pintype "passive"))
      (node (ref "R15") (pin "4") (pinfunction "1_4") (pintype "passive"))
      (node (ref "R16") (pin "1") (pinfunction "1_1") (pintype "passive"))
      (node (ref "R16") (pin "2") (pinfunction "1_2") (pintype "passive"))
      (node (ref "R16") (pin "3") (pinfunction "1_3") (pintype "passive"))
      (node (ref "R16") (pin "4") (pinfunction "1_4") (pintype "passive"))
      (node (ref "R17") (pin "5") (pinfunction "2_5") (pintype "passive"))
      (node (ref "R17") (pin "6") (pinfunction "2_6") (pintype "passive"))
      (node (ref "R17") (pin "7") (pinfunction "2_7") (pintype "passive"))
      (node (ref "R17") (pin "8") (pinfunction "2_8") (pintype "passive"))
      (node (ref "R18") (pin "5") (pinfunction "2_5") (pintype "passive"))
      (node (ref "R18") (pin "6") (pinfunction "2_6") (pintype "passive"))
      (node (ref "R18") (pin "7") (pinfunction "2_7") (pintype "passive"))
      (node (ref "R18") (pin "8") (pinfunction "2_8") (pintype "passive"))
      (node (ref "R19") (pin "1") (pinfunction "1_1") (pintype "passive"))
      (node (ref "R19") (pin "2") (pinfunction "1_2") (pintype "passive"))
      (node (ref "R19") (pin "3") (pinfunction "1_3") (pintype "passive"))
      (node (ref "R19") (pin "4") (pinfunction "1_4") (pintype "passive"))
      (node (ref "R2") (pin "5") (pinfunction "2_5") (pintype "passive"))
      (node (ref "R2") (pin "6") (pinfunction "2_6") (pintype "passive"))
      (node (ref "R2") (pin "7") (pinfunction "2_7") (pintype "passive"))
      (node (ref "R2") (pin "8") (pinfunction "2_8") (pintype "passive"))
      (node (ref "R20") (pin "1") (pinfunction "1_1") (pintype "passive"))
      (node (ref "R20") (pin "2") (pinfunction "1_2") (pintype "passive"))
      (node (ref "R20") (pin "3") (pinfunction "1_3") (pintype "passive"))
      (node (ref "R20") (pin "4") (pinfunction "1_4") (pintype "passive"))
      (node (ref "R21") (pin "5") (pinfunction "2_5") (pintype "passive"))
      (node (ref "R21") (pin "6") (pinfunction "2_6") (pintype "passive"))
      (node (ref "R21") (pin "7") (pinfunction "2_7") (pintype "passive"))
      (node (ref "R21") (pin "8") (pinfunction "2_8") (pintype "passive"))
      (node (ref "R22") (pin "5") (pinfunction "2_5") (pintype "passive"))
      (node (ref "R22") (pin "6") (pinfunction "2_6") (pintype "passive"))
      (node (ref "R22") (pin "7") (pinfunction "2_7") (pintype "passive"))
      (node (ref "R22") (pin "8") (pinfunction "2_8") (pintype "passive"))
      (node (ref "R23") (pin "1") (pinfunction "1_1") (pintype "passive"))
      (node (ref "R23") (pin "2") (pinfunction "1_2") (pintype "passive"))
      (node (ref "R23") (pin "3") (pinfunction "1_3") (pintype "passive"))
      (node (ref "R23") (pin "4") (pinfunction "1_4") (pintype "passive"))
      (node (ref "R24") (pin "1") (pinfunction "1_1") (pintype "passive"))
      (node (ref "R24") (pin "2") (pinfunction "1_2") (pintype "passive"))
      (node (ref "R24") (pin "3") (pinfunction "1_3") (pintype "passive"))
      (node (ref "R24") (pin "4") (pinfunction "1_4") (pintype "passive"))
      (node (ref "R25") (pin "5") (pinfunction "2_5") (pintype "passive"))
      (node (ref "R25") (pin "6") (pinfunction "2_6") (pintype "passive"))
      (node (ref "R25") (pin "7") (pinfunction "2_7") (pintype "passive"))
      (node (ref "R25") (pin "8") (pinfunction "2_8") (pintype "passive"))
      (node (ref "R26") (pin "5") (pinfunction "2_5") (pintype "passive"))
      (node (ref "R26") (pin "6") (pinfunction "2_6") (pintype "passive"))
      (node (ref "R26") (pin "7") (pinfunction "2_7") (pintype "passive"))
      (node (ref "R26") (pin "8") (pinfunction "2_8") (pintype "passive"))
      (node (ref "R27") (pin "1") (pinfunction "1_1") (pintype "passive"))
      (node (ref "R27") (pin "2") (pinfunction "1_2") (pintype "passive"))
      (node (ref "R27") (pin "3") (pinfunction "1_3") (pintype "passive"))
      (node (ref "R27") (pin "4") (pinfunction "1_4") (pintype "passive"))
      (node (ref "R28") (pin "1") (pinfunction "1_1") (pintype "passive"))
      (node (ref "R28") (pin "2") (pinfunction "1_2") (pintype "passive"))
      (node (ref "R28") (pin "3") (pinfunction "1_3") (pintype "passive"))
      (node (ref "R28") (pin "4") (pinfunction "1_4") (pintype "passive"))
      (node (ref "R29") (pin "5") (pinfunction "2_5") (pintype "passive"))
      (node (ref "R29") (pin "6") (pinfunction "2_6") (pintype "passive"))
      (node (ref "R29") (pin "7") (pinfunction "2_7") (pintype "passive"))
      (node (ref "R29") (pin "8") (pinfunction "2_8") (pintype "passive"))
      (node (ref "R3") (pin "1") (pinfunction "1_1") (pintype "passive"))
      (node (ref "R3") (pin "2") (pinfunction "1_2") (pintype "passive"))
      (node (ref "R3") (pin "3") (pinfunction "1_3") (pintype "passive"))
      (node (ref "R3") (pin "4") (pinfunction "1_4") (pintype "passive"))
      (node (ref "R30") (pin "5") (pinfunction "2_5") (pintype "passive"))
      (node (ref "R30") (pin "6") (pinfunction "2_6") (pintype "passive"))
      (node (ref "R30") (pin "7") (pinfunction "2_7") (pintype "passive"))
      (node (ref "R30") (pin "8") (pinfunction "2_8") (pintype "passive"))
      (node (ref "R31") (pin "1") (pinfunction "1_1") (pintype "passive"))
      (node (ref "R31") (pin "2") (pinfunction "1_2") (pintype "passive"))
      (node (ref "R31") (pin "3") (pinfunction "1_3") (pintype "passive"))
      (node (ref "R31") (pin "4") (pinfunction "1_4") (pintype "passive"))
      (node (ref "R32") (pin "1") (pinfunction "1_1") (pintype "passive"))
      (node (ref "R32") (pin "2") (pinfunction "1_2") (pintype "passive"))
      (node (ref "R32") (pin "3") (pinfunction "1_3") (pintype "passive"))
      (node (ref "R32") (pin "4") (pinfunction "1_4") (pintype "passive"))
      (node (ref "R4") (pin "1") (pinfunction "1_1") (pintype "passive"))
      (node (ref "R4") (pin "2") (pinfunction "1_2") (pintype "passive"))
      (node (ref "R4") (pin "3") (pinfunction "1_3") (pintype "passive"))
      (node (ref "R4") (pin "4") (pinfunction "1_4") (pintype "passive"))
      (node (ref "R5") (pin "5") (pinfunction "2_5") (pintype "passive"))
      (node (ref "R5") (pin "6") (pinfunction "2_6") (pintype "passive"))
      (node (ref "R5") (pin "7") (pinfunction "2_7") (pintype "passive"))
      (node (ref "R5") (pin "8") (pinfunction "2_8") (pintype "passive"))
      (node (ref "R6") (pin "5") (pinfunction "2_5") (pintype "passive"))
      (node (ref "R6") (pin "6") (pinfunction "2_6") (pintype "passive"))
      (node (ref "R6") (pin "7") (pinfunction "2_7") (pintype "passive"))
      (node (ref "R6") (pin "8") (pinfunction "2_8") (pintype "passive"))
      (node (ref "R7") (pin "1") (pinfunction "1_1") (pintype "passive"))
      (node (ref "R7") (pin "2") (pinfunction "1_2") (pintype "passive"))
      (node (ref "R7") (pin "3") (pinfunction "1_3") (pintype "passive"))
      (node (ref "R7") (pin "4") (pinfunction "1_4") (pintype "passive"))
      (node (ref "R8") (pin "1") (pinfunction "1_1") (pintype "passive"))
      (node (ref "R8") (pin "2") (pinfunction "1_2") (pintype "passive"))
      (node (ref "R8") (pin "3") (pinfunction "1_3") (pintype "passive"))
      (node (ref "R8") (pin "4") (pinfunction "1_4") (pintype "passive"))
      (node (ref "R9") (pin "5") (pinfunction "2_5") (pintype "passive"))
      (node (ref "R9") (pin "6") (pinfunction "2_6") (pintype "passive"))
      (node (ref "R9") (pin "7") (pinfunction "2_7") (pintype "passive"))
      (node (ref "R9") (pin "8") (pinfunction "2_8") (pintype "passive"))
      (node (ref "SJ1") (pin "3") (pinfunction "3_3") (pintype "passive"))
      (node (ref "U1") (pin "24") (pinfunction "VCC_24") (pintype "bidirectional"))
      (node (ref "U2") (pin "1") (pinfunction "AD0_1") (pintype "bidirectional"))
      (node (ref "U2") (pin "24") (pinfunction "VCC_24") (pintype "bidirectional"))
      (node (ref "U3") (pin "2") (pinfunction "AD1_2") (pintype "bidirectional"))
      (node (ref "U3") (pin "24") (pinfunction "VCC_24") (pintype "bidirectional"))
      (node (ref "U4") (pin "1") (pinfunction "AD0_1") (pintype "bidirectional"))
      (node (ref "U4") (pin "2") (pinfunction "AD1_2") (pintype "bidirectional"))
      (node (ref "U4") (pin "24") (pinfunction "VCC_24") (pintype "bidirectional"))
      (node (ref "U5") (pin "21") (pinfunction "AD2_21") (pintype "bidirectional"))
      (node (ref "U5") (pin "24") (pinfunction "VCC_24") (pintype "bidirectional"))
      (node (ref "U6") (pin "1") (pinfunction "AD0_1") (pintype "bidirectional"))
      (node (ref "U6") (pin "21") (pinfunction "AD2_21") (pintype "bidirectional"))
      (node (ref "U6") (pin "24") (pinfunction "VCC_24") (pintype "bidirectional"))
      (node (ref "U7") (pin "2") (pinfunction "AD1_2") (pintype "bidirectional"))
      (node (ref "U7") (pin "21") (pinfunction "AD2_21") (pintype "bidirectional"))
      (node (ref "U7") (pin "24") (pinfunction "VCC_24") (pintype "bidirectional"))
      (node (ref "U8") (pin "1") (pinfunction "AD0_1") (pintype "bidirectional"))
      (node (ref "U8") (pin "2") (pinfunction "AD1_2") (pintype "bidirectional"))
      (node (ref "U8") (pin "21") (pinfunction "AD2_21") (pintype "bidirectional"))
      (node (ref "U8") (pin "24") (pinfunction "VCC_24") (pintype "bidirectional"))
      (node (ref "U9") (pin "5") (pinfunction "OUT_5") (pintype "passive"))
    )
    (net (code "133") (name "5V") (class "Default")
      (node (ref "CN1") (pin "6") (pinfunction "6_6") (pintype "bidirectional"))
      (node (ref "SJ1") (pin "1") (pinfunction "1_1") (pintype "passive"))
      (node (ref "U9") (pin "1") (pinfunction "IN_1") (pintype "input"))
      (node (ref "U9") (pin "3") (pinfunction "EN_3") (pintype "input"))
    )
    (net (code "134") (name "GND") (class "Default")
      (node (ref "C1") (pin "2") (pinfunction "2_2") (pintype "passive"))
      (node (ref "C10") (pin "2") (pinfunction "2_2") (pintype "passive"))
      (node (ref "C100") (pin "2") (pinfunction "2_2") (pintype "passive"))
      (node (ref "C102") (pin "2") (pinfunction "2_2") (pintype "passive"))
      (node (ref "C103") (pin "2") (pinfunction "2_2") (pintype "passive"))
      (node (ref "C105") (pin "2") (pinfunction "2_2") (pintype "passive"))
      (node (ref "C106") (pin "2") (pinfunction "2_2") (pintype "passive"))
      (node (ref "C108") (pin "2") (pinfunction "2_2") (pintype "passive"))
      (node (ref "C109") (pin "2") (pinfunction "2_2") (pintype "passive"))
      (node (ref "C111") (pin "2") (pinfunction "2_2") (pintype "passive"))
      (node (ref "C112") (pin "2") (pinfunction "2_2") (pintype "passive"))
      (node (ref "C114") (pin "2") (pinfunction "2_2") (pintype "passive"))
      (node (ref "C115") (pin "2") (pinfunction "2_2") (pintype "passive"))
      (node (ref "C117") (pin "2") (pinfunction "2_2") (pintype "passive"))
      (node (ref "C118") (pin "2") (pinfunction "2_2") (pintype "passive"))
      (node (ref "C12") (pin "2") (pinfunction "2_2") (pintype "passive"))
      (node (ref "C120") (pin "2") (pinfunction "2_2") (pintype "passive"))
      (node (ref "C121") (pin "2") (pinfunction "2_2") (pintype "passive"))
      (node (ref "C123") (pin "2") (pinfunction "2_2") (pintype "passive"))
      (node (ref "C124") (pin "2") (pinfunction "2_2") (pintype "passive"))
      (node (ref "C126") (pin "2") (pinfunction "2_2") (pintype "passive"))
      (node (ref "C127") (pin "2") (pinfunction "2_2") (pintype "passive"))
      (node (ref "C129") (pin "2") (pinfunction "2_2") (pintype "passive"))
      (node (ref "C13") (pin "2") (pinfunction "2_2") (pintype "passive"))
      (node (ref "C130") (pin "2") (pinfunction "2_2") (pintype "passive"))
      (node (ref "C132") (pin "2") (pinfunction "2_2") (pintype "passive"))
      (node (ref "C133") (pin "2") (pinfunction "2_2") (pintype "passive"))
      (node (ref "C135") (pin "2") (pinfunction "2_2") (pintype "passive"))
      (node (ref "C136") (pin "2") (pinfunction "2_2") (pintype "passive"))
      (node (ref "C138") (pin "2") (pinfunction "2_2") (pintype "passive"))
      (node (ref "C139") (pin "2") (pinfunction "2_2") (pintype "passive"))
      (node (ref "C141") (pin "2") (pinfunction "2_2") (pintype "passive"))
      (node (ref "C142") (pin "2") (pinfunction "2_2") (pintype "passive"))
      (node (ref "C144") (pin "2") (pinfunction "2_2") (pintype "passive"))
      (node (ref "C145") (pin "2") (pinfunction "2_2") (pintype "passive"))
      (node (ref "C147") (pin "2") (pinfunction "2_2") (pintype "passive"))
      (node (ref "C148") (pin "2") (pinfunction "2_2") (pintype "passive"))
      (node (ref "C15") (pin "2") (pinfunction "2_2") (pintype "passive"))
      (node (ref "C150") (pin "2") (pinfunction "2_2") (pintype "passive"))
      (node (ref "C151") (pin "2") (pinfunction "2_2") (pintype "passive"))
      (node (ref "C153") (pin "2") (pinfunction "2_2") (pintype "passive"))
      (node (ref "C154") (pin "2") (pinfunction "2_2") (pintype "passive"))
      (node (ref "C156") (pin "2") (pinfunction "2_2") (pintype "passive"))
      (node (ref "C157") (pin "2") (pinfunction "2_2") (pintype "passive"))
      (node (ref "C159") (pin "2") (pinfunction "2_2") (pintype "passive"))
      (node (ref "C16") (pin "2") (pinfunction "2_2") (pintype "passive"))
      (node (ref "C160") (pin "2") (pinfunction "2_2") (pintype "passive"))
      (node (ref "C162") (pin "2") (pinfunction "2_2") (pintype "passive"))
      (node (ref "C163") (pin "2") (pinfunction "2_2") (pintype "passive"))
      (node (ref "C165") (pin "2") (pinfunction "2_2") (pintype "passive"))
      (node (ref "C166") (pin "2") (pinfunction "2_2") (pintype "passive"))
      (node (ref "C168") (pin "2") (pinfunction "2_2") (pintype "passive"))
      (node (ref "C169") (pin "2") (pinfunction "2_2") (pintype "passive"))
      (node (ref "C171") (pin "2") (pinfunction "2_2") (pintype "passive"))
      (node (ref "C172") (pin "2") (pinfunction "2_2") (pintype "passive"))
      (node (ref "C174") (pin "2") (pinfunction "2_2") (pintype "passive"))
      (node (ref "C175") (pin "2") (pinfunction "2_2") (pintype "passive"))
      (node (ref "C177") (pin "2") (pinfunction "2_2") (pintype "passive"))
      (node (ref "C178") (pin "2") (pinfunction "2_2") (pintype "passive"))
      (node (ref "C18") (pin "2") (pinfunction "2_2") (pintype "passive"))
      (node (ref "C180") (pin "2") (pinfunction "2_2") (pintype "passive"))
      (node (ref "C181") (pin "2") (pinfunction "2_2") (pintype "passive"))
      (node (ref "C183") (pin "2") (pinfunction "2_2") (pintype "passive"))
      (node (ref "C184") (pin "2") (pinfunction "2_2") (pintype "passive"))
      (node (ref "C186") (pin "2") (pinfunction "2_2") (pintype "passive"))
      (node (ref "C187") (pin "2") (pinfunction "2_2") (pintype "passive"))
      (node (ref "C189") (pin "2") (pinfunction "2_2") (pintype "passive"))
      (node (ref "C19") (pin "2") (pinfunction "2_2") (pintype "passive"))
      (node (ref "C190") (pin "2") (pinfunction "2_2") (pintype "passive"))
      (node (ref "C192") (pin "2") (pinfunction "2_2") (pintype "passive"))
      (node (ref "C193") (pin "2") (pinfunction "2_2") (pintype "passive"))
      (node (ref "C194") (pin "2") (pinfunction "2_2") (pintype "passive"))
      (node (ref "C21") (pin "2") (pinfunction "2_2") (pintype "passive"))
      (node (ref "C22") (pin "2") (pinfunction "2_2") (pintype "passive"))
      (node (ref "C24") (pin "2") (pinfunction "2_2") (pintype "passive"))
      (node (ref "C25") (pin "2") (pinfunction "2_2") (pintype "passive"))
      (node (ref "C27") (pin "2") (pinfunction "2_2") (pintype "passive"))
      (node (ref "C28") (pin "2") (pinfunction "2_2") (pintype "passive"))
      (node (ref "C3") (pin "2") (pinfunction "2_2") (pintype "passive"))
      (node (ref "C30") (pin "2") (pinfunction "2_2") (pintype "passive"))
      (node (ref "C31") (pin "2") (pinfunction "2_2") (pintype "passive"))
      (node (ref "C33") (pin "2") (pinfunction "2_2") (pintype "passive"))
      (node (ref "C34") (pin "2") (pinfunction "2_2") (pintype "passive"))
      (node (ref "C36") (pin "2") (pinfunction "2_2") (pintype "passive"))
      (node (ref "C37") (pin "2") (pinfunction "2_2") (pintype "passive"))
      (node (ref "C39") (pin "2") (pinfunction "2_2") (pintype "passive"))
      (node (ref "C4") (pin "2") (pinfunction "2_2") (pintype "passive"))
      (node (ref "C40") (pin "2") (pinfunction "2_2") (pintype "passive"))
      (node (ref "C42") (pin "2") (pinfunction "2_2") (pintype "passive"))
      (node (ref "C43") (pin "2") (pinfunction "2_2") (pintype "passive"))
      (node (ref "C45") (pin "2") (pinfunction "2_2") (pintype "passive"))
      (node (ref "C46") (pin "2") (pinfunction "2_2") (pintype "passive"))
      (node (ref "C48") (pin "2") (pinfunction "2_2") (pintype "passive"))
      (node (ref "C49") (pin "2") (pinfunction "2_2") (pintype "passive"))
      (node (ref "C51") (pin "2") (pinfunction "2_2") (pintype "passive"))
      (node (ref "C52") (pin "2") (pinfunction "2_2") (pintype "passive"))
      (node (ref "C54") (pin "2") (pinfunction "2_2") (pintype "passive"))
      (node (ref "C55") (pin "2") (pinfunction "2_2") (pintype "passive"))
      (node (ref "C57") (pin "2") (pinfunction "2_2") (pintype "passive"))
      (node (ref "C58") (pin "2") (pinfunction "2_2") (pintype "passive"))
      (node (ref "C6") (pin "2") (pinfunction "2_2") (pintype "passive"))
      (node (ref "C60") (pin "2") (pinfunction "2_2") (pintype "passive"))
      (node (ref "C61") (pin "2") (pinfunction "2_2") (pintype "passive"))
      (node (ref "C63") (pin "2") (pinfunction "2_2") (pintype "passive"))
      (node (ref "C64") (pin "2") (pinfunction "2_2") (pintype "passive"))
      (node (ref "C66") (pin "2") (pinfunction "2_2") (pintype "passive"))
      (node (ref "C67") (pin "2") (pinfunction "2_2") (pintype "passive"))
      (node (ref "C69") (pin "2") (pinfunction "2_2") (pintype "passive"))
      (node (ref "C7") (pin "2") (pinfunction "2_2") (pintype "passive"))
      (node (ref "C70") (pin "2") (pinfunction "2_2") (pintype "passive"))
      (node (ref "C72") (pin "2") (pinfunction "2_2") (pintype "passive"))
      (node (ref "C73") (pin "2") (pinfunction "2_2") (pintype "passive"))
      (node (ref "C75") (pin "2") (pinfunction "2_2") (pintype "passive"))
      (node (ref "C76") (pin "2") (pinfunction "2_2") (pintype "passive"))
      (node (ref "C78") (pin "2") (pinfunction "2_2") (pintype "passive"))
      (node (ref "C79") (pin "2") (pinfunction "2_2") (pintype "passive"))
      (node (ref "C81") (pin "2") (pinfunction "2_2") (pintype "passive"))
      (node (ref "C82") (pin "2") (pinfunction "2_2") (pintype "passive"))
      (node (ref "C84") (pin "2") (pinfunction "2_2") (pintype "passive"))
      (node (ref "C85") (pin "2") (pinfunction "2_2") (pintype "passive"))
      (node (ref "C87") (pin "2") (pinfunction "2_2") (pintype "passive"))
      (node (ref "C88") (pin "2") (pinfunction "2_2") (pintype "passive"))
      (node (ref "C9") (pin "2") (pinfunction "2_2") (pintype "passive"))
      (node (ref "C90") (pin "2") (pinfunction "2_2") (pintype "passive"))
      (node (ref "C91") (pin "2") (pinfunction "2_2") (pintype "passive"))
      (node (ref "C93") (pin "2") (pinfunction "2_2") (pintype "passive"))
      (node (ref "C94") (pin "2") (pinfunction "2_2") (pintype "passive"))
      (node (ref "C96") (pin "2") (pinfunction "2_2") (pintype "passive"))
      (node (ref "C97") (pin "2") (pinfunction "2_2") (pintype "passive"))
      (node (ref "C99") (pin "2") (pinfunction "2_2") (pintype "passive"))
      (node (ref "CN1") (pin "1") (pinfunction "1_1") (pintype "bidirectional"))
      (node (ref "M11") (pin "11") (pinfunction "GND_11") (pintype "bidirectional"))
      (node (ref "M11") (pin "9") (pinfunction "GND_9") (pintype "bidirectional"))
      (node (ref "M12") (pin "11") (pinfunction "GND_11") (pintype "bidirectional"))
      (node (ref "M12") (pin "9") (pinfunction "GND_9") (pintype "bidirectional"))
      (node (ref "M13") (pin "11") (pinfunction "GND_11") (pintype "bidirectional"))
      (node (ref "M13") (pin "9") (pinfunction "GND_9") (pintype "bidirectional"))
      (node (ref "M14") (pin "11") (pinfunction "GND_11") (pintype "bidirectional"))
      (node (ref "M14") (pin "9") (pinfunction "GND_9") (pintype "bidirectional"))
      (node (ref "M15") (pin "11") (pinfunction "GND_11") (pintype "bidirectional"))
      (node (ref "M15") (pin "9") (pinfunction "GND_9") (pintype "bidirectional"))
      (node (ref "M16") (pin "11") (pinfunction "GND_11") (pintype "bidirectional"))
      (node (ref "M16") (pin "9") (pinfunction "GND_9") (pintype "bidirectional"))
      (node (ref "M17") (pin "11") (pinfunction "GND_11") (pintype "bidirectional"))
      (node (ref "M17") (pin "9") (pinfunction "GND_9") (pintype "bidirectional"))
      (node (ref "M18") (pin "11") (pinfunction "GND_11") (pintype "bidirectional"))
      (node (ref "M18") (pin "9") (pinfunction "GND_9") (pintype "bidirectional"))
      (node (ref "M21") (pin "11") (pinfunction "GND_11") (pintype "bidirectional"))
      (node (ref "M21") (pin "9") (pinfunction "GND_9") (pintype "bidirectional"))
      (node (ref "M22") (pin "11") (pinfunction "GND_11") (pintype "bidirectional"))
      (node (ref "M22") (pin "9") (pinfunction "GND_9") (pintype "bidirectional"))
      (node (ref "M23") (pin "11") (pinfunction "GND_11") (pintype "bidirectional"))
      (node (ref "M23") (pin "9") (pinfunction "GND_9") (pintype "bidirectional"))
      (node (ref "M24") (pin "11") (pinfunction "GND_11") (pintype "bidirectional"))
      (node (ref "M24") (pin "9") (pinfunction "GND_9") (pintype "bidirectional"))
      (node (ref "M25") (pin "11") (pinfunction "GND_11") (pintype "bidirectional"))
      (node (ref "M25") (pin "9") (pinfunction "GND_9") (pintype "bidirectional"))
      (node (ref "M26") (pin "11") (pinfunction "GND_11") (pintype "bidirectional"))
      (node (ref "M26") (pin "9") (pinfunction "GND_9") (pintype "bidirectional"))
      (node (ref "M27") (pin "11") (pinfunction "GND_11") (pintype "bidirectional"))
      (node (ref "M27") (pin "9") (pinfunction "GND_9") (pintype "bidirectional"))
      (node (ref "M28") (pin "11") (pinfunction "GND_11") (pintype "bidirectional"))
      (node (ref "M28") (pin "9") (pinfunction "GND_9") (pintype "bidirectional"))
      (node (ref "M31") (pin "11") (pinfunction "GND_11") (pintype "bidirectional"))
      (node (ref "M31") (pin "9") (pinfunction "GND_9") (pintype "bidirectional"))
      (node (ref "M32") (pin "11") (pinfunction "GND_11") (pintype "bidirectional"))
      (node (ref "M32") (pin "9") (pinfunction "GND_9") (pintype "bidirectional"))
      (node (ref "M33") (pin "11") (pinfunction "GND_11") (pintype "bidirectional"))
      (node (ref "M33") (pin "9") (pinfunction "GND_9") (pintype "bidirectional"))
      (node (ref "M34") (pin "11") (pinfunction "GND_11") (pintype "bidirectional"))
      (node (ref "M34") (pin "9") (pinfunction "GND_9") (pintype "bidirectional"))
      (node (ref "M35") (pin "11") (pinfunction "GND_11") (pintype "bidirectional"))
      (node (ref "M35") (pin "9") (pinfunction "GND_9") (pintype "bidirectional"))
      (node (ref "M36") (pin "11") (pinfunction "GND_11") (pintype "bidirectional"))
      (node (ref "M36") (pin "9") (pinfunction "GND_9") (pintype "bidirectional"))
      (node (ref "M37") (pin "11") (pinfunction "GND_11") (pintype "bidirectional"))
      (node (ref "M37") (pin "9") (pinfunction "GND_9") (pintype "bidirectional"))
      (node (ref "M38") (pin "11") (pinfunction "GND_11") (pintype "bidirectional"))
      (node (ref "M38") (pin "9") (pinfunction "GND_9") (pintype "bidirectional"))
      (node (ref "M41") (pin "11") (pinfunction "GND_11") (pintype "bidirectional"))
      (node (ref "M41") (pin "9") (pinfunction "GND_9") (pintype "bidirectional"))
      (node (ref "M42") (pin "11") (pinfunction "GND_11") (pintype "bidirectional"))
      (node (ref "M42") (pin "9") (pinfunction "GND_9") (pintype "bidirectional"))
      (node (ref "M43") (pin "11") (pinfunction "GND_11") (pintype "bidirectional"))
      (node (ref "M43") (pin "9") (pinfunction "GND_9") (pintype "bidirectional"))
      (node (ref "M44") (pin "11") (pinfunction "GND_11") (pintype "bidirectional"))
      (node (ref "M44") (pin "9") (pinfunction "GND_9") (pintype "bidirectional"))
      (node (ref "M45") (pin "11") (pinfunction "GND_11") (pintype "bidirectional"))
      (node (ref "M45") (pin "9") (pinfunction "GND_9") (pintype "bidirectional"))
      (node (ref "M46") (pin "11") (pinfunction "GND_11") (pintype "bidirectional"))
      (node (ref "M46") (pin "9") (pinfunction "GND_9") (pintype "bidirectional"))
      (node (ref "M47") (pin "11") (pinfunction "GND_11") (pintype "bidirectional"))
      (node (ref "M47") (pin "9") (pinfunction "GND_9") (pintype "bidirectional"))
      (node (ref "M48") (pin "11") (pinfunction "GND_11") (pintype "bidirectional"))
      (node (ref "M48") (pin "9") (pinfunction "GND_9") (pintype "bidirectional"))
      (node (ref "M51") (pin "11") (pinfunction "GND_11") (pintype "bidirectional"))
      (node (ref "M51") (pin "9") (pinfunction "GND_9") (pintype "bidirectional"))
      (node (ref "M52") (pin "11") (pinfunction "GND_11") (pintype "bidirectional"))
      (node (ref "M52") (pin "9") (pinfunction "GND_9") (pintype "bidirectional"))
      (node (ref "M53") (pin "11") (pinfunction "GND_11") (pintype "bidirectional"))
      (node (ref "M53") (pin "9") (pinfunction "GND_9") (pintype "bidirectional"))
      (node (ref "M54") (pin "11") (pinfunction "GND_11") (pintype "bidirectional"))
      (node (ref "M54") (pin "9") (pinfunction "GND_9") (pintype "bidirectional"))
      (node (ref "M55") (pin "11") (pinfunction "GND_11") (pintype "bidirectional"))
      (node (ref "M55") (pin "9") (pinfunction "GND_9") (pintype "bidirectional"))
      (node (ref "M56") (pin "11") (pinfunction "GND_11") (pintype "bidirectional"))
      (node (ref "M56") (pin "9") (pinfunction "GND_9") (pintype "bidirectional"))
      (node (ref "M57") (pin "11") (pinfunction "GND_11") (pintype "bidirectional"))
      (node (ref "M57") (pin "9") (pinfunction "GND_9") (pintype "bidirectional"))
      (node (ref "M58") (pin "11") (pinfunction "GND_11") (pintype "bidirectional"))
      (node (ref "M58") (pin "9") (pinfunction "GND_9") (pintype "bidirectional"))
      (node (ref "M61") (pin "11") (pinfunction "GND_11") (pintype "bidirectional"))
      (node (ref "M61") (pin "9") (pinfunction "GND_9") (pintype "bidirectional"))
      (node (ref "M62") (pin "11") (pinfunction "GND_11") (pintype "bidirectional"))
      (node (ref "M62") (pin "9") (pinfunction "GND_9") (pintype "bidirectional"))
      (node (ref "M63") (pin "11") (pinfunction "GND_11") (pintype "bidirectional"))
      (node (ref "M63") (pin "9") (pinfunction "GND_9") (pintype "bidirectional"))
      (node (ref "M64") (pin "11") (pinfunction "GND_11") (pintype "bidirectional"))
      (node (ref "M64") (pin "9") (pinfunction "GND_9") (pintype "bidirectional"))
      (node (ref "M65") (pin "11") (pinfunction "GND_11") (pintype "bidirectional"))
      (node (ref "M65") (pin "9") (pinfunction "GND_9") (pintype "bidirectional"))
      (node (ref "M66") (pin "11") (pinfunction "GND_11") (pintype "bidirectional"))
      (node (ref "M66") (pin "9") (pinfunction "GND_9") (pintype "bidirectional"))
      (node (ref "M67") (pin "11") (pinfunction "GND_11") (pintype "bidirectional"))
      (node (ref "M67") (pin "9") (pinfunction "GND_9") (pintype "bidirectional"))
      (node (ref "M68") (pin "11") (pinfunction "GND_11") (pintype "bidirectional"))
      (node (ref "M68") (pin "9") (pinfunction "GND_9") (pintype "bidirectional"))
      (node (ref "M71") (pin "11") (pinfunction "GND_11") (pintype "bidirectional"))
      (node (ref "M71") (pin "9") (pinfunction "GND_9") (pintype "bidirectional"))
      (node (ref "M72") (pin "11") (pinfunction "GND_11") (pintype "bidirectional"))
      (node (ref "M72") (pin "9") (pinfunction "GND_9") (pintype "bidirectional"))
      (node (ref "M73") (pin "11") (pinfunction "GND_11") (pintype "bidirectional"))
      (node (ref "M73") (pin "9") (pinfunction "GND_9") (pintype "bidirectional"))
      (node (ref "M74") (pin "11") (pinfunction "GND_11") (pintype "bidirectional"))
      (node (ref "M74") (pin "9") (pinfunction "GND_9") (pintype "bidirectional"))
      (node (ref "M75") (pin "11") (pinfunction "GND_11") (pintype "bidirectional"))
      (node (ref "M75") (pin "9") (pinfunction "GND_9") (pintype "bidirectional"))
      (node (ref "M76") (pin "11") (pinfunction "GND_11") (pintype "bidirectional"))
      (node (ref "M76") (pin "9") (pinfunction "GND_9") (pintype "bidirectional"))
      (node (ref "M77") (pin "11") (pinfunction "GND_11") (pintype "bidirectional"))
      (node (ref "M77") (pin "9") (pinfunction "GND_9") (pintype "bidirectional"))
      (node (ref "M78") (pin "11") (pinfunction "GND_11") (pintype "bidirectional"))
      (node (ref "M78") (pin "9") (pinfunction "GND_9") (pintype "bidirectional"))
      (node (ref "M81") (pin "11") (pinfunction "GND_11") (pintype "bidirectional"))
      (node (ref "M81") (pin "9") (pinfunction "GND_9") (pintype "bidirectional"))
      (node (ref "M82") (pin "11") (pinfunction "GND_11") (pintype "bidirectional"))
      (node (ref "M82") (pin "9") (pinfunction "GND_9") (pintype "bidirectional"))
      (node (ref "M83") (pin "11") (pinfunction "GND_11") (pintype "bidirectional"))
      (node (ref "M83") (pin "9") (pinfunction "GND_9") (pintype "bidirectional"))
      (node (ref "M84") (pin "11") (pinfunction "GND_11") (pintype "bidirectional"))
      (node (ref "M84") (pin "9") (pinfunction "GND_9") (pintype "bidirectional"))
      (node (ref "M85") (pin "11") (pinfunction "GND_11") (pintype "bidirectional"))
      (node (ref "M85") (pin "9") (pinfunction "GND_9") (pintype "bidirectional"))
      (node (ref "M86") (pin "11") (pinfunction "GND_11") (pintype "bidirectional"))
      (node (ref "M86") (pin "9") (pinfunction "GND_9") (pintype "bidirectional"))
      (node (ref "M87") (pin "11") (pinfunction "GND_11") (pintype "bidirectional"))
      (node (ref "M87") (pin "9") (pinfunction "GND_9") (pintype "bidirectional"))
      (node (ref "M88") (pin "11") (pinfunction "GND_11") (pintype "bidirectional"))
      (node (ref "M88") (pin "9") (pinfunction "GND_9") (pintype "bidirectional"))
      (node (ref "U1") (pin "1") (pinfunction "AD0_1") (pintype "bidirectional"))
      (node (ref "U1") (pin "12") (pinfunction "GND_12") (pintype "bidirectional"))
      (node (ref "U1") (pin "2") (pinfunction "AD1_2") (pintype "bidirectional"))
      (node (ref "U1") (pin "21") (pinfunction "AD2_21") (pintype "bidirectional"))
      (node (ref "U2") (pin "12") (pinfunction "GND_12") (pintype "bidirectional"))
      (node (ref "U2") (pin "2") (pinfunction "AD1_2") (pintype "bidirectional"))
      (node (ref "U2") (pin "21") (pinfunction "AD2_21") (pintype "bidirectional"))
      (node (ref "U3") (pin "1") (pinfunction "AD0_1") (pintype "bidirectional"))
      (node (ref "U3") (pin "12") (pinfunction "GND_12") (pintype "bidirectional"))
      (node (ref "U3") (pin "21") (pinfunction "AD2_21") (pintype "bidirectional"))
      (node (ref "U4") (pin "12") (pinfunction "GND_12") (pintype "bidirectional"))
      (node (ref "U4") (pin "21") (pinfunction "AD2_21") (pintype "bidirectional"))
      (node (ref "U5") (pin "1") (pinfunction "AD0_1") (pintype "bidirectional"))
      (node (ref "U5") (pin "12") (pinfunction "GND_12") (pintype "bidirectional"))
      (node (ref "U5") (pin "2") (pinfunction "AD1_2") (pintype "bidirectional"))
      (node (ref "U6") (pin "12") (pinfunction "GND_12") (pintype "bidirectional"))
      (node (ref "U6") (pin "2") (pinfunction "AD1_2") (pintype "bidirectional"))
      (node (ref "U7") (pin "1") (pinfunction "AD0_1") (pintype "bidirectional"))
      (node (ref "U7") (pin "12") (pinfunction "GND_12") (pintype "bidirectional"))
      (node (ref "U8") (pin "12") (pinfunction "GND_12") (pintype "bidirectional"))
      (node (ref "U9") (pin "2") (pinfunction "GND_2") (pintype "input"))
    )
    (net (code "135") (name "Net-(M11-C1)") (class "Default")
      (node (ref "C1") (pin "1") (pinfunction "1_1") (pintype "passive"))
      (node (ref "M11") (pin "10") (pinfunction "C1_10") (pintype "bidirectional"))
    )
    (net (code "136") (name "Net-(M11-SETC)") (class "Default")
      (node (ref "C2") (pin "1") (pinfunction "1_1") (pintype "passive"))
      (node (ref "M11") (pin "12") (pinfunction "SETC_12") (pintype "bidirectional"))
    )
    (net (code "137") (name "Net-(M11-SETP)") (class "Default")
      (node (ref "C2") (pin "2") (pinfunction "2_2") (pintype "passive"))
      (node (ref "M11") (pin "8") (pinfunction "SETP_8") (pintype "bidirectional"))
    )
    (net (code "138") (name "Net-(M12-C1)") (class "Default")
      (node (ref "C4") (pin "1") (pinfunction "1_1") (pintype "passive"))
      (node (ref "M12") (pin "10") (pinfunction "C1_10") (pintype "bidirectional"))
    )
    (net (code "139") (name "Net-(M12-SETC)") (class "Default")
      (node (ref "C5") (pin "1") (pinfunction "1_1") (pintype "passive"))
      (node (ref "M12") (pin "12") (pinfunction "SETC_12") (pintype "bidirectional"))
    )
    (net (code "140") (name "Net-(M12-SETP)") (class "Default")
      (node (ref "C5") (pin "2") (pinfunction "2_2") (pintype "passive"))
      (node (ref "M12") (pin "8") (pinfunction "SETP_8") (pintype "bidirectional"))
    )
    (net (code "141") (name "Net-(M13-C1)") (class "Default")
      (node (ref "C7") (pin "1") (pinfunction "1_1") (pintype "passive"))
      (node (ref "M13") (pin "10") (pinfunction "C1_10") (pintype "bidirectional"))
    )
    (net (code "142") (name "Net-(M13-SETC)") (class "Default")
      (node (ref "C8") (pin "1") (pinfunction "1_1") (pintype "passive"))
      (node (ref "M13") (pin "12") (pinfunction "SETC_12") (pintype "bidirectional"))
    )
    (net (code "143") (name "Net-(M13-SETP)") (class "Default")
      (node (ref "C8") (pin "2") (pinfunction "2_2") (pintype "passive"))
      (node (ref "M13") (pin "8") (pinfunction "SETP_8") (pintype "bidirectional"))
    )
    (net (code "144") (name "Net-(M14-C1)") (class "Default")
      (node (ref "C10") (pin "1") (pinfunction "1_1") (pintype "passive"))
      (node (ref "M14") (pin "10") (pinfunction "C1_10") (pintype "bidirectional"))
    )
    (net (code "145") (name "Net-(M14-SETC)") (class "Default")
      (node (ref "C11") (pin "1") (pinfunction "1_1") (pintype "passive"))
      (node (ref "M14") (pin "12") (pinfunction "SETC_12") (pintype "bidirectional"))
    )
    (net (code "146") (name "Net-(M14-SETP)") (class "Default")
      (node (ref "C11") (pin "2") (pinfunction "2_2") (pintype "passive"))
      (node (ref "M14") (pin "8") (pinfunction "SETP_8") (pintype "bidirectional"))
    )
    (net (code "147") (name "Net-(M15-C1)") (class "Default")
      (node (ref "C13") (pin "1") (pinfunction "1_1") (pintype "passive"))
      (node (ref "M15") (pin "10") (pinfunction "C1_10") (pintype "bidirectional"))
    )
    (net (code "148") (name "Net-(M15-SETC)") (class "Default")
      (node (ref "C14") (pin "1") (pinfunction "1_1") (pintype "passive"))
      (node (ref "M15") (pin "12") (pinfunction "SETC_12") (pintype "bidirectional"))
    )
    (net (code "149") (name "Net-(M15-SETP)") (class "Default")
      (node (ref "C14") (pin "2") (pinfunction "2_2") (pintype "passive"))
      (node (ref "M15") (pin "8") (pinfunction "SETP_8") (pintype "bidirectional"))
    )
    (net (code "150") (name "Net-(M16-C1)") (class "Default")
      (node (ref "C16") (pin "1") (pinfunction "1_1") (pintype "passive"))
      (node (ref "M16") (pin "10") (pinfunction "C1_10") (pintype "bidirectional"))
    )
    (net (code "151") (name "Net-(M16-SETC)") (class "Default")
      (node (ref "C17") (pin "1") (pinfunction "1_1") (pintype "passive"))
      (node (ref "M16") (pin "12") (pinfunction "SETC_12") (pintype "bidirectional"))
    )
    (net (code "152") (name "Net-(M16-SETP)") (class "Default")
      (node (ref "C17") (pin "2") (pinfunction "2_2") (pintype "passive"))
      (node (ref "M16") (pin "8") (pinfunction "SETP_8") (pintype "bidirectional"))
    )
    (net (code "153") (name "Net-(M17-C1)") (class "Default")
      (node (ref "C19") (pin "1") (pinfunction "1_1") (pintype "passive"))
      (node (ref "M17") (pin "10") (pinfunction "C1_10") (pintype "bidirectional"))
    )
    (net (code "154") (name "Net-(M17-SETC)") (class "Default")
      (node (ref "C20") (pin "1") (pinfunction "1_1") (pintype "passive"))
      (node (ref "M17") (pin "12") (pinfunction "SETC_12") (pintype "bidirectional"))
    )
    (net (code "155") (name "Net-(M17-SETP)") (class "Default")
      (node (ref "C20") (pin "2") (pinfunction "2_2") (pintype "passive"))
      (node (ref "M17") (pin "8") (pinfunction "SETP_8") (pintype "bidirectional"))
    )
    (net (code "156") (name "Net-(M18-C1)") (class "Default")
      (node (ref "C22") (pin "1") (pinfunction "1_1") (pintype "passive"))
      (node (ref "M18") (pin "10") (pinfunction "C1_10") (pintype "bidirectional"))
    )
    (net (code "157") (name "Net-(M18-SETC)") (class "Default")
      (node (ref "C23") (pin "1") (pinfunction "1_1") (pintype "passive"))
      (node (ref "M18") (pin "12") (pinfunction "SETC_12") (pintype "bidirectional"))
    )
    (net (code "158") (name "Net-(M18-SETP)") (class "Default")
      (node (ref "C23") (pin "2") (pinfunction "2_2") (pintype "passive"))
      (node (ref "M18") (pin "8") (pinfunction "SETP_8") (pintype "bidirectional"))
    )
    (net (code "159") (name "Net-(M21-C1)") (class "Default")
      (node (ref "C25") (pin "1") (pinfunction "1_1") (pintype "passive"))
      (node (ref "M21") (pin "10") (pinfunction "C1_10") (pintype "bidirectional"))
    )
    (net (code "160") (name "Net-(M21-SETC)") (class "Default")
      (node (ref "C26") (pin "1") (pinfunction "1_1") (pintype "passive"))
      (node (ref "M21") (pin "12") (pinfunction "SETC_12") (pintype "bidirectional"))
    )
    (net (code "161") (name "Net-(M21-SETP)") (class "Default")
      (node (ref "C26") (pin "2") (pinfunction "2_2") (pintype "passive"))
      (node (ref "M21") (pin "8") (pinfunction "SETP_8") (pintype "bidirectional"))
    )
    (net (code "162") (name "Net-(M22-C1)") (class "Default")
      (node (ref "C28") (pin "1") (pinfunction "1_1") (pintype "passive"))
      (node (ref "M22") (pin "10") (pinfunction "C1_10") (pintype "bidirectional"))
    )
    (net (code "163") (name "Net-(M22-SETC)") (class "Default")
      (node (ref "C29") (pin "1") (pinfunction "1_1") (pintype "passive"))
      (node (ref "M22") (pin "12") (pinfunction "SETC_12") (pintype "bidirectional"))
    )
    (net (code "164") (name "Net-(M22-SETP)") (class "Default")
      (node (ref "C29") (pin "2") (pinfunction "2_2") (pintype "passive"))
      (node (ref "M22") (pin "8") (pinfunction "SETP_8") (pintype "bidirectional"))
    )
    (net (code "165") (name "Net-(M23-C1)") (class "Default")
      (node (ref "C31") (pin "1") (pinfunction "1_1") (pintype "passive"))
      (node (ref "M23") (pin "10") (pinfunction "C1_10") (pintype "bidirectional"))
    )
    (net (code "166") (name "Net-(M23-SETC)") (class "Default")
      (node (ref "C32") (pin "1") (pinfunction "1_1") (pintype "passive"))
      (node (ref "M23") (pin "12") (pinfunction "SETC_12") (pintype "bidirectional"))
    )
    (net (code "167") (name "Net-(M23-SETP)") (class "Default")
      (node (ref "C32") (pin "2") (pinfunction "2_2") (pintype "passive"))
      (node (ref "M23") (pin "8") (pinfunction "SETP_8") (pintype "bidirectional"))
    )
    (net (code "168") (name "Net-(M24-C1)") (class "Default")
      (node (ref "C34") (pin "1") (pinfunction "1_1") (pintype "passive"))
      (node (ref "M24") (pin "10") (pinfunction "C1_10") (pintype "bidirectional"))
    )
    (net (code "169") (name "Net-(M24-SETC)") (class "Default")
      (node (ref "C35") (pin "1") (pinfunction "1_1") (pintype "passive"))
      (node (ref "M24") (pin "12") (pinfunction "SETC_12") (pintype "bidirectional"))
    )
    (net (code "170") (name "Net-(M24-SETP)") (class "Default")
      (node (ref "C35") (pin "2") (pinfunction "2_2") (pintype "passive"))
      (node (ref "M24") (pin "8") (pinfunction "SETP_8") (pintype "bidirectional"))
    )
    (net (code "171") (name "Net-(M25-C1)") (class "Default")
      (node (ref "C37") (pin "1") (pinfunction "1_1") (pintype "passive"))
      (node (ref "M25") (pin "10") (pinfunction "C1_10") (pintype "bidirectional"))
    )
    (net (code "172") (name "Net-(M25-SETC)") (class "Default")
      (node (ref "C38") (pin "1") (pinfunction "1_1") (pintype "passive"))
      (node (ref "M25") (pin "12") (pinfunction "SETC_12") (pintype "bidirectional"))
    )
    (net (code "173") (name "Net-(M25-SETP)") (class "Default")
      (node (ref "C38") (pin "2") (pinfunction "2_2") (pintype "passive"))
      (node (ref "M25") (pin "8") (pinfunction "SETP_8") (pintype "bidirectional"))
    )
    (net (code "174") (name "Net-(M26-C1)") (class "Default")
      (node (ref "C40") (pin "1") (pinfunction "1_1") (pintype "passive"))
      (node (ref "M26") (pin "10") (pinfunction "C1_10") (pintype "bidirectional"))
    )
    (net (code "175") (name "Net-(M26-SETC)") (class "Default")
      (node (ref "C41") (pin "1") (pinfunction "1_1") (pintype "passive"))
      (node (ref "M26") (pin "12") (pinfunction "SETC_12") (pintype "bidirectional"))
    )
    (net (code "176") (name "Net-(M26-SETP)") (class "Default")
      (node (ref "C41") (pin "2") (pinfunction "2_2") (pintype "passive"))
      (node (ref "M26") (pin "8") (pinfunction "SETP_8") (pintype "bidirectional"))
    )
    (net (code "177") (name "Net-(M27-C1)") (class "Default")
      (node (ref "C43") (pin "1") (pinfunction "1_1") (pintype "passive"))
      (node (ref "M27") (pin "10") (pinfunction "C1_10") (pintype "bidirectional"))
    )
    (net (code "178") (name "Net-(M27-SETC)") (class "Default")
      (node (ref "C44") (pin "1") (pinfunction "1_1") (pintype "passive"))
      (node (ref "M27") (pin "12") (pinfunction "SETC_12") (pintype "bidirectional"))
    )
    (net (code "179") (name "Net-(M27-SETP)") (class "Default")
      (node (ref "C44") (pin "2") (pinfunction "2_2") (pintype "passive"))
      (node (ref "M27") (pin "8") (pinfunction "SETP_8") (pintype "bidirectional"))
    )
    (net (code "180") (name "Net-(M28-C1)") (class "Default")
      (node (ref "C46") (pin "1") (pinfunction "1_1") (pintype "passive"))
      (node (ref "M28") (pin "10") (pinfunction "C1_10") (pintype "bidirectional"))
    )
    (net (code "181") (name "Net-(M28-SETC)") (class "Default")
      (node (ref "C47") (pin "1") (pinfunction "1_1") (pintype "passive"))
      (node (ref "M28") (pin "12") (pinfunction "SETC_12") (pintype "bidirectional"))
    )
    (net (code "182") (name "Net-(M28-SETP)") (class "Default")
      (node (ref "C47") (pin "2") (pinfunction "2_2") (pintype "passive"))
      (node (ref "M28") (pin "8") (pinfunction "SETP_8") (pintype "bidirectional"))
    )
    (net (code "183") (name "Net-(M31-C1)") (class "Default")
      (node (ref "C49") (pin "1") (pinfunction "1_1") (pintype "passive"))
      (node (ref "M31") (pin "10") (pinfunction "C1_10") (pintype "bidirectional"))
    )
    (net (code "184") (name "Net-(M31-SETC)") (class "Default")
      (node (ref "C50") (pin "1") (pinfunction "1_1") (pintype "passive"))
      (node (ref "M31") (pin "12") (pinfunction "SETC_12") (pintype "bidirectional"))
    )
    (net (code "185") (name "Net-(M31-SETP)") (class "Default")
      (node (ref "C50") (pin "2") (pinfunction "2_2") (pintype "passive"))
      (node (ref "M31") (pin "8") (pinfunction "SETP_8") (pintype "bidirectional"))
    )
    (net (code "186") (name "Net-(M32-C1)") (class "Default")
      (node (ref "C52") (pin "1") (pinfunction "1_1") (pintype "passive"))
      (node (ref "M32") (pin "10") (pinfunction "C1_10") (pintype "bidirectional"))
    )
    (net (code "187") (name "Net-(M32-SETC)") (class "Default")
      (node (ref "C53") (pin "1") (pinfunction "1_1") (pintype "passive"))
      (node (ref "M32") (pin "12") (pinfunction "SETC_12") (pintype "bidirectional"))
    )
    (net (code "188") (name "Net-(M32-SETP)") (class "Default")
      (node (ref "C53") (pin "2") (pinfunction "2_2") (pintype "passive"))
      (node (ref "M32") (pin "8") (pinfunction "SETP_8") (pintype "bidirectional"))
    )
    (net (code "189") (name "Net-(M33-C1)") (class "Default")
      (node (ref "C55") (pin "1") (pinfunction "1_1") (pintype "passive"))
      (node (ref "M33") (pin "10") (pinfunction "C1_10") (pintype "bidirectional"))
    )
    (net (code "190") (name "Net-(M33-SETC)") (class "Default")
      (node (ref "C56") (pin "1") (pinfunction "1_1") (pintype "passive"))
      (node (ref "M33") (pin "12") (pinfunction "SETC_12") (pintype "bidirectional"))
    )
    (net (code "191") (name "Net-(M33-SETP)") (class "Default")
      (node (ref "C56") (pin "2") (pinfunction "2_2") (pintype "passive"))
      (node (ref "M33") (pin "8") (pinfunction "SETP_8") (pintype "bidirectional"))
    )
    (net (code "192") (name "Net-(M34-C1)") (class "Default")
      (node (ref "C58") (pin "1") (pinfunction "1_1") (pintype "passive"))
      (node (ref "M34") (pin "10") (pinfunction "C1_10") (pintype "bidirectional"))
    )
    (net (code "193") (name "Net-(M34-SETC)") (class "Default")
      (node (ref "C59") (pin "1") (pinfunction "1_1") (pintype "passive"))
      (node (ref "M34") (pin "12") (pinfunction "SETC_12") (pintype "bidirectional"))
    )
    (net (code "194") (name "Net-(M34-SETP)") (class "Default")
      (node (ref "C59") (pin "2") (pinfunction "2_2") (pintype "passive"))
      (node (ref "M34") (pin "8") (pinfunction "SETP_8") (pintype "bidirectional"))
    )
    (net (code "195") (name "Net-(M35-C1)") (class "Default")
      (node (ref "C61") (pin "1") (pinfunction "1_1") (pintype "passive"))
      (node (ref "M35") (pin "10") (pinfunction "C1_10") (pintype "bidirectional"))
    )
    (net (code "196") (name "Net-(M35-SETC)") (class "Default")
      (node (ref "C62") (pin "1") (pinfunction "1_1") (pintype "passive"))
      (node (ref "M35") (pin "12") (pinfunction "SETC_12") (pintype "bidirectional"))
    )
    (net (code "197") (name "Net-(M35-SETP)") (class "Default")
      (node (ref "C62") (pin "2") (pinfunction "2_2") (pintype "passive"))
      (node (ref "M35") (pin "8") (pinfunction "SETP_8") (pintype "bidirectional"))
    )
    (net (code "198") (name "Net-(M36-C1)") (class "Default")
      (node (ref "C64") (pin "1") (pinfunction "1_1") (pintype "passive"))
      (node (ref "M36") (pin "10") (pinfunction "C1_10") (pintype "bidirectional"))
    )
    (net (code "199") (name "Net-(M36-SETC)") (class "Default")
      (node (ref "C65") (pin "1") (pinfunction "1_1") (pintype "passive"))
      (node (ref "M36") (pin "12") (pinfunction "SETC_12") (pintype "bidirectional"))
    )
    (net (code "200") (name "Net-(M36-SETP)") (class "Default")
      (node (ref "C65") (pin "2") (pinfunction "2_2") (pintype "passive"))
      (node (ref "M36") (pin "8") (pinfunction "SETP_8") (pintype "bidirectional"))
    )
    (net (code "201") (name "Net-(M37-C1)") (class "Default")
      (node (ref "C67") (pin "1") (pinfunction "1_1") (pintype "passive"))
      (node (ref "M37") (pin "10") (pinfunction "C1_10") (pintype "bidirectional"))
    )
    (net (code "202") (name "Net-(M37-SETC)") (class "Default")
      (node (ref "C68") (pin "1") (pinfunction "1_1") (pintype "passive"))
      (node (ref "M37") (pin "12") (pinfunction "SETC_12") (pintype "bidirectional"))
    )
    (net (code "203") (name "Net-(M37-SETP)") (class "Default")
      (node (ref "C68") (pin "2") (pinfunction "2_2") (pintype "passive"))
      (node (ref "M37") (pin "8") (pinfunction "SETP_8") (pintype "bidirectional"))
    )
    (net (code "204") (name "Net-(M38-C1)") (class "Default")
      (node (ref "C70") (pin "1") (pinfunction "1_1") (pintype "passive"))
      (node (ref "M38") (pin "10") (pinfunction "C1_10") (pintype "bidirectional"))
    )
    (net (code "205") (name "Net-(M38-SETC)") (class "Default")
      (node (ref "C71") (pin "1") (pinfunction "1_1") (pintype "passive"))
      (node (ref "M38") (pin "12") (pinfunction "SETC_12") (pintype "bidirectional"))
    )
    (net (code "206") (name "Net-(M38-SETP)") (class "Default")
      (node (ref "C71") (pin "2") (pinfunction "2_2") (pintype "passive"))
      (node (ref "M38") (pin "8") (pinfunction "SETP_8") (pintype "bidirectional"))
    )
    (net (code "207") (name "Net-(M41-C1)") (class "Default")
      (node (ref "C73") (pin "1") (pinfunction "1_1") (pintype "passive"))
      (node (ref "M41") (pin "10") (pinfunction "C1_10") (pintype "bidirectional"))
    )
    (net (code "208") (name "Net-(M41-SETC)") (class "Default")
      (node (ref "C74") (pin "1") (pinfunction "1_1") (pintype "passive"))
      (node (ref "M41") (pin "12") (pinfunction "SETC_12") (pintype "bidirectional"))
    )
    (net (code "209") (name "Net-(M41-SETP)") (class "Default")
      (node (ref "C74") (pin "2") (pinfunction "2_2") (pintype "passive"))
      (node (ref "M41") (pin "8") (pinfunction "SETP_8") (pintype "bidirectional"))
    )
    (net (code "210") (name "Net-(M42-C1)") (class "Default")
      (node (ref "C76") (pin "1") (pinfunction "1_1") (pintype "passive"))
      (node (ref "M42") (pin "10") (pinfunction "C1_10") (pintype "bidirectional"))
    )
    (net (code "211") (name "Net-(M42-SETC)") (class "Default")
      (node (ref "C77") (pin "1") (pinfunction "1_1") (pintype "passive"))
      (node (ref "M42") (pin "12") (pinfunction "SETC_12") (pintype "bidirectional"))
    )
    (net (code "212") (name "Net-(M42-SETP)") (class "Default")
      (node (ref "C77") (pin "2") (pinfunction "2_2") (pintype "passive"))
      (node (ref "M42") (pin "8") (pinfunction "SETP_8") (pintype "bidirectional"))
    )
    (net (code "213") (name "Net-(M43-C1)") (class "Default")
      (node (ref "C79") (pin "1") (pinfunction "1_1") (pintype "passive"))
      (node (ref "M43") (pin "10") (pinfunction "C1_10") (pintype "bidirectional"))
    )
    (net (code "214") (name "Net-(M43-SETC)") (class "Default")
      (node (ref "C80") (pin "1") (pinfunction "1_1") (pintype "passive"))
      (node (ref "M43") (pin "12") (pinfunction "SETC_12") (pintype "bidirectional"))
    )
    (net (code "215") (name "Net-(M43-SETP)") (class "Default")
      (node (ref "C80") (pin "2") (pinfunction "2_2") (pintype "passive"))
      (node (ref "M43") (pin "8") (pinfunction "SETP_8") (pintype "bidirectional"))
    )
    (net (code "216") (name "Net-(M44-C1)") (class "Default")
      (node (ref "C82") (pin "1") (pinfunction "1_1") (pintype "passive"))
      (node (ref "M44") (pin "10") (pinfunction "C1_10") (pintype "bidirectional"))
    )
    (net (code "217") (name "Net-(M44-SETC)") (class "Default")
      (node (ref "C83") (pin "1") (pinfunction "1_1") (pintype "passive"))
      (node (ref "M44") (pin "12") (pinfunction "SETC_12") (pintype "bidirectional"))
    )
    (net (code "218") (name "Net-(M44-SETP)") (class "Default")
      (node (ref "C83") (pin "2") (pinfunction "2_2") (pintype "passive"))
      (node (ref "M44") (pin "8") (pinfunction "SETP_8") (pintype "bidirectional"))
    )
    (net (code "219") (name "Net-(M45-C1)") (class "Default")
      (node (ref "C85") (pin "1") (pinfunction "1_1") (pintype "passive"))
      (node (ref "M45") (pin "10") (pinfunction "C1_10") (pintype "bidirectional"))
    )
    (net (code "220") (name "Net-(M45-SETC)") (class "Default")
      (node (ref "C86") (pin "1") (pinfunction "1_1") (pintype "passive"))
      (node (ref "M45") (pin "12") (pinfunction "SETC_12") (pintype "bidirectional"))
    )
    (net (code "221") (name "Net-(M45-SETP)") (class "Default")
      (node (ref "C86") (pin "2") (pinfunction "2_2") (pintype "passive"))
      (node (ref "M45") (pin "8") (pinfunction "SETP_8") (pintype "bidirectional"))
    )
    (net (code "222") (name "Net-(M46-C1)") (class "Default")
      (node (ref "C88") (pin "1") (pinfunction "1_1") (pintype "passive"))
      (node (ref "M46") (pin "10") (pinfunction "C1_10") (pintype "bidirectional"))
    )
    (net (code "223") (name "Net-(M46-SETC)") (class "Default")
      (node (ref "C89") (pin "1") (pinfunction "1_1") (pintype "passive"))
      (node (ref "M46") (pin "12") (pinfunction "SETC_12") (pintype "bidirectional"))
    )
    (net (code "224") (name "Net-(M46-SETP)") (class "Default")
      (node (ref "C89") (pin "2") (pinfunction "2_2") (pintype "passive"))
      (node (ref "M46") (pin "8") (pinfunction "SETP_8") (pintype "bidirectional"))
    )
    (net (code "225") (name "Net-(M47-C1)") (class "Default")
      (node (ref "C91") (pin "1") (pinfunction "1_1") (pintype "passive"))
      (node (ref "M47") (pin "10") (pinfunction "C1_10") (pintype "bidirectional"))
    )
    (net (code "226") (name "Net-(M47-SETC)") (class "Default")
      (node (ref "C92") (pin "1") (pinfunction "1_1") (pintype "passive"))
      (node (ref "M47") (pin "12") (pinfunction "SETC_12") (pintype "bidirectional"))
    )
    (net (code "227") (name "Net-(M47-SETP)") (class "Default")
      (node (ref "C92") (pin "2") (pinfunction "2_2") (pintype "passive"))
      (node (ref "M47") (pin "8") (pinfunction "SETP_8") (pintype "bidirectional"))
    )
    (net (code "228") (name "Net-(M48-C1)") (class "Default")
      (node (ref "C94") (pin "1") (pinfunction "1_1") (pintype "passive"))
      (node (ref "M48") (pin "10") (pinfunction "C1_10") (pintype "bidirectional"))
    )
    (net (code "229") (name "Net-(M48-SETC)") (class "Default")
      (node (ref "C95") (pin "1") (pinfunction "1_1") (pintype "passive"))
      (node (ref "M48") (pin "12") (pinfunction "SETC_12") (pintype "bidirectional"))
    )
    (net (code "230") (name "Net-(M48-SETP)") (class "Default")
      (node (ref "C95") (pin "2") (pinfunction "2_2") (pintype "passive"))
      (node (ref "M48") (pin "8") (pinfunction "SETP_8") (pintype "bidirectional"))
    )
    (net (code "231") (name "Net-(M51-C1)") (class "Default")
      (node (ref "C97") (pin "1") (pinfunction "1_1") (pintype "passive"))
      (node (ref "M51") (pin "10") (pinfunction "C1_10") (pintype "bidirectional"))
    )
    (net (code "232") (name "Net-(M51-SETC)") (class "Default")
      (node (ref "C98") (pin "1") (pinfunction "1_1") (pintype "passive"))
      (node (ref "M51") (pin "12") (pinfunction "SETC_12") (pintype "bidirectional"))
    )
    (net (code "233") (name "Net-(M51-SETP)") (class "Default")
      (node (ref "C98") (pin "2") (pinfunction "2_2") (pintype "passive"))
      (node (ref "M51") (pin "8") (pinfunction "SETP_8") (pintype "bidirectional"))
    )
    (net (code "234") (name "Net-(M52-C1)") (class "Default")
      (node (ref "C100") (pin "1") (pinfunction "1_1") (pintype "passive"))
      (node (ref "M52") (pin "10") (pinfunction "C1_10") (pintype "bidirectional"))
    )
    (net (code "235") (name "Net-(M52-SETC)") (class "Default")
      (node (ref "C101") (pin "1") (pinfunction "1_1") (pintype "passive"))
      (node (ref "M52") (pin "12") (pinfunction "SETC_12") (pintype "bidirectional"))
    )
    (net (code "236") (name "Net-(M52-SETP)") (class "Default")
      (node (ref "C101") (pin "2") (pinfunction "2_2") (pintype "passive"))
      (node (ref "M52") (pin "8") (pinfunction "SETP_8") (pintype "bidirectional"))
    )
    (net (code "237") (name "Net-(M53-C1)") (class "Default")
      (node (ref "C103") (pin "1") (pinfunction "1_1") (pintype "passive"))
      (node (ref "M53") (pin "10") (pinfunction "C1_10") (pintype "bidirectional"))
    )
    (net (code "238") (name "Net-(M53-SETC)") (class "Default")
      (node (ref "C104") (pin "1") (pinfunction "1_1") (pintype "passive"))
      (node (ref "M53") (pin "12") (pinfunction "SETC_12") (pintype "bidirectional"))
    )
    (net (code "239") (name "Net-(M53-SETP)") (class "Default")
      (node (ref "C104") (pin "2") (pinfunction "2_2") (pintype "passive"))
      (node (ref "M53") (pin "8") (pinfunction "SETP_8") (pintype "bidirectional"))
    )
    (net (code "240") (name "Net-(M54-C1)") (class "Default")
      (node (ref "C106") (pin "1") (pinfunction "1_1") (pintype "passive"))
      (node (ref "M54") (pin "10") (pinfunction "C1_10") (pintype "bidirectional"))
    )
    (net (code "241") (name "Net-(M54-SETC)") (class "Default")
      (node (ref "C107") (pin "1") (pinfunction "1_1") (pintype "passive"))
      (node (ref "M54") (pin "12") (pinfunction "SETC_12") (pintype "bidirectional"))
    )
    (net (code "242") (name "Net-(M54-SETP)") (class "Default")
      (node (ref "C107") (pin "2") (pinfunction "2_2") (pintype "passive"))
      (node (ref "M54") (pin "8") (pinfunction "SETP_8") (pintype "bidirectional"))
    )
    (net (code "243") (name "Net-(M55-C1)") (class "Default")
      (node (ref "C109") (pin "1") (pinfunction "1_1") (pintype "passive"))
      (node (ref "M55") (pin "10") (pinfunction "C1_10") (pintype "bidirectional"))
    )
    (net (code "244") (name "Net-(M55-SETC)") (class "Default")
      (node (ref "C110") (pin "1") (pinfunction "1_1") (pintype "passive"))
      (node (ref "M55") (pin "12") (pinfunction "SETC_12") (pintype "bidirectional"))
    )
    (net (code "245") (name "Net-(M55-SETP)") (class "Default")
      (node (ref "C110") (pin "2") (pinfunction "2_2") (pintype "passive"))
      (node (ref "M55") (pin "8") (pinfunction "SETP_8") (pintype "bidirectional"))
    )
    (net (code "246") (name "Net-(M56-C1)") (class "Default")
      (node (ref "C112") (pin "1") (pinfunction "1_1") (pintype "passive"))
      (node (ref "M56") (pin "10") (pinfunction "C1_10") (pintype "bidirectional"))
    )
    (net (code "247") (name "Net-(M56-SETC)") (class "Default")
      (node (ref "C113") (pin "1") (pinfunction "1_1") (pintype "passive"))
      (node (ref "M56") (pin "12") (pinfunction "SETC_12") (pintype "bidirectional"))
    )
    (net (code "248") (name "Net-(M56-SETP)") (class "Default")
      (node (ref "C113") (pin "2") (pinfunction "2_2") (pintype "passive"))
      (node (ref "M56") (pin "8") (pinfunction "SETP_8") (pintype "bidirectional"))
    )
    (net (code "249") (name "Net-(M57-C1)") (class "Default")
      (node (ref "C115") (pin "1") (pinfunction "1_1") (pintype "passive"))
      (node (ref "M57") (pin "10") (pinfunction "C1_10") (pintype "bidirectional"))
    )
    (net (code "250") (name "Net-(M57-SETC)") (class "Default")
      (node (ref "C116") (pin "1") (pinfunction "1_1") (pintype "passive"))
      (node (ref "M57") (pin "12") (pinfunction "SETC_12") (pintype "bidirectional"))
    )
    (net (code "251") (name "Net-(M57-SETP)") (class "Default")
      (node (ref "C116") (pin "2") (pinfunction "2_2") (pintype "passive"))
      (node (ref "M57") (pin "8") (pinfunction "SETP_8") (pintype "bidirectional"))
    )
    (net (code "252") (name "Net-(M58-C1)") (class "Default")
      (node (ref "C118") (pin "1") (pinfunction "1_1") (pintype "passive"))
      (node (ref "M58") (pin "10") (pinfunction "C1_10") (pintype "bidirectional"))
    )
    (net (code "253") (name "Net-(M58-SETC)") (class "Default")
      (node (ref "C119") (pin "1") (pinfunction "1_1") (pintype "passive"))
      (node (ref "M58") (pin "12") (pinfunction "SETC_12") (pintype "bidirectional"))
    )
    (net (code "254") (name "Net-(M58-SETP)") (class "Default")
      (node (ref "C119") (pin "2") (pinfunction "2_2") (pintype "passive"))
      (node (ref "M58") (pin "8") (pinfunction "SETP_8") (pintype "bidirectional"))
    )
    (net (code "255") (name "Net-(M61-C1)") (class "Default")
      (node (ref "C121") (pin "1") (pinfunction "1_1") (pintype "passive"))
      (node (ref "M61") (pin "10") (pinfunction "C1_10") (pintype "bidirectional"))
    )
    (net (code "256") (name "Net-(M61-SETC)") (class "Default")
      (node (ref "C122") (pin "1") (pinfunction "1_1") (pintype "passive"))
      (node (ref "M61") (pin "12") (pinfunction "SETC_12") (pintype "bidirectional"))
    )
    (net (code "257") (name "Net-(M61-SETP)") (class "Default")
      (node (ref "C122") (pin "2") (pinfunction "2_2") (pintype "passive"))
      (node (ref "M61") (pin "8") (pinfunction "SETP_8") (pintype "bidirectional"))
    )
    (net (code "258") (name "Net-(M62-C1)") (class "Default")
      (node (ref "C124") (pin "1") (pinfunction "1_1") (pintype "passive"))
      (node (ref "M62") (pin "10") (pinfunction "C1_10") (pintype "bidirectional"))
    )
    (net (code "259") (name "Net-(M62-SETC)") (class "Default")
      (node (ref "C125") (pin "1") (pinfunction "1_1") (pintype "passive"))
      (node (ref "M62") (pin "12") (pinfunction "SETC_12") (pintype "bidirectional"))
    )
    (net (code "260") (name "Net-(M62-SETP)") (class "Default")
      (node (ref "C125") (pin "2") (pinfunction "2_2") (pintype "passive"))
      (node (ref "M62") (pin "8") (pinfunction "SETP_8") (pintype "bidirectional"))
    )
    (net (code "261") (name "Net-(M63-C1)") (class "Default")
      (node (ref "C127") (pin "1") (pinfunction "1_1") (pintype "passive"))
      (node (ref "M63") (pin "10") (pinfunction "C1_10") (pintype "bidirectional"))
    )
    (net (code "262") (name "Net-(M63-SETC)") (class "Default")
      (node (ref "C128") (pin "1") (pinfunction "1_1") (pintype "passive"))
      (node (ref "M63") (pin "12") (pinfunction "SETC_12") (pintype "bidirectional"))
    )
    (net (code "263") (name "Net-(M63-SETP)") (class "Default")
      (node (ref "C128") (pin "2") (pinfunction "2_2") (pintype "passive"))
      (node (ref "M63") (pin "8") (pinfunction "SETP_8") (pintype "bidirectional"))
    )
    (net (code "264") (name "Net-(M64-C1)") (class "Default")
      (node (ref "C130") (pin "1") (pinfunction "1_1") (pintype "passive"))
      (node (ref "M64") (pin "10") (pinfunction "C1_10") (pintype "bidirectional"))
    )
    (net (code "265") (name "Net-(M64-SETC)") (class "Default")
      (node (ref "C131") (pin "1") (pinfunction "1_1") (pintype "passive"))
      (node (ref "M64") (pin "12") (pinfunction "SETC_12") (pintype "bidirectional"))
    )
    (net (code "266") (name "Net-(M64-SETP)") (class "Default")
      (node (ref "C131") (pin "2") (pinfunction "2_2") (pintype "passive"))
      (node (ref "M64") (pin "8") (pinfunction "SETP_8") (pintype "bidirectional"))
    )
    (net (code "267") (name "Net-(M65-C1)") (class "Default")
      (node (ref "C133") (pin "1") (pinfunction "1_1") (pintype "passive"))
      (node (ref "M65") (pin "10") (pinfunction "C1_10") (pintype "bidirectional"))
    )
    (net (code "268") (name "Net-(M65-SETC)") (class "Default")
      (node (ref "C134") (pin "1") (pinfunction "1_1") (pintype "passive"))
      (node (ref "M65") (pin "12") (pinfunction "SETC_12") (pintype "bidirectional"))
    )
    (net (code "269") (name "Net-(M65-SETP)") (class "Default")
      (node (ref "C134") (pin "2") (pinfunction "2_2") (pintype "passive"))
      (node (ref "M65") (pin "8") (pinfunction "SETP_8") (pintype "bidirectional"))
    )
    (net (code "270") (name "Net-(M66-C1)") (class "Default")
      (node (ref "C136") (pin "1") (pinfunction "1_1") (pintype "passive"))
      (node (ref "M66") (pin "10") (pinfunction "C1_10") (pintype "bidirectional"))
    )
    (net (code "271") (name "Net-(M66-SETC)") (class "Default")
      (node (ref "C137") (pin "1") (pinfunction "1_1") (pintype "passive"))
      (node (ref "M66") (pin "12") (pinfunction "SETC_12") (pintype "bidirectional"))
    )
    (net (code "272") (name "Net-(M66-SETP)") (class "Default")
      (node (ref "C137") (pin "2") (pinfunction "2_2") (pintype "passive"))
      (node (ref "M66") (pin "8") (pinfunction "SETP_8") (pintype "bidirectional"))
    )
    (net (code "273") (name "Net-(M67-C1)") (class "Default")
      (node (ref "C139") (pin "1") (pinfunction "1_1") (pintype "passive"))
      (node (ref "M67") (pin "10") (pinfunction "C1_10") (pintype "bidirectional"))
    )
    (net (code "274") (name "Net-(M67-SETC)") (class "Default")
      (node (ref "C140") (pin "1") (pinfunction "1_1") (pintype "passive"))
      (node (ref "M67") (pin "12") (pinfunction "SETC_12") (pintype "bidirectional"))
    )
    (net (code "275") (name "Net-(M67-SETP)") (class "Default")
      (node (ref "C140") (pin "2") (pinfunction "2_2") (pintype "passive"))
      (node (ref "M67") (pin "8") (pinfunction "SETP_8") (pintype "bidirectional"))
    )
    (net (code "276") (name "Net-(M68-C1)") (class "Default")
      (node (ref "C142") (pin "1") (pinfunction "1_1") (pintype "passive"))
      (node (ref "M68") (pin "10") (pinfunction "C1_10") (pintype "bidirectional"))
    )
    (net (code "277") (name "Net-(M68-SETC)") (class "Default")
      (node (ref "C143") (pin "1") (pinfunction "1_1") (pintype "passive"))
      (node (ref "M68") (pin "12") (pinfunction "SETC_12") (pintype "bidirectional"))
    )
    (net (code "278") (name "Net-(M68-SETP)") (class "Default")
      (node (ref "C143") (pin "2") (pinfunction "2_2") (pintype "passive"))
      (node (ref "M68") (pin "8") (pinfunction "SETP_8") (pintype "bidirectional"))
    )
    (net (code "279") (name "Net-(M71-C1)") (class "Default")
      (node (ref "C145") (pin "1") (pinfunction "1_1") (pintype "passive"))
      (node (ref "M71") (pin "10") (pinfunction "C1_10") (pintype "bidirectional"))
    )
    (net (code "280") (name "Net-(M71-SETC)") (class "Default")
      (node (ref "C146") (pin "1") (pinfunction "1_1") (pintype "passive"))
      (node (ref "M71") (pin "12") (pinfunction "SETC_12") (pintype "bidirectional"))
    )
    (net (code "281") (name "Net-(M71-SETP)") (class "Default")
      (node (ref "C146") (pin "2") (pinfunction "2_2") (pintype "passive"))
      (node (ref "M71") (pin "8") (pinfunction "SETP_8") (pintype "bidirectional"))
    )
    (net (code "282") (name "Net-(M72-C1)") (class "Default")
      (node (ref "C148") (pin "1") (pinfunction "1_1") (pintype "passive"))
      (node (ref "M72") (pin "10") (pinfunction "C1_10") (pintype "bidirectional"))
    )
    (net (code "283") (name "Net-(M72-SETC)") (class "Default")
      (node (ref "C149") (pin "1") (pinfunction "1_1") (pintype "passive"))
      (node (ref "M72") (pin "12") (pinfunction "SETC_12") (pintype "bidirectional"))
    )
    (net (code "284") (name "Net-(M72-SETP)") (class "Default")
      (node (ref "C149") (pin "2") (pinfunction "2_2") (pintype "passive"))
      (node (ref "M72") (pin "8") (pinfunction "SETP_8") (pintype "bidirectional"))
    )
    (net (code "285") (name "Net-(M73-C1)") (class "Default")
      (node (ref "C151") (pin "1") (pinfunction "1_1") (pintype "passive"))
      (node (ref "M73") (pin "10") (pinfunction "C1_10") (pintype "bidirectional"))
    )
    (net (code "286") (name "Net-(M73-SETC)") (class "Default")
      (node (ref "C152") (pin "1") (pinfunction "1_1") (pintype "passive"))
      (node (ref "M73") (pin "12") (pinfunction "SETC_12") (pintype "bidirectional"))
    )
    (net (code "287") (name "Net-(M73-SETP)") (class "Default")
      (node (ref "C152") (pin "2") (pinfunction "2_2") (pintype "passive"))
      (node (ref "M73") (pin "8") (pinfunction "SETP_8") (pintype "bidirectional"))
    )
    (net (code "288") (name "Net-(M74-C1)") (class "Default")
      (node (ref "C154") (pin "1") (pinfunction "1_1") (pintype "passive"))
      (node (ref "M74") (pin "10") (pinfunction "C1_10") (pintype "bidirectional"))
    )
    (net (code "289") (name "Net-(M74-SETC)") (class "Default")
      (node (ref "C155") (pin "1") (pinfunction "1_1") (pintype "passive"))
      (node (ref "M74") (pin "12") (pinfunction "SETC_12") (pintype "bidirectional"))
    )
    (net (code "290") (name "Net-(M74-SETP)") (class "Default")
      (node (ref "C155") (pin "2") (pinfunction "2_2") (pintype "passive"))
      (node (ref "M74") (pin "8") (pinfunction "SETP_8") (pintype "bidirectional"))
    )
    (net (code "291") (name "Net-(M75-C1)") (class "Default")
      (node (ref "C157") (pin "1") (pinfunction "1_1") (pintype "passive"))
      (node (ref "M75") (pin "10") (pinfunction "C1_10") (pintype "bidirectional"))
    )
    (net (code "292") (name "Net-(M75-SETC)") (class "Default")
      (node (ref "C158") (pin "1") (pinfunction "1_1") (pintype "passive"))
      (node (ref "M75") (pin "12") (pinfunction "SETC_12") (pintype "bidirectional"))
    )
    (net (code "293") (name "Net-(M75-SETP)") (class "Default")
      (node (ref "C158") (pin "2") (pinfunction "2_2") (pintype "passive"))
      (node (ref "M75") (pin "8") (pinfunction "SETP_8") (pintype "bidirectional"))
    )
    (net (code "294") (name "Net-(M76-C1)") (class "Default")
      (node (ref "C160") (pin "1") (pinfunction "1_1") (pintype "passive"))
      (node (ref "M76") (pin "10") (pinfunction "C1_10") (pintype "bidirectional"))
    )
    (net (code "295") (name "Net-(M76-SETC)") (class "Default")
      (node (ref "C161") (pin "1") (pinfunction "1_1") (pintype "passive"))
      (node (ref "M76") (pin "12") (pinfunction "SETC_12") (pintype "bidirectional"))
    )
    (net (code "296") (name "Net-(M76-SETP)") (class "Default")
      (node (ref "C161") (pin "2") (pinfunction "2_2") (pintype "passive"))
      (node (ref "M76") (pin "8") (pinfunction "SETP_8") (pintype "bidirectional"))
    )
    (net (code "297") (name "Net-(M77-C1)") (class "Default")
      (node (ref "C163") (pin "1") (pinfunction "1_1") (pintype "passive"))
      (node (ref "M77") (pin "10") (pinfunction "C1_10") (pintype "bidirectional"))
    )
    (net (code "298") (name "Net-(M77-SETC)") (class "Default")
      (node (ref "C164") (pin "1") (pinfunction "1_1") (pintype "passive"))
      (node (ref "M77") (pin "12") (pinfunction "SETC_12") (pintype "bidirectional"))
    )
    (net (code "299") (name "Net-(M77-SETP)") (class "Default")
      (node (ref "C164") (pin "2") (pinfunction "2_2") (pintype "passive"))
      (node (ref "M77") (pin "8") (pinfunction "SETP_8") (pintype "bidirectional"))
    )
    (net (code "300") (name "Net-(M78-C1)") (class "Default")
      (node (ref "C166") (pin "1") (pinfunction "1_1") (pintype "passive"))
      (node (ref "M78") (pin "10") (pinfunction "C1_10") (pintype "bidirectional"))
    )
    (net (code "301") (name "Net-(M78-SETC)") (class "Default")
      (node (ref "C167") (pin "1") (pinfunction "1_1") (pintype "passive"))
      (node (ref "M78") (pin "12") (pinfunction "SETC_12") (pintype "bidirectional"))
    )
    (net (code "302") (name "Net-(M78-SETP)") (class "Default")
      (node (ref "C167") (pin "2") (pinfunction "2_2") (pintype "passive"))
      (node (ref "M78") (pin "8") (pinfunction "SETP_8") (pintype "bidirectional"))
    )
    (net (code "303") (name "Net-(M81-C1)") (class "Default")
      (node (ref "C169") (pin "1") (pinfunction "1_1") (pintype "passive"))
      (node (ref "M81") (pin "10") (pinfunction "C1_10") (pintype "bidirectional"))
    )
    (net (code "304") (name "Net-(M81-SETC)") (class "Default")
      (node (ref "C170") (pin "1") (pinfunction "1_1") (pintype "passive"))
      (node (ref "M81") (pin "12") (pinfunction "SETC_12") (pintype "bidirectional"))
    )
    (net (code "305") (name "Net-(M81-SETP)") (class "Default")
      (node (ref "C170") (pin "2") (pinfunction "2_2") (pintype "passive"))
      (node (ref "M81") (pin "8") (pinfunction "SETP_8") (pintype "bidirectional"))
    )
    (net (code "306") (name "Net-(M82-C1)") (class "Default")
      (node (ref "C172") (pin "1") (pinfunction "1_1") (pintype "passive"))
      (node (ref "M82") (pin "10") (pinfunction "C1_10") (pintype "bidirectional"))
    )
    (net (code "307") (name "Net-(M82-SETC)") (class "Default")
      (node (ref "C173") (pin "1") (pinfunction "1_1") (pintype "passive"))
      (node (ref "M82") (pin "12") (pinfunction "SETC_12") (pintype "bidirectional"))
    )
    (net (code "308") (name "Net-(M82-SETP)") (class "Default")
      (node (ref "C173") (pin "2") (pinfunction "2_2") (pintype "passive"))
      (node (ref "M82") (pin "8") (pinfunction "SETP_8") (pintype "bidirectional"))
    )
    (net (code "309") (name "Net-(M83-C1)") (class "Default")
      (node (ref "C175") (pin "1") (pinfunction "1_1") (pintype "passive"))
      (node (ref "M83") (pin "10") (pinfunction "C1_10") (pintype "bidirectional"))
    )
    (net (code "310") (name "Net-(M83-SETC)") (class "Default")
      (node (ref "C176") (pin "1") (pinfunction "1_1") (pintype "passive"))
      (node (ref "M83") (pin "12") (pinfunction "SETC_12") (pintype "bidirectional"))
    )
    (net (code "311") (name "Net-(M83-SETP)") (class "Default")
      (node (ref "C176") (pin "2") (pinfunction "2_2") (pintype "passive"))
      (node (ref "M83") (pin "8") (pinfunction "SETP_8") (pintype "bidirectional"))
    )
    (net (code "312") (name "Net-(M84-C1)") (class "Default")
      (node (ref "C178") (pin "1") (pinfunction "1_1") (pintype "passive"))
      (node (ref "M84") (pin "10") (pinfunction "C1_10") (pintype "bidirectional"))
    )
    (net (code "313") (name "Net-(M84-SETC)") (class "Default")
      (node (ref "C179") (pin "1") (pinfunction "1_1") (pintype "passive"))
      (node (ref "M84") (pin "12") (pinfunction "SETC_12") (pintype "bidirectional"))
    )
    (net (code "314") (name "Net-(M84-SETP)") (class "Default")
      (node (ref "C179") (pin "2") (pinfunction "2_2") (pintype "passive"))
      (node (ref "M84") (pin "8") (pinfunction "SETP_8") (pintype "bidirectional"))
    )
    (net (code "315") (name "Net-(M85-C1)") (class "Default")
      (node (ref "C181") (pin "1") (pinfunction "1_1") (pintype "passive"))
      (node (ref "M85") (pin "10") (pinfunction "C1_10") (pintype "bidirectional"))
    )
    (net (code "316") (name "Net-(M85-SETC)") (class "Default")
      (node (ref "C182") (pin "1") (pinfunction "1_1") (pintype "passive"))
      (node (ref "M85") (pin "12") (pinfunction "SETC_12") (pintype "bidirectional"))
    )
    (net (code "317") (name "Net-(M85-SETP)") (class "Default")
      (node (ref "C182") (pin "2") (pinfunction "2_2") (pintype "passive"))
      (node (ref "M85") (pin "8") (pinfunction "SETP_8") (pintype "bidirectional"))
    )
    (net (code "318") (name "Net-(M86-C1)") (class "Default")
      (node (ref "C184") (pin "1") (pinfunction "1_1") (pintype "passive"))
      (node (ref "M86") (pin "10") (pinfunction "C1_10") (pintype "bidirectional"))
    )
    (net (code "319") (name "Net-(M86-SETC)") (class "Default")
      (node (ref "C185") (pin "1") (pinfunction "1_1") (pintype "passive"))
      (node (ref "M86") (pin "12") (pinfunction "SETC_12") (pintype "bidirectional"))
    )
    (net (code "320") (name "Net-(M86-SETP)") (class "Default")
      (node (ref "C185") (pin "2") (pinfunction "2_2") (pintype "passive"))
      (node (ref "M86") (pin "8") (pinfunction "SETP_8") (pintype "bidirectional"))
    )
    (net (code "321") (name "Net-(M87-C1)") (class "Default")
      (node (ref "C187") (pin "1") (pinfunction "1_1") (pintype "passive"))
      (node (ref "M87") (pin "10") (pinfunction "C1_10") (pintype "bidirectional"))
    )
    (net (code "322") (name "Net-(M87-SETC)") (class "Default")
      (node (ref "C188") (pin "1") (pinfunction "1_1") (pintype "passive"))
      (node (ref "M87") (pin "12") (pinfunction "SETC_12") (pintype "bidirectional"))
    )
    (net (code "323") (name "Net-(M87-SETP)") (class "Default")
      (node (ref "C188") (pin "2") (pinfunction "2_2") (pintype "passive"))
      (node (ref "M87") (pin "8") (pinfunction "SETP_8") (pintype "bidirectional"))
    )
    (net (code "324") (name "Net-(M88-C1)") (class "Default")
      (node (ref "C190") (pin "1") (pinfunction "1_1") (pintype "passive"))
      (node (ref "M88") (pin "10") (pinfunction "C1_10") (pintype "bidirectional"))
    )
    (net (code "325") (name "Net-(M88-SETC)") (class "Default")
      (node (ref "C191") (pin "1") (pinfunction "1_1") (pintype "passive"))
      (node (ref "M88") (pin "12") (pinfunction "SETC_12") (pintype "bidirectional"))
    )
    (net (code "326") (name "Net-(M88-SETP)") (class "Default")
      (node (ref "C191") (pin "2") (pinfunction "2_2") (pintype "passive"))
      (node (ref "M88") (pin "8") (pinfunction "SETP_8") (pintype "bidirectional"))
    )
    (net (code "327") (name "Net-(R33-Pad2)") (class "Default")
      (node (ref "R33") (pin "2") (pinfunction "2_2") (pintype "passive"))
      (node (ref "R34") (pin "2") (pinfunction "2_2") (pintype "passive"))
      (node (ref "SJ1") (pin "2") (pinfunction "2_2") (pintype "passive"))
    )
    (net (code "328") (name "Net-(U9-BP)") (class "Default")
      (node (ref "C193") (pin "1") (pinfunction "1_1") (pintype "passive"))
      (node (ref "U9") (pin "4") (pinfunction "BP_4") (pintype "input"))
    )
    (net (code "329") (name "unconnected-(M11-DRDY-Pad15)") (class "Default")
      (node (ref "M11") (pin "15") (pinfunction "DRDY_15") (pintype "bidirectional"))
    )
    (net (code "330") (name "unconnected-(M11-NC-Pad3)") (class "Default")
      (node (ref "M11") (pin "3") (pinfunction "NC_3") (pintype "bidirectional"))
    )
    (net (code "331") (name "unconnected-(M11-NC-Pad5)") (class "Default")
      (node (ref "M11") (pin "5") (pinfunction "NC_5") (pintype "bidirectional"))
    )
    (net (code "332") (name "unconnected-(M11-NC-Pad6)") (class "Default")
      (node (ref "M11") (pin "6") (pinfunction "NC_6") (pintype "bidirectional"))
    )
    (net (code "333") (name "unconnected-(M11-NC-Pad7)") (class "Default")
      (node (ref "M11") (pin "7") (pinfunction "NC_7") (pintype "bidirectional"))
    )
    (net (code "334") (name "unconnected-(M11-NC-Pad14)") (class "Default")
      (node (ref "M11") (pin "14") (pinfunction "NC_14") (pintype "bidirectional"))
    )
    (net (code "335") (name "unconnected-(M12-DRDY-Pad15)") (class "Default")
      (node (ref "M12") (pin "15") (pinfunction "DRDY_15") (pintype "bidirectional"))
    )
    (net (code "336") (name "unconnected-(M12-NC-Pad3)") (class "Default")
      (node (ref "M12") (pin "3") (pinfunction "NC_3") (pintype "bidirectional"))
    )
    (net (code "337") (name "unconnected-(M12-NC-Pad5)") (class "Default")
      (node (ref "M12") (pin "5") (pinfunction "NC_5") (pintype "bidirectional"))
    )
    (net (code "338") (name "unconnected-(M12-NC-Pad6)") (class "Default")
      (node (ref "M12") (pin "6") (pinfunction "NC_6") (pintype "bidirectional"))
    )
    (net (code "339") (name "unconnected-(M12-NC-Pad7)") (class "Default")
      (node (ref "M12") (pin "7") (pinfunction "NC_7") (pintype "bidirectional"))
    )
    (net (code "340") (name "unconnected-(M12-NC-Pad14)") (class "Default")
      (node (ref "M12") (pin "14") (pinfunction "NC_14") (pintype "bidirectional"))
    )
    (net (code "341") (name "unconnected-(M13-DRDY-Pad15)") (class "Default")
      (node (ref "M13") (pin "15") (pinfunction "DRDY_15") (pintype "bidirectional"))
    )
    (net (code "342") (name "unconnected-(M13-NC-Pad3)") (class "Default")
      (node (ref "M13") (pin "3") (pinfunction "NC_3") (pintype "bidirectional"))
    )
    (net (code "343") (name "unconnected-(M13-NC-Pad5)") (class "Default")
      (node (ref "M13") (pin "5") (pinfunction "NC_5") (pintype "bidirectional"))
    )
    (net (code "344") (name "unconnected-(M13-NC-Pad6)") (class "Default")
      (node (ref "M13") (pin "6") (pinfunction "NC_6") (pintype "bidirectional"))
    )
    (net (code "345") (name "unconnected-(M13-NC-Pad7)") (class "Default")
      (node (ref "M13") (pin "7") (pinfunction "NC_7") (pintype "bidirectional"))
    )
    (net (code "346") (name "unconnected-(M13-NC-Pad14)") (class "Default")
      (node (ref "M13") (pin "14") (pinfunction "NC_14") (pintype "bidirectional"))
    )
    (net (code "347") (name "unconnected-(M14-DRDY-Pad15)") (class "Default")
      (node (ref "M14") (pin "15") (pinfunction "DRDY_15") (pintype "bidirectional"))
    )
    (net (code "348") (name "unconnected-(M14-NC-Pad3)") (class "Default")
      (node (ref "M14") (pin "3") (pinfunction "NC_3") (pintype "bidirectional"))
    )
    (net (code "349") (name "unconnected-(M14-NC-Pad5)") (class "Default")
      (node (ref "M14") (pin "5") (pinfunction "NC_5") (pintype "bidirectional"))
    )
    (net (code "350") (name "unconnected-(M14-NC-Pad6)") (class "Default")
      (node (ref "M14") (pin "6") (pinfunction "NC_6") (pintype "bidirectional"))
    )
    (net (code "351") (name "unconnected-(M14-NC-Pad7)") (class "Default")
      (node (ref "M14") (pin "7") (pinfunction "NC_7") (pintype "bidirectional"))
    )
    (net (code "352") (name "unconnected-(M14-NC-Pad14)") (class "Default")
      (node (ref "M14") (pin "14") (pinfunction "NC_14") (pintype "bidirectional"))
    )
    (net (code "353") (name "unconnected-(M15-DRDY-Pad15)") (class "Default")
      (node (ref "M15") (pin "15") (pinfunction "DRDY_15") (pintype "bidirectional"))
    )
    (net (code "354") (name "unconnected-(M15-NC-Pad3)") (class "Default")
      (node (ref "M15") (pin "3") (pinfunction "NC_3") (pintype "bidirectional"))
    )
    (net (code "355") (name "unconnected-(M15-NC-Pad5)") (class "Default")
      (node (ref "M15") (pin "5") (pinfunction "NC_5") (pintype "bidirectional"))
    )
    (net (code "356") (name "unconnected-(M15-NC-Pad6)") (class "Default")
      (node (ref "M15") (pin "6") (pinfunction "NC_6") (pintype "bidirectional"))
    )
    (net (code "357") (name "unconnected-(M15-NC-Pad7)") (class "Default")
      (node (ref "M15") (pin "7") (pinfunction "NC_7") (pintype "bidirectional"))
    )
    (net (code "358") (name "unconnected-(M15-NC-Pad14)") (class "Default")
      (node (ref "M15") (pin "14") (pinfunction "NC_14") (pintype "bidirectional"))
    )
    (net (code "359") (name "unconnected-(M16-DRDY-Pad15)") (class "Default")
      (node (ref "M16") (pin "15") (pinfunction "DRDY_15") (pintype "bidirectional"))
    )
    (net (code "360") (name "unconnected-(M16-NC-Pad3)") (class "Default")
      (node (ref "M16") (pin "3") (pinfunction "NC_3") (pintype "bidirectional"))
    )
    (net (code "361") (name "unconnected-(M16-NC-Pad5)") (class "Default")
      (node (ref "M16") (pin "5") (pinfunction "NC_5") (pintype "bidirectional"))
    )
    (net (code "362") (name "unconnected-(M16-NC-Pad6)") (class "Default")
      (node (ref "M16") (pin "6") (pinfunction "NC_6") (pintype "bidirectional"))
    )
    (net (code "363") (name "unconnected-(M16-NC-Pad7)") (class "Default")
      (node (ref "M16") (pin "7") (pinfunction "NC_7") (pintype "bidirectional"))
    )
    (net (code "364") (name "unconnected-(M16-NC-Pad14)") (class "Default")
      (node (ref "M16") (pin "14") (pinfunction "NC_14") (pintype "bidirectional"))
    )
    (net (code "365") (name "unconnected-(M17-DRDY-Pad15)") (class "Default")
      (node (ref "M17") (pin "15") (pinfunction "DRDY_15") (pintype "bidirectional"))
    )
    (net (code "366") (name "unconnected-(M17-NC-Pad3)") (class "Default")
      (node (ref "M17") (pin "3") (pinfunction "NC_3") (pintype "bidirectional"))
    )
    (net (code "367") (name "unconnected-(M17-NC-Pad5)") (class "Default")
      (node (ref "M17") (pin "5") (pinfunction "NC_5") (pintype "bidirectional"))
    )
    (net (code "368") (name "unconnected-(M17-NC-Pad6)") (class "Default")
      (node (ref "M17") (pin "6") (pinfunction "NC_6") (pintype "bidirectional"))
    )
    (net (code "369") (name "unconnected-(M17-NC-Pad7)") (class "Default")
      (node (ref "M17") (pin "7") (pinfunction "NC_7") (pintype "bidirectional"))
    )
    (net (code "370") (name "unconnected-(M17-NC-Pad14)") (class "Default")
      (node (ref "M17") (pin "14") (pinfunction "NC_14") (pintype "bidirectional"))
    )
    (net (code "371") (name "unconnected-(M18-DRDY-Pad15)") (class "Default")
      (node (ref "M18") (pin "15") (pinfunction "DRDY_15") (pintype "bidirectional"))
    )
    (net (code "372") (name "unconnected-(M18-NC-Pad3)") (class "Default")
      (node (ref "M18") (pin "3") (pinfunction "NC_3") (pintype "bidirectional"))
    )
    (net (code "373") (name "unconnected-(M18-NC-Pad5)") (class "Default")
      (node (ref "M18") (pin "5") (pinfunction "NC_5") (pintype "bidirectional"))
    )
    (net (code "374") (name "unconnected-(M18-NC-Pad6)") (class "Default")
      (node (ref "M18") (pin "6") (pinfunction "NC_6") (pintype "bidirectional"))
    )
    (net (code "375") (name "unconnected-(M18-NC-Pad7)") (class "Default")
      (node (ref "M18") (pin "7") (pinfunction "NC_7") (pintype "bidirectional"))
    )
    (net (code "376") (name "unconnected-(M18-NC-Pad14)") (class "Default")
      (node (ref "M18") (pin "14") (pinfunction "NC_14") (pintype "bidirectional"))
    )
    (net (code "377") (name "unconnected-(M21-DRDY-Pad15)") (class "Default")
      (node (ref "M21") (pin "15") (pinfunction "DRDY_15") (pintype "bidirectional"))
    )
    (net (code "378") (name "unconnected-(M21-NC-Pad3)") (class "Default")
      (node (ref "M21") (pin "3") (pinfunction "NC_3") (pintype "bidirectional"))
    )
    (net (code "379") (name "unconnected-(M21-NC-Pad5)") (class "Default")
      (node (ref "M21") (pin "5") (pinfunction "NC_5") (pintype "bidirectional"))
    )
    (net (code "380") (name "unconnected-(M21-NC-Pad6)") (class "Default")
      (node (ref "M21") (pin "6") (pinfunction "NC_6") (pintype "bidirectional"))
    )
    (net (code "381") (name "unconnected-(M21-NC-Pad7)") (class "Default")
      (node (ref "M21") (pin "7") (pinfunction "NC_7") (pintype "bidirectional"))
    )
    (net (code "382") (name "unconnected-(M21-NC-Pad14)") (class "Default")
      (node (ref "M21") (pin "14") (pinfunction "NC_14") (pintype "bidirectional"))
    )
    (net (code "383") (name "unconnected-(M22-DRDY-Pad15)") (class "Default")
      (node (ref "M22") (pin "15") (pinfunction "DRDY_15") (pintype "bidirectional"))
    )
    (net (code "384") (name "unconnected-(M22-NC-Pad3)") (class "Default")
      (node (ref "M22") (pin "3") (pinfunction "NC_3") (pintype "bidirectional"))
    )
    (net (code "385") (name "unconnected-(M22-NC-Pad5)") (class "Default")
      (node (ref "M22") (pin "5") (pinfunction "NC_5") (pintype "bidirectional"))
    )
    (net (code "386") (name "unconnected-(M22-NC-Pad6)") (class "Default")
      (node (ref "M22") (pin "6") (pinfunction "NC_6") (pintype "bidirectional"))
    )
    (net (code "387") (name "unconnected-(M22-NC-Pad7)") (class "Default")
      (node (ref "M22") (pin "7") (pinfunction "NC_7") (pintype "bidirectional"))
    )
    (net (code "388") (name "unconnected-(M22-NC-Pad14)") (class "Default")
      (node (ref "M22") (pin "14") (pinfunction "NC_14") (pintype "bidirectional"))
    )
    (net (code "389") (name "unconnected-(M23-DRDY-Pad15)") (class "Default")
      (node (ref "M23") (pin "15") (pinfunction "DRDY_15") (pintype "bidirectional"))
    )
    (net (code "390") (name "unconnected-(M23-NC-Pad3)") (class "Default")
      (node (ref "M23") (pin "3") (pinfunction "NC_3") (pintype "bidirectional"))
    )
    (net (code "391") (name "unconnected-(M23-NC-Pad5)") (class "Default")
      (node (ref "M23") (pin "5") (pinfunction "NC_5") (pintype "bidirectional"))
    )
    (net (code "392") (name "unconnected-(M23-NC-Pad6)") (class "Default")
      (node (ref "M23") (pin "6") (pinfunction "NC_6") (pintype "bidirectional"))
    )
    (net (code "393") (name "unconnected-(M23-NC-Pad7)") (class "Default")
      (node (ref "M23") (pin "7") (pinfunction "NC_7") (pintype "bidirectional"))
    )
    (net (code "394") (name "unconnected-(M23-NC-Pad14)") (class "Default")
      (node (ref "M23") (pin "14") (pinfunction "NC_14") (pintype "bidirectional"))
    )
    (net (code "395") (name "unconnected-(M24-DRDY-Pad15)") (class "Default")
      (node (ref "M24") (pin "15") (pinfunction "DRDY_15") (pintype "bidirectional"))
    )
    (net (code "396") (name "unconnected-(M24-NC-Pad3)") (class "Default")
      (node (ref "M24") (pin "3") (pinfunction "NC_3") (pintype "bidirectional"))
    )
    (net (code "397") (name "unconnected-(M24-NC-Pad5)") (class "Default")
      (node (ref "M24") (pin "5") (pinfunction "NC_5") (pintype "bidirectional"))
    )
    (net (code "398") (name "unconnected-(M24-NC-Pad6)") (class "Default")
      (node (ref "M24") (pin "6") (pinfunction "NC_6") (pintype "bidirectional"))
    )
    (net (code "399") (name "unconnected-(M24-NC-Pad7)") (class "Default")
      (node (ref "M24") (pin "7") (pinfunction "NC_7") (pintype "bidirectional"))
    )
    (net (code "400") (name "unconnected-(M24-NC-Pad14)") (class "Default")
      (node (ref "M24") (pin "14") (pinfunction "NC_14") (pintype "bidirectional"))
    )
    (net (code "401") (name "unconnected-(M25-DRDY-Pad15)") (class "Default")
      (node (ref "M25") (pin "15") (pinfunction "DRDY_15") (pintype "bidirectional"))
    )
    (net (code "402") (name "unconnected-(M25-NC-Pad3)") (class "Default")
      (node (ref "M25") (pin "3") (pinfunction "NC_3") (pintype "bidirectional"))
    )
    (net (code "403") (name "unconnected-(M25-NC-Pad5)") (class "Default")
      (node (ref "M25") (pin "5") (pinfunction "NC_5") (pintype "bidirectional"))
    )
    (net (code "404") (name "unconnected-(M25-NC-Pad6)") (class "Default")
      (node (ref "M25") (pin "6") (pinfunction "NC_6") (pintype "bidirectional"))
    )
    (net (code "405") (name "unconnected-(M25-NC-Pad7)") (class "Default")
      (node (ref "M25") (pin "7") (pinfunction "NC_7") (pintype "bidirectional"))
    )
    (net (code "406") (name "unconnected-(M25-NC-Pad14)") (class "Default")
      (node (ref "M25") (pin "14") (pinfunction "NC_14") (pintype "bidirectional"))
    )
    (net (code "407") (name "unconnected-(M26-DRDY-Pad15)") (class "Default")
      (node (ref "M26") (pin "15") (pinfunction "DRDY_15") (pintype "bidirectional"))
    )
    (net (code "408") (name "unconnected-(M26-NC-Pad3)") (class "Default")
      (node (ref "M26") (pin "3") (pinfunction "NC_3") (pintype "bidirectional"))
    )
    (net (code "409") (name "unconnected-(M26-NC-Pad5)") (class "Default")
      (node (ref "M26") (pin "5") (pinfunction "NC_5") (pintype "bidirectional"))
    )
    (net (code "410") (name "unconnected-(M26-NC-Pad6)") (class "Default")
      (node (ref "M26") (pin "6") (pinfunction "NC_6") (pintype "bidirectional"))
    )
    (net (code "411") (name "unconnected-(M26-NC-Pad7)") (class "Default")
      (node (ref "M26") (pin "7") (pinfunction "NC_7") (pintype "bidirectional"))
    )
    (net (code "412") (name "unconnected-(M26-NC-Pad14)") (class "Default")
      (node (ref "M26") (pin "14") (pinfunction "NC_14") (pintype "bidirectional"))
    )
    (net (code "413") (name "unconnected-(M27-DRDY-Pad15)") (class "Default")
      (node (ref "M27") (pin "15") (pinfunction "DRDY_15") (pintype "bidirectional"))
    )
    (net (code "414") (name "unconnected-(M27-NC-Pad3)") (class "Default")
      (node (ref "M27") (pin "3") (pinfunction "NC_3") (pintype "bidirectional"))
    )
    (net (code "415") (name "unconnected-(M27-NC-Pad5)") (class "Default")
      (node (ref "M27") (pin "5") (pinfunction "NC_5") (pintype "bidirectional"))
    )
    (net (code "416") (name "unconnected-(M27-NC-Pad6)") (class "Default")
      (node (ref "M27") (pin "6") (pinfunction "NC_6") (pintype "bidirectional"))
    )
    (net (code "417") (name "unconnected-(M27-NC-Pad7)") (class "Default")
      (node (ref "M27") (pin "7") (pinfunction "NC_7") (pintype "bidirectional"))
    )
    (net (code "418") (name "unconnected-(M27-NC-Pad14)") (class "Default")
      (node (ref "M27") (pin "14") (pinfunction "NC_14") (pintype "bidirectional"))
    )
    (net (code "419") (name "unconnected-(M28-DRDY-Pad15)") (class "Default")
      (node (ref "M28") (pin "15") (pinfunction "DRDY_15") (pintype "bidirectional"))
    )
    (net (code "420") (name "unconnected-(M28-NC-Pad3)") (class "Default")
      (node (ref "M28") (pin "3") (pinfunction "NC_3") (pintype "bidirectional"))
    )
    (net (code "421") (name "unconnected-(M28-NC-Pad5)") (class "Default")
      (node (ref "M28") (pin "5") (pinfunction "NC_5") (pintype "bidirectional"))
    )
    (net (code "422") (name "unconnected-(M28-NC-Pad6)") (class "Default")
      (node (ref "M28") (pin "6") (pinfunction "NC_6") (pintype "bidirectional"))
    )
    (net (code "423") (name "unconnected-(M28-NC-Pad7)") (class "Default")
      (node (ref "M28") (pin "7") (pinfunction "NC_7") (pintype "bidirectional"))
    )
    (net (code "424") (name "unconnected-(M28-NC-Pad14)") (class "Default")
      (node (ref "M28") (pin "14") (pinfunction "NC_14") (pintype "bidirectional"))
    )
    (net (code "425") (name "unconnected-(M31-DRDY-Pad15)") (class "Default")
      (node (ref "M31") (pin "15") (pinfunction "DRDY_15") (pintype "bidirectional"))
    )
    (net (code "426") (name "unconnected-(M31-NC-Pad3)") (class "Default")
      (node (ref "M31") (pin "3") (pinfunction "NC_3") (pintype "bidirectional"))
    )
    (net (code "427") (name "unconnected-(M31-NC-Pad5)") (class "Default")
      (node (ref "M31") (pin "5") (pinfunction "NC_5") (pintype "bidirectional"))
    )
    (net (code "428") (name "unconnected-(M31-NC-Pad6)") (class "Default")
      (node (ref "M31") (pin "6") (pinfunction "NC_6") (pintype "bidirectional"))
    )
    (net (code "429") (name "unconnected-(M31-NC-Pad7)") (class "Default")
      (node (ref "M31") (pin "7") (pinfunction "NC_7") (pintype "bidirectional"))
    )
    (net (code "430") (name "unconnected-(M31-NC-Pad14)") (class "Default")
      (node (ref "M31") (pin "14") (pinfunction "NC_14") (pintype "bidirectional"))
    )
    (net (code "431") (name "unconnected-(M32-DRDY-Pad15)") (class "Default")
      (node (ref "M32") (pin "15") (pinfunction "DRDY_15") (pintype "bidirectional"))
    )
    (net (code "432") (name "unconnected-(M32-NC-Pad3)") (class "Default")
      (node (ref "M32") (pin "3") (pinfunction "NC_3") (pintype "bidirectional"))
    )
    (net (code "433") (name "unconnected-(M32-NC-Pad5)") (class "Default")
      (node (ref "M32") (pin "5") (pinfunction "NC_5") (pintype "bidirectional"))
    )
    (net (code "434") (name "unconnected-(M32-NC-Pad6)") (class "Default")
      (node (ref "M32") (pin "6") (pinfunction "NC_6") (pintype "bidirectional"))
    )
    (net (code "435") (name "unconnected-(M32-NC-Pad7)") (class "Default")
      (node (ref "M32") (pin "7") (pinfunction "NC_7") (pintype "bidirectional"))
    )
    (net (code "436") (name "unconnected-(M32-NC-Pad14)") (class "Default")
      (node (ref "M32") (pin "14") (pinfunction "NC_14") (pintype "bidirectional"))
    )
    (net (code "437") (name "unconnected-(M33-DRDY-Pad15)") (class "Default")
      (node (ref "M33") (pin "15") (pinfunction "DRDY_15") (pintype "bidirectional"))
    )
    (net (code "438") (name "unconnected-(M33-NC-Pad3)") (class "Default")
      (node (ref "M33") (pin "3") (pinfunction "NC_3") (pintype "bidirectional"))
    )
    (net (code "439") (name "unconnected-(M33-NC-Pad5)") (class "Default")
      (node (ref "M33") (pin "5") (pinfunction "NC_5") (pintype "bidirectional"))
    )
    (net (code "440") (name "unconnected-(M33-NC-Pad6)") (class "Default")
      (node (ref "M33") (pin "6") (pinfunction "NC_6") (pintype "bidirectional"))
    )
    (net (code "441") (name "unconnected-(M33-NC-Pad7)") (class "Default")
      (node (ref "M33") (pin "7") (pinfunction "NC_7") (pintype "bidirectional"))
    )
    (net (code "442") (name "unconnected-(M33-NC-Pad14)") (class "Default")
      (node (ref "M33") (pin "14") (pinfunction "NC_14") (pintype "bidirectional"))
    )
    (net (code "443") (name "unconnected-(M34-DRDY-Pad15)") (class "Default")
      (node (ref "M34") (pin "15") (pinfunction "DRDY_15") (pintype "bidirectional"))
    )
    (net (code "444") (name "unconnected-(M34-NC-Pad3)") (class "Default")
      (node (ref "M34") (pin "3") (pinfunction "NC_3") (pintype "bidirectional"))
    )
    (net (code "445") (name "unconnected-(M34-NC-Pad5)") (class "Default")
      (node (ref "M34") (pin "5") (pinfunction "NC_5") (pintype "bidirectional"))
    )
    (net (code "446") (name "unconnected-(M34-NC-Pad6)") (class "Default")
      (node (ref "M34") (pin "6") (pinfunction "NC_6") (pintype "bidirectional"))
    )
    (net (code "447") (name "unconnected-(M34-NC-Pad7)") (class "Default")
      (node (ref "M34") (pin "7") (pinfunction "NC_7") (pintype "bidirectional"))
    )
    (net (code "448") (name "unconnected-(M34-NC-Pad14)") (class "Default")
      (node (ref "M34") (pin "14") (pinfunction "NC_14") (pintype "bidirectional"))
    )
    (net (code "449") (name "unconnected-(M35-DRDY-Pad15)") (class "Default")
      (node (ref "M35") (pin "15") (pinfunction "DRDY_15") (pintype "bidirectional"))
    )
    (net (code "450") (name "unconnected-(M35-NC-Pad3)") (class "Default")
      (node (ref "M35") (pin "3") (pinfunction "NC_3") (pintype "bidirectional"))
    )
    (net (code "451") (name "unconnected-(M35-NC-Pad5)") (class "Default")
      (node (ref "M35") (pin "5") (pinfunction "NC_5") (pintype "bidirectional"))
    )
    (net (code "452") (name "unconnected-(M35-NC-Pad6)") (class "Default")
      (node (ref "M35") (pin "6") (pinfunction "NC_6") (pintype "bidirectional"))
    )
    (net (code "453") (name "unconnected-(M35-NC-Pad7)") (class "Default")
      (node (ref "M35") (pin "7") (pinfunction "NC_7") (pintype "bidirectional"))
    )
    (net (code "454") (name "unconnected-(M35-NC-Pad14)") (class "Default")
      (node (ref "M35") (pin "14") (pinfunction "NC_14") (pintype "bidirectional"))
    )
    (net (code "455") (name "unconnected-(M36-DRDY-Pad15)") (class "Default")
      (node (ref "M36") (pin "15") (pinfunction "DRDY_15") (pintype "bidirectional"))
    )
    (net (code "456") (name "unconnected-(M36-NC-Pad3)") (class "Default")
      (node (ref "M36") (pin "3") (pinfunction "NC_3") (pintype "bidirectional"))
    )
    (net (code "457") (name "unconnected-(M36-NC-Pad5)") (class "Default")
      (node (ref "M36") (pin "5") (pinfunction "NC_5") (pintype "bidirectional"))
    )
    (net (code "458") (name "unconnected-(M36-NC-Pad6)") (class "Default")
      (node (ref "M36") (pin "6") (pinfunction "NC_6") (pintype "bidirectional"))
    )
    (net (code "459") (name "unconnected-(M36-NC-Pad7)") (class "Default")
      (node (ref "M36") (pin "7") (pinfunction "NC_7") (pintype "bidirectional"))
    )
    (net (code "460") (name "unconnected-(M36-NC-Pad14)") (class "Default")
      (node (ref "M36") (pin "14") (pinfunction "NC_14") (pintype "bidirectional"))
    )
    (net (code "461") (name "unconnected-(M37-DRDY-Pad15)") (class "Default")
      (node (ref "M37") (pin "15") (pinfunction "DRDY_15") (pintype "bidirectional"))
    )
    (net (code "462") (name "unconnected-(M37-NC-Pad3)") (class "Default")
      (node (ref "M37") (pin "3") (pinfunction "NC_3") (pintype "bidirectional"))
    )
    (net (code "463") (name "unconnected-(M37-NC-Pad5)") (class "Default")
      (node (ref "M37") (pin "5") (pinfunction "NC_5") (pintype "bidirectional"))
    )
    (net (code "464") (name "unconnected-(M37-NC-Pad6)") (class "Default")
      (node (ref "M37") (pin "6") (pinfunction "NC_6") (pintype "bidirectional"))
    )
    (net (code "465") (name "unconnected-(M37-NC-Pad7)") (class "Default")
      (node (ref "M37") (pin "7") (pinfunction "NC_7") (pintype "bidirectional"))
    )
    (net (code "466") (name "unconnected-(M37-NC-Pad14)") (class "Default")
      (node (ref "M37") (pin "14") (pinfunction "NC_14") (pintype "bidirectional"))
    )
    (net (code "467") (name "unconnected-(M38-DRDY-Pad15)") (class "Default")
      (node (ref "M38") (pin "15") (pinfunction "DRDY_15") (pintype "bidirectional"))
    )
    (net (code "468") (name "unconnected-(M38-NC-Pad3)") (class "Default")
      (node (ref "M38") (pin "3") (pinfunction "NC_3") (pintype "bidirectional"))
    )
    (net (code "469") (name "unconnected-(M38-NC-Pad5)") (class "Default")
      (node (ref "M38") (pin "5") (pinfunction "NC_5") (pintype "bidirectional"))
    )
    (net (code "470") (name "unconnected-(M38-NC-Pad6)") (class "Default")
      (node (ref "M38") (pin "6") (pinfunction "NC_6") (pintype "bidirectional"))
    )
    (net (code "471") (name "unconnected-(M38-NC-Pad7)") (class "Default")
      (node (ref "M38") (pin "7") (pinfunction "NC_7") (pintype "bidirectional"))
    )
    (net (code "472") (name "unconnected-(M38-NC-Pad14)") (class "Default")
      (node (ref "M38") (pin "14") (pinfunction "NC_14") (pintype "bidirectional"))
    )
    (net (code "473") (name "unconnected-(M41-DRDY-Pad15)") (class "Default")
      (node (ref "M41") (pin "15") (pinfunction "DRDY_15") (pintype "bidirectional"))
    )
    (net (code "474") (name "unconnected-(M41-NC-Pad3)") (class "Default")
      (node (ref "M41") (pin "3") (pinfunction "NC_3") (pintype "bidirectional"))
    )
    (net (code "475") (name "unconnected-(M41-NC-Pad5)") (class "Default")
      (node (ref "M41") (pin "5") (pinfunction "NC_5") (pintype "bidirectional"))
    )
    (net (code "476") (name "unconnected-(M41-NC-Pad6)") (class "Default")
      (node (ref "M41") (pin "6") (pinfunction "NC_6") (pintype "bidirectional"))
    )
    (net (code "477") (name "unconnected-(M41-NC-Pad7)") (class "Default")
      (node (ref "M41") (pin "7") (pinfunction "NC_7") (pintype "bidirectional"))
    )
    (net (code "478") (name "unconnected-(M41-NC-Pad14)") (class "Default")
      (node (ref "M41") (pin "14") (pinfunction "NC_14") (pintype "bidirectional"))
    )
    (net (code "479") (name "unconnected-(M42-DRDY-Pad15)") (class "Default")
      (node (ref "M42") (pin "15") (pinfunction "DRDY_15") (pintype "bidirectional"))
    )
    (net (code "480") (name "unconnected-(M42-NC-Pad3)") (class "Default")
      (node (ref "M42") (pin "3") (pinfunction "NC_3") (pintype "bidirectional"))
    )
    (net (code "481") (name "unconnected-(M42-NC-Pad5)") (class "Default")
      (node (ref "M42") (pin "5") (pinfunction "NC_5") (pintype "bidirectional"))
    )
    (net (code "482") (name "unconnected-(M42-NC-Pad6)") (class "Default")
      (node (ref "M42") (pin "6") (pinfunction "NC_6") (pintype "bidirectional"))
    )
    (net (code "483") (name "unconnected-(M42-NC-Pad7)") (class "Default")
      (node (ref "M42") (pin "7") (pinfunction "NC_7") (pintype "bidirectional"))
    )
    (net (code "484") (name "unconnected-(M42-NC-Pad14)") (class "Default")
      (node (ref "M42") (pin "14") (pinfunction "NC_14") (pintype "bidirectional"))
    )
    (net (code "485") (name "unconnected-(M43-DRDY-Pad15)") (class "Default")
      (node (ref "M43") (pin "15") (pinfunction "DRDY_15") (pintype "bidirectional"))
    )
    (net (code "486") (name "unconnected-(M43-NC-Pad3)") (class "Default")
      (node (ref "M43") (pin "3") (pinfunction "NC_3") (pintype "bidirectional"))
    )
    (net (code "487") (name "unconnected-(M43-NC-Pad5)") (class "Default")
      (node (ref "M43") (pin "5") (pinfunction "NC_5") (pintype "bidirectional"))
    )
    (net (code "488") (name "unconnected-(M43-NC-Pad6)") (class "Default")
      (node (ref "M43") (pin "6") (pinfunction "NC_6") (pintype "bidirectional"))
    )
    (net (code "489") (name "unconnected-(M43-NC-Pad7)") (class "Default")
      (node (ref "M43") (pin "7") (pinfunction "NC_7") (pintype "bidirectional"))
    )
    (net (code "490") (name "unconnected-(M43-NC-Pad14)") (class "Default")
      (node (ref "M43") (pin "14") (pinfunction "NC_14") (pintype "bidirectional"))
    )
    (net (code "491") (name "unconnected-(M44-DRDY-Pad15)") (class "Default")
      (node (ref "M44") (pin "15") (pinfunction "DRDY_15") (pintype "bidirectional"))
    )
    (net (code "492") (name "unconnected-(M44-NC-Pad3)") (class "Default")
      (node (ref "M44") (pin "3") (pinfunction "NC_3") (pintype "bidirectional"))
    )
    (net (code "493") (name "unconnected-(M44-NC-Pad5)") (class "Default")
      (node (ref "M44") (pin "5") (pinfunction "NC_5") (pintype "bidirectional"))
    )
    (net (code "494") (name "unconnected-(M44-NC-Pad6)") (class "Default")
      (node (ref "M44") (pin "6") (pinfunction "NC_6") (pintype "bidirectional"))
    )
    (net (code "495") (name "unconnected-(M44-NC-Pad7)") (class "Default")
      (node (ref "M44") (pin "7") (pinfunction "NC_7") (pintype "bidirectional"))
    )
    (net (code "496") (name "unconnected-(M44-NC-Pad14)") (class "Default")
      (node (ref "M44") (pin "14") (pinfunction "NC_14") (pintype "bidirectional"))
    )
    (net (code "497") (name "unconnected-(M45-DRDY-Pad15)") (class "Default")
      (node (ref "M45") (pin "15") (pinfunction "DRDY_15") (pintype "bidirectional"))
    )
    (net (code "498") (name "unconnected-(M45-NC-Pad3)") (class "Default")
      (node (ref "M45") (pin "3") (pinfunction "NC_3") (pintype "bidirectional"))
    )
    (net (code "499") (name "unconnected-(M45-NC-Pad5)") (class "Default")
      (node (ref "M45") (pin "5") (pinfunction "NC_5") (pintype "bidirectional"))
    )
    (net (code "500") (name "unconnected-(M45-NC-Pad6)") (class "Default")
      (node (ref "M45") (pin "6") (pinfunction "NC_6") (pintype "bidirectional"))
    )
    (net (code "501") (name "unconnected-(M45-NC-Pad7)") (class "Default")
      (node (ref "M45") (pin "7") (pinfunction "NC_7") (pintype "bidirectional"))
    )
    (net (code "502") (name "unconnected-(M45-NC-Pad14)") (class "Default")
      (node (ref "M45") (pin "14") (pinfunction "NC_14") (pintype "bidirectional"))
    )
    (net (code "503") (name "unconnected-(M46-DRDY-Pad15)") (class "Default")
      (node (ref "M46") (pin "15") (pinfunction "DRDY_15") (pintype "bidirectional"))
    )
    (net (code "504") (name "unconnected-(M46-NC-Pad3)") (class "Default")
      (node (ref "M46") (pin "3") (pinfunction "NC_3") (pintype "bidirectional"))
    )
    (net (code "505") (name "unconnected-(M46-NC-Pad5)") (class "Default")
      (node (ref "M46") (pin "5") (pinfunction "NC_5") (pintype "bidirectional"))
    )
    (net (code "506") (name "unconnected-(M46-NC-Pad6)") (class "Default")
      (node (ref "M46") (pin "6") (pinfunction "NC_6") (pintype "bidirectional"))
    )
    (net (code "507") (name "unconnected-(M46-NC-Pad7)") (class "Default")
      (node (ref "M46") (pin "7") (pinfunction "NC_7") (pintype "bidirectional"))
    )
    (net (code "508") (name "unconnected-(M46-NC-Pad14)") (class "Default")
      (node (ref "M46") (pin "14") (pinfunction "NC_14") (pintype "bidirectional"))
    )
    (net (code "509") (name "unconnected-(M47-DRDY-Pad15)") (class "Default")
      (node (ref "M47") (pin "15") (pinfunction "DRDY_15") (pintype "bidirectional"))
    )
    (net (code "510") (name "unconnected-(M47-NC-Pad3)") (class "Default")
      (node (ref "M47") (pin "3") (pinfunction "NC_3") (pintype "bidirectional"))
    )
    (net (code "511") (name "unconnected-(M47-NC-Pad5)") (class "Default")
      (node (ref "M47") (pin "5") (pinfunction "NC_5") (pintype "bidirectional"))
    )
    (net (code "512") (name "unconnected-(M47-NC-Pad6)") (class "Default")
      (node (ref "M47") (pin "6") (pinfunction "NC_6") (pintype "bidirectional"))
    )
    (net (code "513") (name "unconnected-(M47-NC-Pad7)") (class "Default")
      (node (ref "M47") (pin "7") (pinfunction "NC_7") (pintype "bidirectional"))
    )
    (net (code "514") (name "unconnected-(M47-NC-Pad14)") (class "Default")
      (node (ref "M47") (pin "14") (pinfunction "NC_14") (pintype "bidirectional"))
    )
    (net (code "515") (name "unconnected-(M48-DRDY-Pad15)") (class "Default")
      (node (ref "M48") (pin "15") (pinfunction "DRDY_15") (pintype "bidirectional"))
    )
    (net (code "516") (name "unconnected-(M48-NC-Pad3)") (class "Default")
      (node (ref "M48") (pin "3") (pinfunction "NC_3") (pintype "bidirectional"))
    )
    (net (code "517") (name "unconnected-(M48-NC-Pad5)") (class "Default")
      (node (ref "M48") (pin "5") (pinfunction "NC_5") (pintype "bidirectional"))
    )
    (net (code "518") (name "unconnected-(M48-NC-Pad6)") (class "Default")
      (node (ref "M48") (pin "6") (pinfunction "NC_6") (pintype "bidirectional"))
    )
    (net (code "519") (name "unconnected-(M48-NC-Pad7)") (class "Default")
      (node (ref "M48") (pin "7") (pinfunction "NC_7") (pintype "bidirectional"))
    )
    (net (code "520") (name "unconnected-(M48-NC-Pad14)") (class "Default")
      (node (ref "M48") (pin "14") (pinfunction "NC_14") (pintype "bidirectional"))
    )
    (net (code "521") (name "unconnected-(M51-DRDY-Pad15)") (class "Default")
      (node (ref "M51") (pin "15") (pinfunction "DRDY_15") (pintype "bidirectional"))
    )
    (net (code "522") (name "unconnected-(M51-NC-Pad3)") (class "Default")
      (node (ref "M51") (pin "3") (pinfunction "NC_3") (pintype "bidirectional"))
    )
    (net (code "523") (name "unconnected-(M51-NC-Pad5)") (class "Default")
      (node (ref "M51") (pin "5") (pinfunction "NC_5") (pintype "bidirectional"))
    )
    (net (code "524") (name "unconnected-(M51-NC-Pad6)") (class "Default")
      (node (ref "M51") (pin "6") (pinfunction "NC_6") (pintype "bidirectional"))
    )
    (net (code "525") (name "unconnected-(M51-NC-Pad7)") (class "Default")
      (node (ref "M51") (pin "7") (pinfunction "NC_7") (pintype "bidirectional"))
    )
    (net (code "526") (name "unconnected-(M51-NC-Pad14)") (class "Default")
      (node (ref "M51") (pin "14") (pinfunction "NC_14") (pintype "bidirectional"))
    )
    (net (code "527") (name "unconnected-(M52-DRDY-Pad15)") (class "Default")
      (node (ref "M52") (pin "15") (pinfunction "DRDY_15") (pintype "bidirectional"))
    )
    (net (code "528") (name "unconnected-(M52-NC-Pad3)") (class "Default")
      (node (ref "M52") (pin "3") (pinfunction "NC_3") (pintype "bidirectional"))
    )
    (net (code "529") (name "unconnected-(M52-NC-Pad5)") (class "Default")
      (node (ref "M52") (pin "5") (pinfunction "NC_5") (pintype "bidirectional"))
    )
    (net (code "530") (name "unconnected-(M52-NC-Pad6)") (class "Default")
      (node (ref "M52") (pin "6") (pinfunction "NC_6") (pintype "bidirectional"))
    )
    (net (code "531") (name "unconnected-(M52-NC-Pad7)") (class "Default")
      (node (ref "M52") (pin "7") (pinfunction "NC_7") (pintype "bidirectional"))
    )
    (net (code "532") (name "unconnected-(M52-NC-Pad14)") (class "Default")
      (node (ref "M52") (pin "14") (pinfunction "NC_14") (pintype "bidirectional"))
    )
    (net (code "533") (name "unconnected-(M53-DRDY-Pad15)") (class "Default")
      (node (ref "M53") (pin "15") (pinfunction "DRDY_15") (pintype "bidirectional"))
    )
    (net (code "534") (name "unconnected-(M53-NC-Pad3)") (class "Default")
      (node (ref "M53") (pin "3") (pinfunction "NC_3") (pintype "bidirectional"))
    )
    (net (code "535") (name "unconnected-(M53-NC-Pad5)") (class "Default")
      (node (ref "M53") (pin "5") (pinfunction "NC_5") (pintype "bidirectional"))
    )
    (net (code "536") (name "unconnected-(M53-NC-Pad6)") (class "Default")
      (node (ref "M53") (pin "6") (pinfunction "NC_6") (pintype "bidirectional"))
    )
    (net (code "537") (name "unconnected-(M53-NC-Pad7)") (class "Default")
      (node (ref "M53") (pin "7") (pinfunction "NC_7") (pintype "bidirectional"))
    )
    (net (code "538") (name "unconnected-(M53-NC-Pad14)") (class "Default")
      (node (ref "M53") (pin "14") (pinfunction "NC_14") (pintype "bidirectional"))
    )
    (net (code "539") (name "unconnected-(M54-DRDY-Pad15)") (class "Default")
      (node (ref "M54") (pin "15") (pinfunction "DRDY_15") (pintype "bidirectional"))
    )
    (net (code "540") (name "unconnected-(M54-NC-Pad3)") (class "Default")
      (node (ref "M54") (pin "3") (pinfunction "NC_3") (pintype "bidirectional"))
    )
    (net (code "541") (name "unconnected-(M54-NC-Pad5)") (class "Default")
      (node (ref "M54") (pin "5") (pinfunction "NC_5") (pintype "bidirectional"))
    )
    (net (code "542") (name "unconnected-(M54-NC-Pad6)") (class "Default")
      (node (ref "M54") (pin "6") (pinfunction "NC_6") (pintype "bidirectional"))
    )
    (net (code "543") (name "unconnected-(M54-NC-Pad7)") (class "Default")
      (node (ref "M54") (pin "7") (pinfunction "NC_7") (pintype "bidirectional"))
    )
    (net (code "544") (name "unconnected-(M54-NC-Pad14)") (class "Default")
      (node (ref "M54") (pin "14") (pinfunction "NC_14") (pintype "bidirectional"))
    )
    (net (code "545") (name "unconnected-(M55-DRDY-Pad15)") (class "Default")
      (node (ref "M55") (pin "15") (pinfunction "DRDY_15") (pintype "bidirectional"))
    )
    (net (code "546") (name "unconnected-(M55-NC-Pad3)") (class "Default")
      (node (ref "M55") (pin "3") (pinfunction "NC_3") (pintype "bidirectional"))
    )
    (net (code "547") (name "unconnected-(M55-NC-Pad5)") (class "Default")
      (node (ref "M55") (pin "5") (pinfunction "NC_5") (pintype "bidirectional"))
    )
    (net (code "548") (name "unconnected-(M55-NC-Pad6)") (class "Default")
      (node (ref "M55") (pin "6") (pinfunction "NC_6") (pintype "bidirectional"))
    )
    (net (code "549") (name "unconnected-(M55-NC-Pad7)") (class "Default")
      (node (ref "M55") (pin "7") (pinfunction "NC_7") (pintype "bidirectional"))
    )
    (net (code "550") (name "unconnected-(M55-NC-Pad14)") (class "Default")
      (node (ref "M55") (pin "14") (pinfunction "NC_14") (pintype "bidirectional"))
    )
    (net (code "551") (name "unconnected-(M56-DRDY-Pad15)") (class "Default")
      (node (ref "M56") (pin "15") (pinfunction "DRDY_15") (pintype "bidirectional"))
    )
    (net (code "552") (name "unconnected-(M56-NC-Pad3)") (class "Default")
      (node (ref "M56") (pin "3") (pinfunction "NC_3") (pintype "bidirectional"))
    )
    (net (code "553") (name "unconnected-(M56-NC-Pad5)") (class "Default")
      (node (ref "M56") (pin "5") (pinfunction "NC_5") (pintype "bidirectional"))
    )
    (net (code "554") (name "unconnected-(M56-NC-Pad6)") (class "Default")
      (node (ref "M56") (pin "6") (pinfunction "NC_6") (pintype "bidirectional"))
    )
    (net (code "555") (name "unconnected-(M56-NC-Pad7)") (class "Default")
      (node (ref "M56") (pin "7") (pinfunction "NC_7") (pintype "bidirectional"))
    )
    (net (code "556") (name "unconnected-(M56-NC-Pad14)") (class "Default")
      (node (ref "M56") (pin "14") (pinfunction "NC_14") (pintype "bidirectional"))
    )
    (net (code "557") (name "unconnected-(M57-DRDY-Pad15)") (class "Default")
      (node (ref "M57") (pin "15") (pinfunction "DRDY_15") (pintype "bidirectional"))
    )
    (net (code "558") (name "unconnected-(M57-NC-Pad3)") (class "Default")
      (node (ref "M57") (pin "3") (pinfunction "NC_3") (pintype "bidirectional"))
    )
    (net (code "559") (name "unconnected-(M57-NC-Pad5)") (class "Default")
      (node (ref "M57") (pin "5") (pinfunction "NC_5") (pintype "bidirectional"))
    )
    (net (code "560") (name "unconnected-(M57-NC-Pad6)") (class "Default")
      (node (ref "M57") (pin "6") (pinfunction "NC_6") (pintype "bidirectional"))
    )
    (net (code "561") (name "unconnected-(M57-NC-Pad7)") (class "Default")
      (node (ref "M57") (pin "7") (pinfunction "NC_7") (pintype "bidirectional"))
    )
    (net (code "562") (name "unconnected-(M57-NC-Pad14)") (class "Default")
      (node (ref "M57") (pin "14") (pinfunction "NC_14") (pintype "bidirectional"))
    )
    (net (code "563") (name "unconnected-(M58-DRDY-Pad15)") (class "Default")
      (node (ref "M58") (pin "15") (pinfunction "DRDY_15") (pintype "bidirectional"))
    )
    (net (code "564") (name "unconnected-(M58-NC-Pad3)") (class "Default")
      (node (ref "M58") (pin "3") (pinfunction "NC_3") (pintype "bidirectional"))
    )
    (net (code "565") (name "unconnected-(M58-NC-Pad5)") (class "Default")
      (node (ref "M58") (pin "5") (pinfunction "NC_5") (pintype "bidirectional"))
    )
    (net (code "566") (name "unconnected-(M58-NC-Pad6)") (class "Default")
      (node (ref "M58") (pin "6") (pinfunction "NC_6") (pintype "bidirectional"))
    )
    (net (code "567") (name "unconnected-(M58-NC-Pad7)") (class "Default")
      (node (ref "M58") (pin "7") (pinfunction "NC_7") (pintype "bidirectional"))
    )
    (net (code "568") (name "unconnected-(M58-NC-Pad14)") (class "Default")
      (node (ref "M58") (pin "14") (pinfunction "NC_14") (pintype "bidirectional"))
    )
    (net (code "569") (name "unconnected-(M61-DRDY-Pad15)") (class "Default")
      (node (ref "M61") (pin "15") (pinfunction "DRDY_15") (pintype "bidirectional"))
    )
    (net (code "570") (name "unconnected-(M61-NC-Pad3)") (class "Default")
      (node (ref "M61") (pin "3") (pinfunction "NC_3") (pintype "bidirectional"))
    )
    (net (code "571") (name "unconnected-(M61-NC-Pad5)") (class "Default")
      (node (ref "M61") (pin "5") (pinfunction "NC_5") (pintype "bidirectional"))
    )
    (net (code "572") (name "unconnected-(M61-NC-Pad6)") (class "Default")
      (node (ref "M61") (pin "6") (pinfunction "NC_6") (pintype "bidirectional"))
    )
    (net (code "573") (name "unconnected-(M61-NC-Pad7)") (class "Default")
      (node (ref "M61") (pin "7") (pinfunction "NC_7") (pintype "bidirectional"))
    )
    (net (code "574") (name "unconnected-(M61-NC-Pad14)") (class "Default")
      (node (ref "M61") (pin "14") (pinfunction "NC_14") (pintype "bidirectional"))
    )
    (net (code "575") (name "unconnected-(M62-DRDY-Pad15)") (class "Default")
      (node (ref "M62") (pin "15") (pinfunction "DRDY_15") (pintype "bidirectional"))
    )
    (net (code "576") (name "unconnected-(M62-NC-Pad3)") (class "Default")
      (node (ref "M62") (pin "3") (pinfunction "NC_3") (pintype "bidirectional"))
    )
    (net (code "577") (name "unconnected-(M62-NC-Pad5)") (class "Default")
      (node (ref "M62") (pin "5") (pinfunction "NC_5") (pintype "bidirectional"))
    )
    (net (code "578") (name "unconnected-(M62-NC-Pad6)") (class "Default")
      (node (ref "M62") (pin "6") (pinfunction "NC_6") (pintype "bidirectional"))
    )
    (net (code "579") (name "unconnected-(M62-NC-Pad7)") (class "Default")
      (node (ref "M62") (pin "7") (pinfunction "NC_7") (pintype "bidirectional"))
    )
    (net (code "580") (name "unconnected-(M62-NC-Pad14)") (class "Default")
      (node (ref "M62") (pin "14") (pinfunction "NC_14") (pintype "bidirectional"))
    )
    (net (code "581") (name "unconnected-(M63-DRDY-Pad15)") (class "Default")
      (node (ref "M63") (pin "15") (pinfunction "DRDY_15") (pintype "bidirectional"))
    )
    (net (code "582") (name "unconnected-(M63-NC-Pad3)") (class "Default")
      (node (ref "M63") (pin "3") (pinfunction "NC_3") (pintype "bidirectional"))
    )
    (net (code "583") (name "unconnected-(M63-NC-Pad5)") (class "Default")
      (node (ref "M63") (pin "5") (pinfunction "NC_5") (pintype "bidirectional"))
    )
    (net (code "584") (name "unconnected-(M63-NC-Pad6)") (class "Default")
      (node (ref "M63") (pin "6") (pinfunction "NC_6") (pintype "bidirectional"))
    )
    (net (code "585") (name "unconnected-(M63-NC-Pad7)") (class "Default")
      (node (ref "M63") (pin "7") (pinfunction "NC_7") (pintype "bidirectional"))
    )
    (net (code "586") (name "unconnected-(M63-NC-Pad14)") (class "Default")
      (node (ref "M63") (pin "14") (pinfunction "NC_14") (pintype "bidirectional"))
    )
    (net (code "587") (name "unconnected-(M64-DRDY-Pad15)") (class "Default")
      (node (ref "M64") (pin "15") (pinfunction "DRDY_15") (pintype "bidirectional"))
    )
    (net (code "588") (name "unconnected-(M64-NC-Pad3)") (class "Default")
      (node (ref "M64") (pin "3") (pinfunction "NC_3") (pintype "bidirectional"))
    )
    (net (code "589") (name "unconnected-(M64-NC-Pad5)") (class "Default")
      (node (ref "M64") (pin "5") (pinfunction "NC_5") (pintype "bidirectional"))
    )
    (net (code "590") (name "unconnected-(M64-NC-Pad6)") (class "Default")
      (node (ref "M64") (pin "6") (pinfunction "NC_6") (pintype "bidirectional"))
    )
    (net (code "591") (name "unconnected-(M64-NC-Pad7)") (class "Default")
      (node (ref "M64") (pin "7") (pinfunction "NC_7") (pintype "bidirectional"))
    )
    (net (code "592") (name "unconnected-(M64-NC-Pad14)") (class "Default")
      (node (ref "M64") (pin "14") (pinfunction "NC_14") (pintype "bidirectional"))
    )
    (net (code "593") (name "unconnected-(M65-DRDY-Pad15)") (class "Default")
      (node (ref "M65") (pin "15") (pinfunction "DRDY_15") (pintype "bidirectional"))
    )
    (net (code "594") (name "unconnected-(M65-NC-Pad3)") (class "Default")
      (node (ref "M65") (pin "3") (pinfunction "NC_3") (pintype "bidirectional"))
    )
    (net (code "595") (name "unconnected-(M65-NC-Pad5)") (class "Default")
      (node (ref "M65") (pin "5") (pinfunction "NC_5") (pintype "bidirectional"))
    )
    (net (code "596") (name "unconnected-(M65-NC-Pad6)") (class "Default")
      (node (ref "M65") (pin "6") (pinfunction "NC_6") (pintype "bidirectional"))
    )
    (net (code "597") (name "unconnected-(M65-NC-Pad7)") (class "Default")
      (node (ref "M65") (pin "7") (pinfunction "NC_7") (pintype "bidirectional"))
    )
    (net (code "598") (name "unconnected-(M65-NC-Pad14)") (class "Default")
      (node (ref "M65") (pin "14") (pinfunction "NC_14") (pintype "bidirectional"))
    )
    (net (code "599") (name "unconnected-(M66-DRDY-Pad15)") (class "Default")
      (node (ref "M66") (pin "15") (pinfunction "DRDY_15") (pintype "bidirectional"))
    )
    (net (code "600") (name "unconnected-(M66-NC-Pad3)") (class "Default")
      (node (ref "M66") (pin "3") (pinfunction "NC_3") (pintype "bidirectional"))
    )
    (net (code "601") (name "unconnected-(M66-NC-Pad5)") (class "Default")
      (node (ref "M66") (pin "5") (pinfunction "NC_5") (pintype "bidirectional"))
    )
    (net (code "602") (name "unconnected-(M66-NC-Pad6)") (class "Default")
      (node (ref "M66") (pin "6") (pinfunction "NC_6") (pintype "bidirectional"))
    )
    (net (code "603") (name "unconnected-(M66-NC-Pad7)") (class "Default")
      (node (ref "M66") (pin "7") (pinfunction "NC_7") (pintype "bidirectional"))
    )
    (net (code "604") (name "unconnected-(M66-NC-Pad14)") (class "Default")
      (node (ref "M66") (pin "14") (pinfunction "NC_14") (pintype "bidirectional"))
    )
    (net (code "605") (name "unconnected-(M67-DRDY-Pad15)") (class "Default")
      (node (ref "M67") (pin "15") (pinfunction "DRDY_15") (pintype "bidirectional"))
    )
    (net (code "606") (name "unconnected-(M67-NC-Pad3)") (class "Default")
      (node (ref "M67") (pin "3") (pinfunction "NC_3") (pintype "bidirectional"))
    )
    (net (code "607") (name "unconnected-(M67-NC-Pad5)") (class "Default")
      (node (ref "M67") (pin "5") (pinfunction "NC_5") (pintype "bidirectional"))
    )
    (net (code "608") (name "unconnected-(M67-NC-Pad6)") (class "Default")
      (node (ref "M67") (pin "6") (pinfunction "NC_6") (pintype "bidirectional"))
    )
    (net (code "609") (name "unconnected-(M67-NC-Pad7)") (class "Default")
      (node (ref "M67") (pin "7") (pinfunction "NC_7") (pintype "bidirectional"))
    )
    (net (code "610") (name "unconnected-(M67-NC-Pad14)") (class "Default")
      (node (ref "M67") (pin "14") (pinfunction "NC_14") (pintype "bidirectional"))
    )
    (net (code "611") (name "unconnected-(M68-DRDY-Pad15)") (class "Default")
      (node (ref "M68") (pin "15") (pinfunction "DRDY_15") (pintype "bidirectional"))
    )
    (net (code "612") (name "unconnected-(M68-NC-Pad3)") (class "Default")
      (node (ref "M68") (pin "3") (pinfunction "NC_3") (pintype "bidirectional"))
    )
    (net (code "613") (name "unconnected-(M68-NC-Pad5)") (class "Default")
      (node (ref "M68") (pin "5") (pinfunction "NC_5") (pintype "bidirectional"))
    )
    (net (code "614") (name "unconnected-(M68-NC-Pad6)") (class "Default")
      (node (ref "M68") (pin "6") (pinfunction "NC_6") (pintype "bidirectional"))
    )
    (net (code "615") (name "unconnected-(M68-NC-Pad7)") (class "Default")
      (node (ref "M68") (pin "7") (pinfunction "NC_7") (pintype "bidirectional"))
    )
    (net (code "616") (name "unconnected-(M68-NC-Pad14)") (class "Default")
      (node (ref "M68") (pin "14") (pinfunction "NC_14") (pintype "bidirectional"))
    )
    (net (code "617") (name "unconnected-(M71-DRDY-Pad15)") (class "Default")
      (node (ref "M71") (pin "15") (pinfunction "DRDY_15") (pintype "bidirectional"))
    )
    (net (code "618") (name "unconnected-(M71-NC-Pad3)") (class "Default")
      (node (ref "M71") (pin "3") (pinfunction "NC_3") (pintype "bidirectional"))
    )
    (net (code "619") (name "unconnected-(M71-NC-Pad5)") (class "Default")
      (node (ref "M71") (pin "5") (pinfunction "NC_5") (pintype "bidirectional"))
    )
    (net (code "620") (name "unconnected-(M71-NC-Pad6)") (class "Default")
      (node (ref "M71") (pin "6") (pinfunction "NC_6") (pintype "bidirectional"))
    )
    (net (code "621") (name "unconnected-(M71-NC-Pad7)") (class "Default")
      (node (ref "M71") (pin "7") (pinfunction "NC_7") (pintype "bidirectional"))
    )
    (net (code "622") (name "unconnected-(M71-NC-Pad14)") (class "Default")
      (node (ref "M71") (pin "14") (pinfunction "NC_14") (pintype "bidirectional"))
    )
    (net (code "623") (name "unconnected-(M72-DRDY-Pad15)") (class "Default")
      (node (ref "M72") (pin "15") (pinfunction "DRDY_15") (pintype "bidirectional"))
    )
    (net (code "624") (name "unconnected-(M72-NC-Pad3)") (class "Default")
      (node (ref "M72") (pin "3") (pinfunction "NC_3") (pintype "bidirectional"))
    )
    (net (code "625") (name "unconnected-(M72-NC-Pad5)") (class "Default")
      (node (ref "M72") (pin "5") (pinfunction "NC_5") (pintype "bidirectional"))
    )
    (net (code "626") (name "unconnected-(M72-NC-Pad6)") (class "Default")
      (node (ref "M72") (pin "6") (pinfunction "NC_6") (pintype "bidirectional"))
    )
    (net (code "627") (name "unconnected-(M72-NC-Pad7)") (class "Default")
      (node (ref "M72") (pin "7") (pinfunction "NC_7") (pintype "bidirectional"))
    )
    (net (code "628") (name "unconnected-(M72-NC-Pad14)") (class "Default")
      (node (ref "M72") (pin "14") (pinfunction "NC_14") (pintype "bidirectional"))
    )
    (net (code "629") (name "unconnected-(M73-DRDY-Pad15)") (class "Default")
      (node (ref "M73") (pin "15") (pinfunction "DRDY_15") (pintype "bidirectional"))
    )
    (net (code "630") (name "unconnected-(M73-NC-Pad3)") (class "Default")
      (node (ref "M73") (pin "3") (pinfunction "NC_3") (pintype "bidirectional"))
    )
    (net (code "631") (name "unconnected-(M73-NC-Pad5)") (class "Default")
      (node (ref "M73") (pin "5") (pinfunction "NC_5") (pintype "bidirectional"))
    )
    (net (code "632") (name "unconnected-(M73-NC-Pad6)") (class "Default")
      (node (ref "M73") (pin "6") (pinfunction "NC_6") (pintype "bidirectional"))
    )
    (net (code "633") (name "unconnected-(M73-NC-Pad7)") (class "Default")
      (node (ref "M73") (pin "7") (pinfunction "NC_7") (pintype "bidirectional"))
    )
    (net (code "634") (name "unconnected-(M73-NC-Pad14)") (class "Default")
      (node (ref "M73") (pin "14") (pinfunction "NC_14") (pintype "bidirectional"))
    )
    (net (code "635") (name "unconnected-(M74-DRDY-Pad15)") (class "Default")
      (node (ref "M74") (pin "15") (pinfunction "DRDY_15") (pintype "bidirectional"))
    )
    (net (code "636") (name "unconnected-(M74-NC-Pad3)") (class "Default")
      (node (ref "M74") (pin "3") (pinfunction "NC_3") (pintype "bidirectional"))
    )
    (net (code "637") (name "unconnected-(M74-NC-Pad5)") (class "Default")
      (node (ref "M74") (pin "5") (pinfunction "NC_5") (pintype "bidirectional"))
    )
    (net (code "638") (name "unconnected-(M74-NC-Pad6)") (class "Default")
      (node (ref "M74") (pin "6") (pinfunction "NC_6") (pintype "bidirectional"))
    )
    (net (code "639") (name "unconnected-(M74-NC-Pad7)") (class "Default")
      (node (ref "M74") (pin "7") (pinfunction "NC_7") (pintype "bidirectional"))
    )
    (net (code "640") (name "unconnected-(M74-NC-Pad14)") (class "Default")
      (node (ref "M74") (pin "14") (pinfunction "NC_14") (pintype "bidirectional"))
    )
    (net (code "641") (name "unconnected-(M75-DRDY-Pad15)") (class "Default")
      (node (ref "M75") (pin "15") (pinfunction "DRDY_15") (pintype "bidirectional"))
    )
    (net (code "642") (name "unconnected-(M75-NC-Pad3)") (class "Default")
      (node (ref "M75") (pin "3") (pinfunction "NC_3") (pintype "bidirectional"))
    )
    (net (code "643") (name "unconnected-(M75-NC-Pad5)") (class "Default")
      (node (ref "M75") (pin "5") (pinfunction "NC_5") (pintype "bidirectional"))
    )
    (net (code "644") (name "unconnected-(M75-NC-Pad6)") (class "Default")
      (node (ref "M75") (pin "6") (pinfunction "NC_6") (pintype "bidirectional"))
    )
    (net (code "645") (name "unconnected-(M75-NC-Pad7)") (class "Default")
      (node (ref "M75") (pin "7") (pinfunction "NC_7") (pintype "bidirectional"))
    )
    (net (code "646") (name "unconnected-(M75-NC-Pad14)") (class "Default")
      (node (ref "M75") (pin "14") (pinfunction "NC_14") (pintype "bidirectional"))
    )
    (net (code "647") (name "unconnected-(M76-DRDY-Pad15)") (class "Default")
      (node (ref "M76") (pin "15") (pinfunction "DRDY_15") (pintype "bidirectional"))
    )
    (net (code "648") (name "unconnected-(M76-NC-Pad3)") (class "Default")
      (node (ref "M76") (pin "3") (pinfunction "NC_3") (pintype "bidirectional"))
    )
    (net (code "649") (name "unconnected-(M76-NC-Pad5)") (class "Default")
      (node (ref "M76") (pin "5") (pinfunction "NC_5") (pintype "bidirectional"))
    )
    (net (code "650") (name "unconnected-(M76-NC-Pad6)") (class "Default")
      (node (ref "M76") (pin "6") (pinfunction "NC_6") (pintype "bidirectional"))
    )
    (net (code "651") (name "unconnected-(M76-NC-Pad7)") (class "Default")
      (node (ref "M76") (pin "7") (pinfunction "NC_7") (pintype "bidirectional"))
    )
    (net (code "652") (name "unconnected-(M76-NC-Pad14)") (class "Default")
      (node (ref "M76") (pin "14") (pinfunction "NC_14") (pintype "bidirectional"))
    )
    (net (code "653") (name "unconnected-(M77-DRDY-Pad15)") (class "Default")
      (node (ref "M77") (pin "15") (pinfunction "DRDY_15") (pintype "bidirectional"))
    )
    (net (code "654") (name "unconnected-(M77-NC-Pad3)") (class "Default")
      (node (ref "M77") (pin "3") (pinfunction "NC_3") (pintype "bidirectional"))
    )
    (net (code "655") (name "unconnected-(M77-NC-Pad5)") (class "Default")
      (node (ref "M77") (pin "5") (pinfunction "NC_5") (pintype "bidirectional"))
    )
    (net (code "656") (name "unconnected-(M77-NC-Pad6)") (class "Default")
      (node (ref "M77") (pin "6") (pinfunction "NC_6") (pintype "bidirectional"))
    )
    (net (code "657") (name "unconnected-(M77-NC-Pad7)") (class "Default")
      (node (ref "M77") (pin "7") (pinfunction "NC_7") (pintype "bidirectional"))
    )
    (net (code "658") (name "unconnected-(M77-NC-Pad14)") (class "Default")
      (node (ref "M77") (pin "14") (pinfunction "NC_14") (pintype "bidirectional"))
    )
    (net (code "659") (name "unconnected-(M78-DRDY-Pad15)") (class "Default")
      (node (ref "M78") (pin "15") (pinfunction "DRDY_15") (pintype "bidirectional"))
    )
    (net (code "660") (name "unconnected-(M78-NC-Pad3)") (class "Default")
      (node (ref "M78") (pin "3") (pinfunction "NC_3") (pintype "bidirectional"))
    )
    (net (code "661") (name "unconnected-(M78-NC-Pad5)") (class "Default")
      (node (ref "M78") (pin "5") (pinfunction "NC_5") (pintype "bidirectional"))
    )
    (net (code "662") (name "unconnected-(M78-NC-Pad6)") (class "Default")
      (node (ref "M78") (pin "6") (pinfunction "NC_6") (pintype "bidirectional"))
    )
    (net (code "663") (name "unconnected-(M78-NC-Pad7)") (class "Default")
      (node (ref "M78") (pin "7") (pinfunction "NC_7") (pintype "bidirectional"))
    )
    (net (code "664") (name "unconnected-(M78-NC-Pad14)") (class "Default")
      (node (ref "M78") (pin "14") (pinfunction "NC_14") (pintype "bidirectional"))
    )
    (net (code "665") (name "unconnected-(M81-DRDY-Pad15)") (class "Default")
      (node (ref "M81") (pin "15") (pinfunction "DRDY_15") (pintype "bidirectional"))
    )
    (net (code "666") (name "unconnected-(M81-NC-Pad3)") (class "Default")
      (node (ref "M81") (pin "3") (pinfunction "NC_3") (pintype "bidirectional"))
    )
    (net (code "667") (name "unconnected-(M81-NC-Pad5)") (class "Default")
      (node (ref "M81") (pin "5") (pinfunction "NC_5") (pintype "bidirectional"))
    )
    (net (code "668") (name "unconnected-(M81-NC-Pad6)") (class "Default")
      (node (ref "M81") (pin "6") (pinfunction "NC_6") (pintype "bidirectional"))
    )
    (net (code "669") (name "unconnected-(M81-NC-Pad7)") (class "Default")
      (node (ref "M81") (pin "7") (pinfunction "NC_7") (pintype "bidirectional"))
    )
    (net (code "670") (name "unconnected-(M81-NC-Pad14)") (class "Default")
      (node (ref "M81") (pin "14") (pinfunction "NC_14") (pintype "bidirectional"))
    )
    (net (code "671") (name "unconnected-(M82-DRDY-Pad15)") (class "Default")
      (node (ref "M82") (pin "15") (pinfunction "DRDY_15") (pintype "bidirectional"))
    )
    (net (code "672") (name "unconnected-(M82-NC-Pad3)") (class "Default")
      (node (ref "M82") (pin "3") (pinfunction "NC_3") (pintype "bidirectional"))
    )
    (net (code "673") (name "unconnected-(M82-NC-Pad5)") (class "Default")
      (node (ref "M82") (pin "5") (pinfunction "NC_5") (pintype "bidirectional"))
    )
    (net (code "674") (name "unconnected-(M82-NC-Pad6)") (class "Default")
      (node (ref "M82") (pin "6") (pinfunction "NC_6") (pintype "bidirectional"))
    )
    (net (code "675") (name "unconnected-(M82-NC-Pad7)") (class "Default")
      (node (ref "M82") (pin "7") (pinfunction "NC_7") (pintype "bidirectional"))
    )
    (net (code "676") (name "unconnected-(M82-NC-Pad14)") (class "Default")
      (node (ref "M82") (pin "14") (pinfunction "NC_14") (pintype "bidirectional"))
    )
    (net (code "677") (name "unconnected-(M83-DRDY-Pad15)") (class "Default")
      (node (ref "M83") (pin "15") (pinfunction "DRDY_15") (pintype "bidirectional"))
    )
    (net (code "678") (name "unconnected-(M83-NC-Pad3)") (class "Default")
      (node (ref "M83") (pin "3") (pinfunction "NC_3") (pintype "bidirectional"))
    )
    (net (code "679") (name "unconnected-(M83-NC-Pad5)") (class "Default")
      (node (ref "M83") (pin "5") (pinfunction "NC_5") (pintype "bidirectional"))
    )
    (net (code "680") (name "unconnected-(M83-NC-Pad6)") (class "Default")
      (node (ref "M83") (pin "6") (pinfunction "NC_6") (pintype "bidirectional"))
    )
    (net (code "681") (name "unconnected-(M83-NC-Pad7)") (class "Default")
      (node (ref "M83") (pin "7") (pinfunction "NC_7") (pintype "bidirectional"))
    )
    (net (code "682") (name "unconnected-(M83-NC-Pad14)") (class "Default")
      (node (ref "M83") (pin "14") (pinfunction "NC_14") (pintype "bidirectional"))
    )
    (net (code "683") (name "unconnected-(M84-DRDY-Pad15)") (class "Default")
      (node (ref "M84") (pin "15") (pinfunction "DRDY_15") (pintype "bidirectional"))
    )
    (net (code "684") (name "unconnected-(M84-NC-Pad3)") (class "Default")
      (node (ref "M84") (pin "3") (pinfunction "NC_3") (pintype "bidirectional"))
    )
    (net (code "685") (name "unconnected-(M84-NC-Pad5)") (class "Default")
      (node (ref "M84") (pin "5") (pinfunction "NC_5") (pintype "bidirectional"))
    )
    (net (code "686") (name "unconnected-(M84-NC-Pad6)") (class "Default")
      (node (ref "M84") (pin "6") (pinfunction "NC_6") (pintype "bidirectional"))
    )
    (net (code "687") (name "unconnected-(M84-NC-Pad7)") (class "Default")
      (node (ref "M84") (pin "7") (pinfunction "NC_7") (pintype "bidirectional"))
    )
    (net (code "688") (name "unconnected-(M84-NC-Pad14)") (class "Default")
      (node (ref "M84") (pin "14") (pinfunction "NC_14") (pintype "bidirectional"))
    )
    (net (code "689") (name "unconnected-(M85-DRDY-Pad15)") (class "Default")
      (node (ref "M85") (pin "15") (pinfunction "DRDY_15") (pintype "bidirectional"))
    )
    (net (code "690") (name "unconnected-(M85-NC-Pad3)") (class "Default")
      (node (ref "M85") (pin "3") (pinfunction "NC_3") (pintype "bidirectional"))
    )
    (net (code "691") (name "unconnected-(M85-NC-Pad5)") (class "Default")
      (node (ref "M85") (pin "5") (pinfunction "NC_5") (pintype "bidirectional"))
    )
    (net (code "692") (name "unconnected-(M85-NC-Pad6)") (class "Default")
      (node (ref "M85") (pin "6") (pinfunction "NC_6") (pintype "bidirectional"))
    )
    (net (code "693") (name "unconnected-(M85-NC-Pad7)") (class "Default")
      (node (ref "M85") (pin "7") (pinfunction "NC_7") (pintype "bidirectional"))
    )
    (net (code "694") (name "unconnected-(M85-NC-Pad14)") (class "Default")
      (node (ref "M85") (pin "14") (pinfunction "NC_14") (pintype "bidirectional"))
    )
    (net (code "695") (name "unconnected-(M86-DRDY-Pad15)") (class "Default")
      (node (ref "M86") (pin "15") (pinfunction "DRDY_15") (pintype "bidirectional"))
    )
    (net (code "696") (name "unconnected-(M86-NC-Pad3)") (class "Default")
      (node (ref "M86") (pin "3") (pinfunction "NC_3") (pintype "bidirectional"))
    )
    (net (code "697") (name "unconnected-(M86-NC-Pad5)") (class "Default")
      (node (ref "M86") (pin "5") (pinfunction "NC_5") (pintype "bidirectional"))
    )
    (net (code "698") (name "unconnected-(M86-NC-Pad6)") (class "Default")
      (node (ref "M86") (pin "6") (pinfunction "NC_6") (pintype "bidirectional"))
    )
    (net (code "699") (name "unconnected-(M86-NC-Pad7)") (class "Default")
      (node (ref "M86") (pin "7") (pinfunction "NC_7") (pintype "bidirectional"))
    )
    (net (code "700") (name "unconnected-(M86-NC-Pad14)") (class "Default")
      (node (ref "M86") (pin "14") (pinfunction "NC_14") (pintype "bidirectional"))
    )
    (net (code "701") (name "unconnected-(M87-DRDY-Pad15)") (class "Default")
      (node (ref "M87") (pin "15") (pinfunction "DRDY_15") (pintype "bidirectional"))
    )
    (net (code "702") (name "unconnected-(M87-NC-Pad3)") (class "Default")
      (node (ref "M87") (pin "3") (pinfunction "NC_3") (pintype "bidirectional"))
    )
    (net (code "703") (name "unconnected-(M87-NC-Pad5)") (class "Default")
      (node (ref "M87") (pin "5") (pinfunction "NC_5") (pintype "bidirectional"))
    )
    (net (code "704") (name "unconnected-(M87-NC-Pad6)") (class "Default")
      (node (ref "M87") (pin "6") (pinfunction "NC_6") (pintype "bidirectional"))
    )
    (net (code "705") (name "unconnected-(M87-NC-Pad7)") (class "Default")
      (node (ref "M87") (pin "7") (pinfunction "NC_7") (pintype "bidirectional"))
    )
    (net (code "706") (name "unconnected-(M87-NC-Pad14)") (class "Default")
      (node (ref "M87") (pin "14") (pinfunction "NC_14") (pintype "bidirectional"))
    )
    (net (code "707") (name "unconnected-(M88-DRDY-Pad15)") (class "Default")
      (node (ref "M88") (pin "15") (pinfunction "DRDY_15") (pintype "bidirectional"))
    )
    (net (code "708") (name "unconnected-(M88-NC-Pad3)") (class "Default")
      (node (ref "M88") (pin "3") (pinfunction "NC_3") (pintype "bidirectional"))
    )
    (net (code "709") (name "unconnected-(M88-NC-Pad5)") (class "Default")
      (node (ref "M88") (pin "5") (pinfunction "NC_5") (pintype "bidirectional"))
    )
    (net (code "710") (name "unconnected-(M88-NC-Pad6)") (class "Default")
      (node (ref "M88") (pin "6") (pinfunction "NC_6") (pintype "bidirectional"))
    )
    (net (code "711") (name "unconnected-(M88-NC-Pad7)") (class "Default")
      (node (ref "M88") (pin "7") (pinfunction "NC_7") (pintype "bidirectional"))
    )
    (net (code "712") (name "unconnected-(M88-NC-Pad14)") (class "Default")
      (node (ref "M88") (pin "14") (pinfunction "NC_14") (pintype "bidirectional"))
    )
  )
)
